# debug_backplane.net
KiCad netlist of a schematic drawn in EAGLE
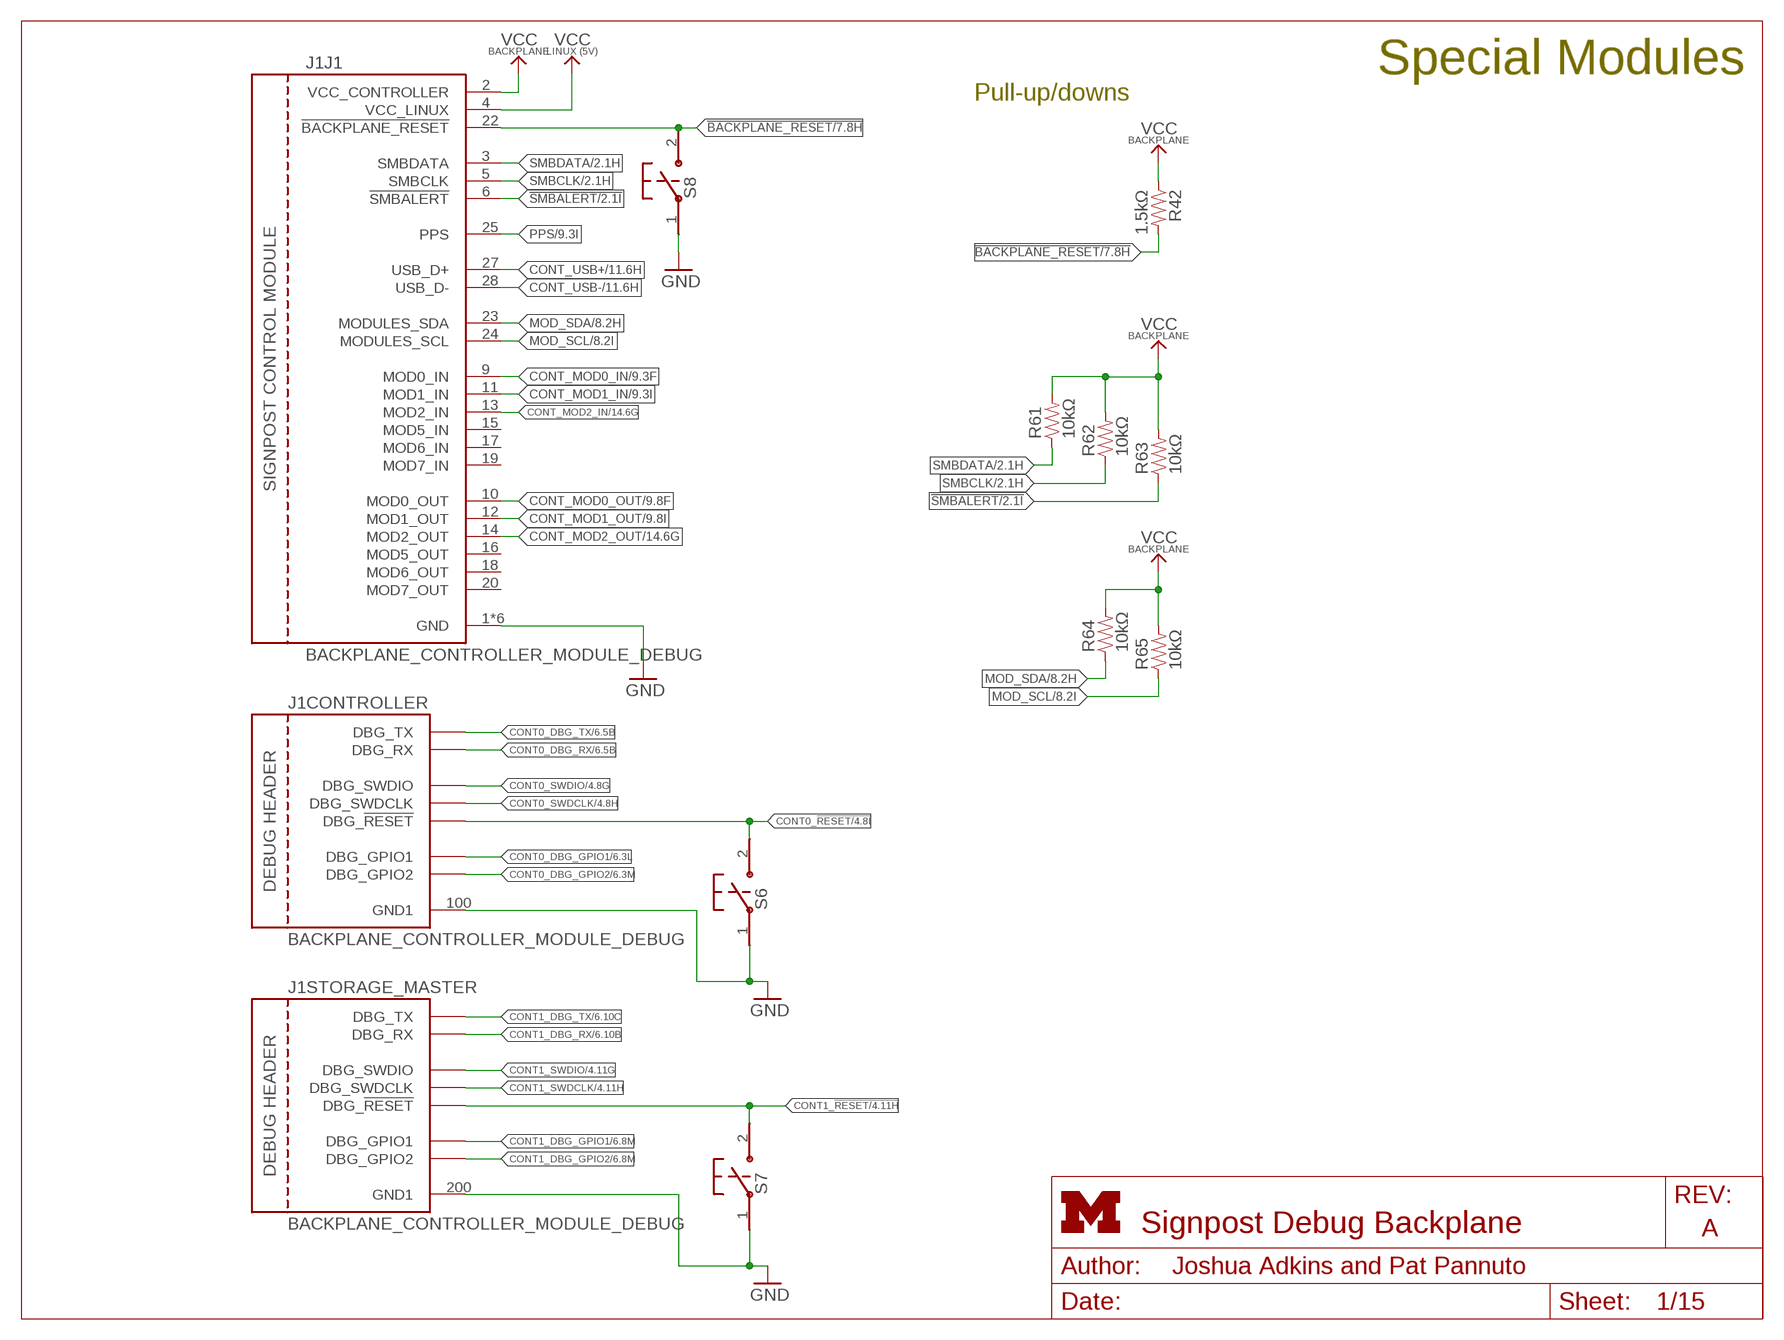
[diagram p0: schematic, sheet 1]
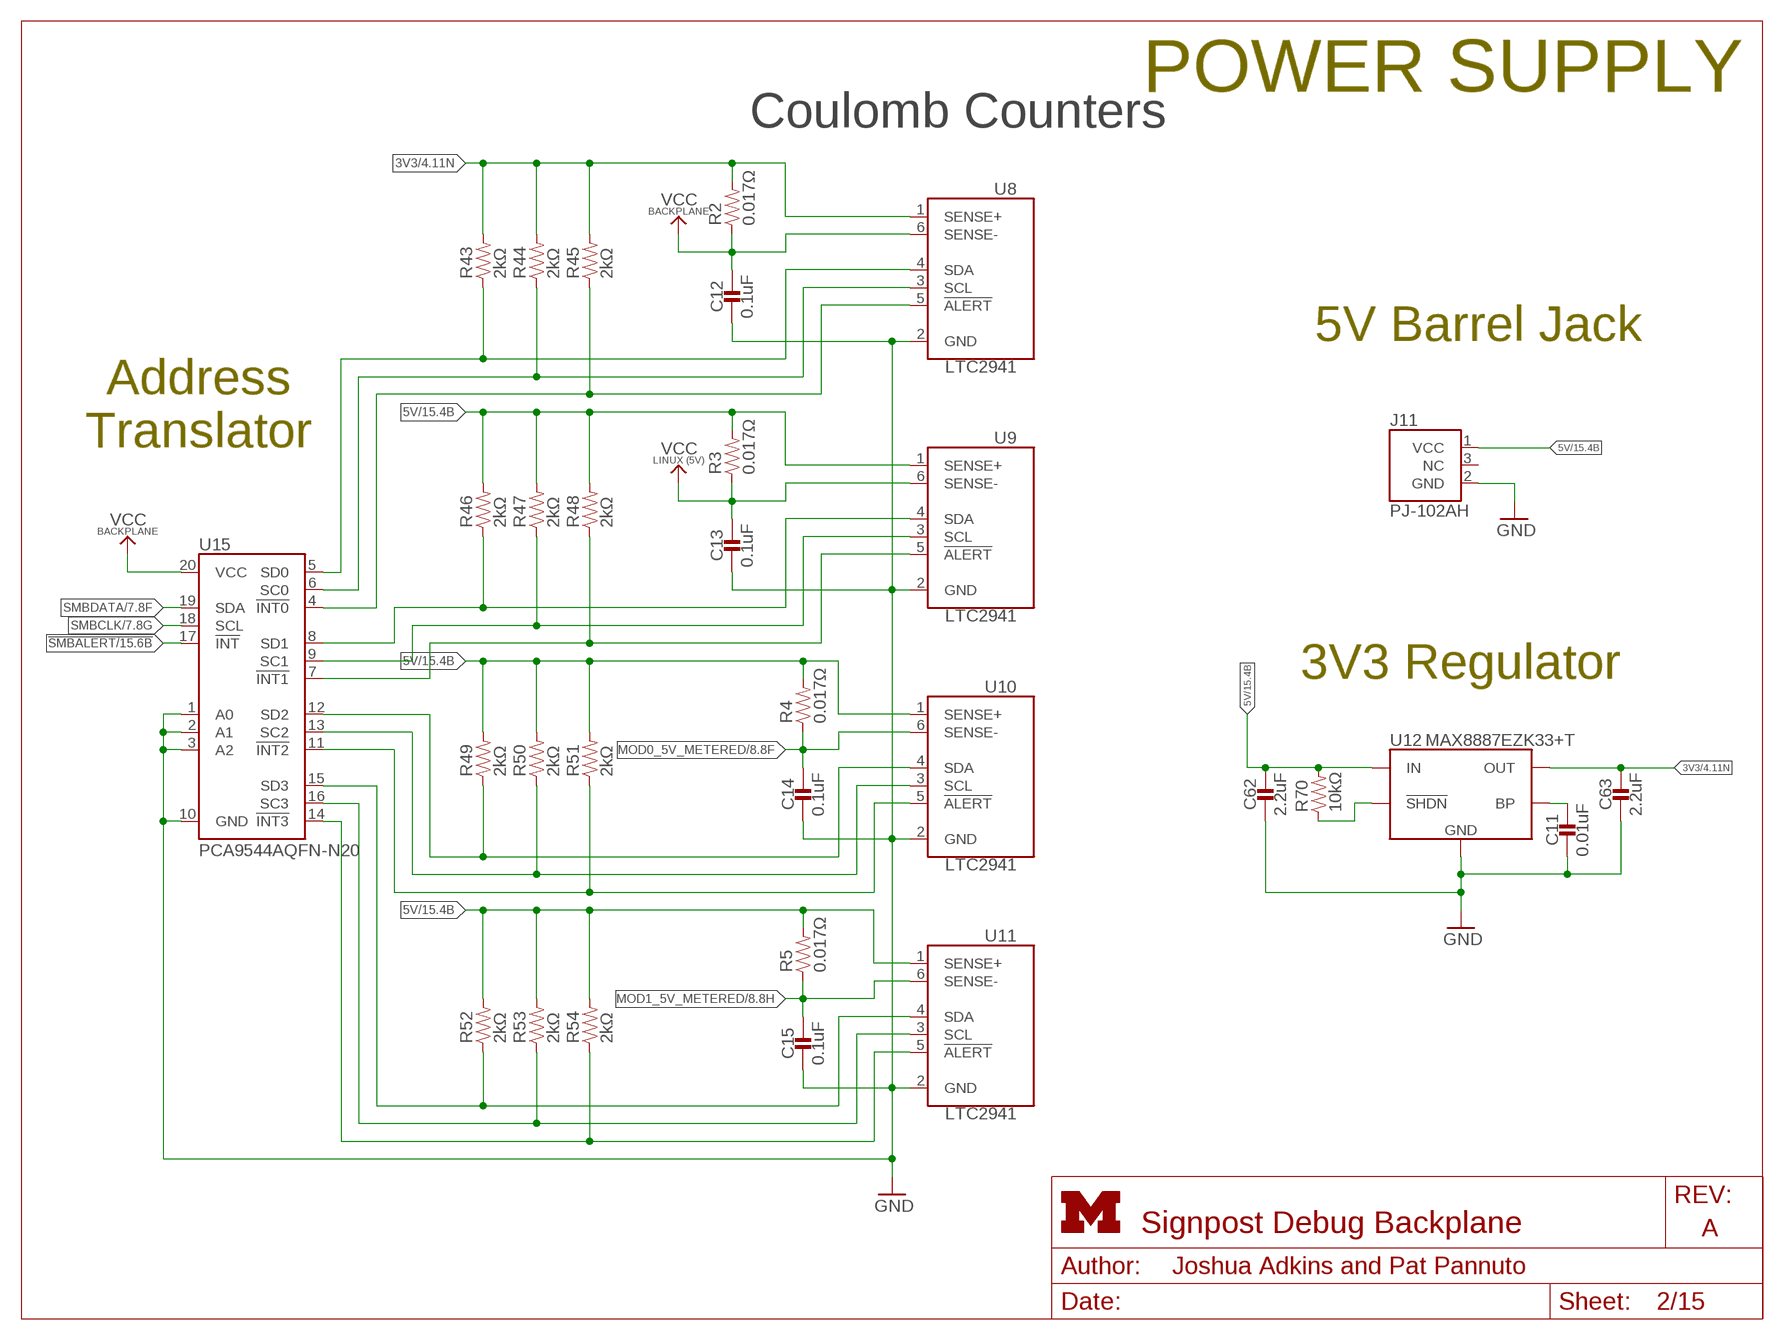
[diagram p1: schematic, sheet 2]
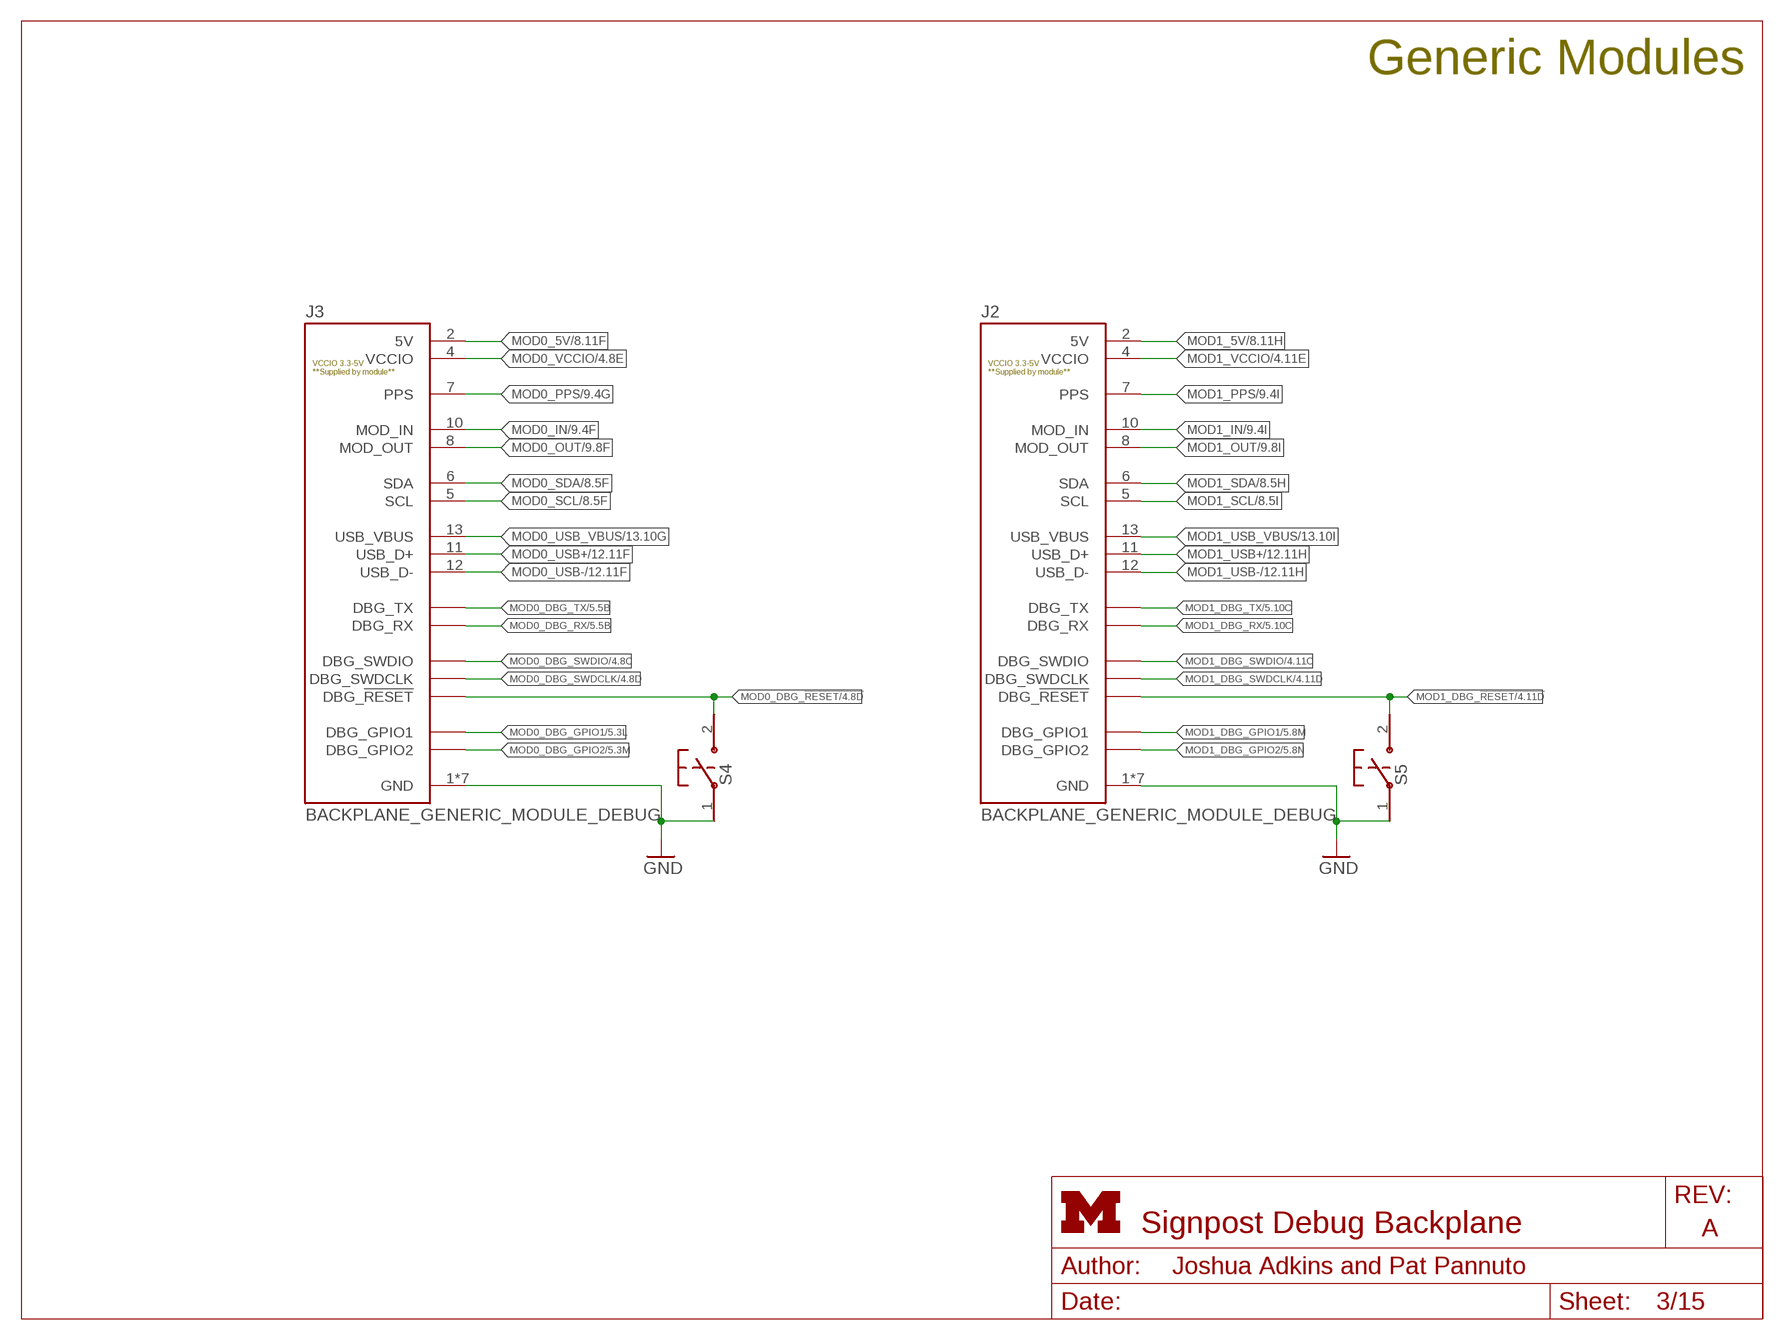
[diagram p2: schematic, sheet 3]
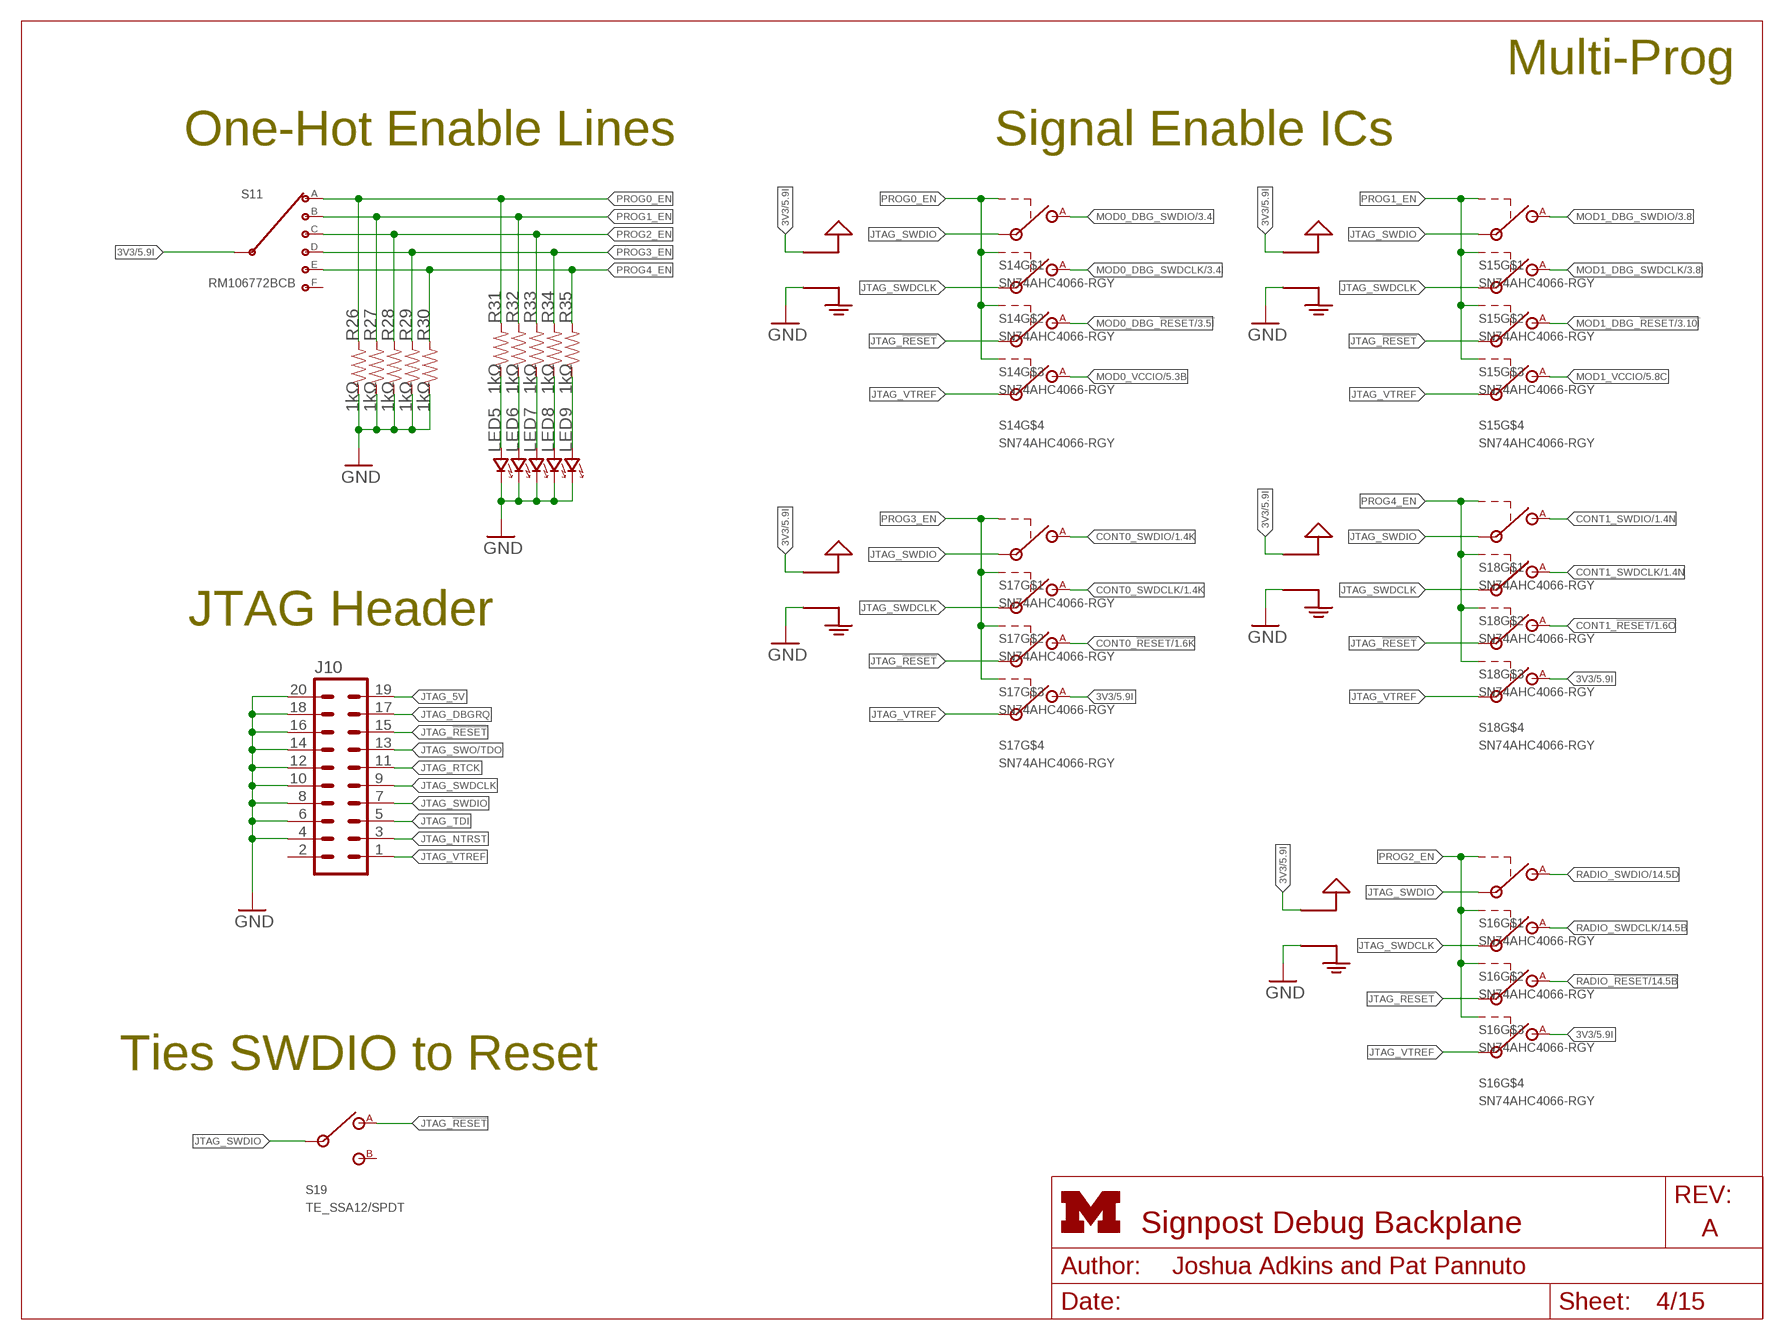
[diagram p3: schematic, sheet 4]
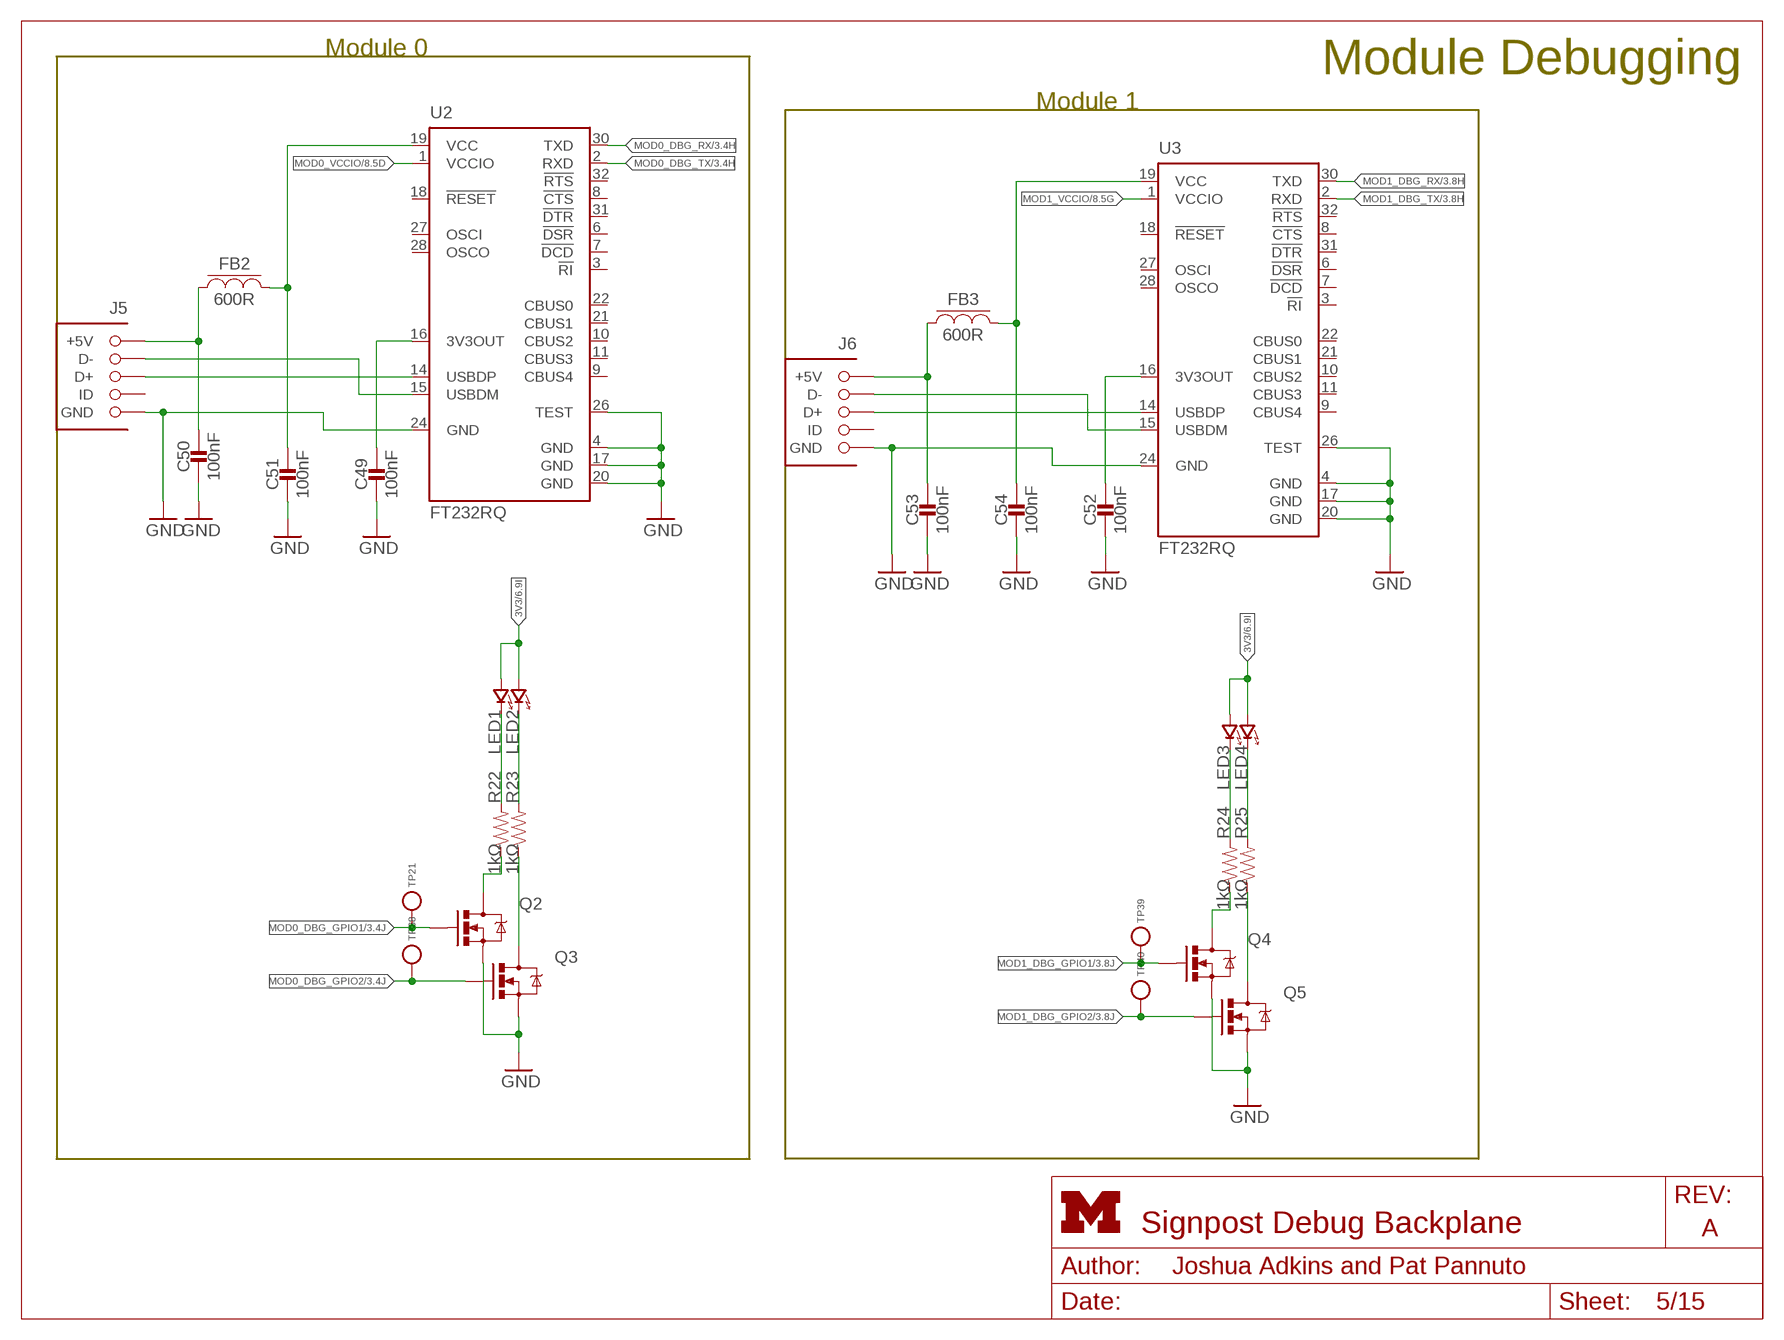
[diagram p4: schematic, sheet 5]
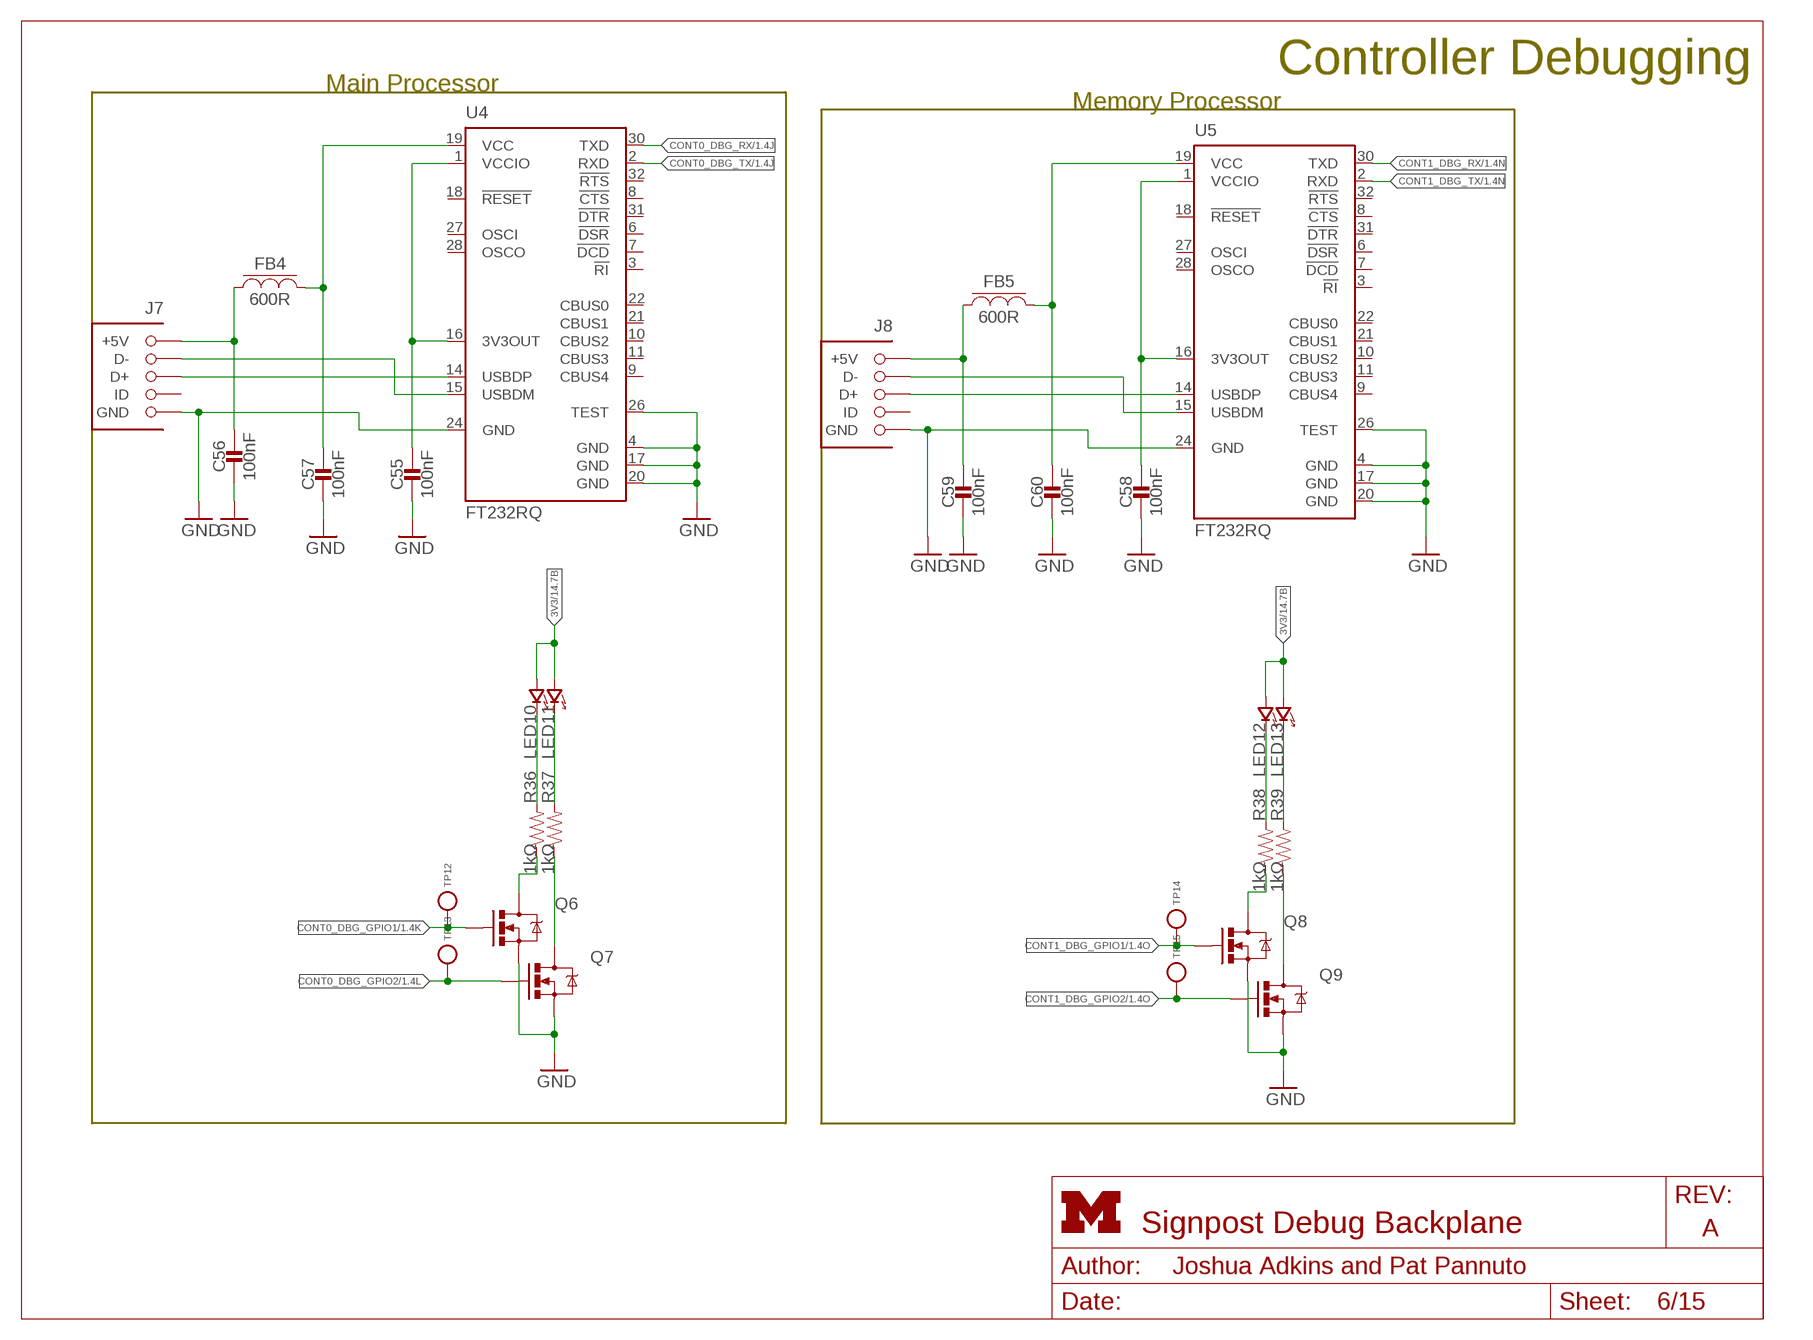
[diagram p5: schematic, sheet 6]
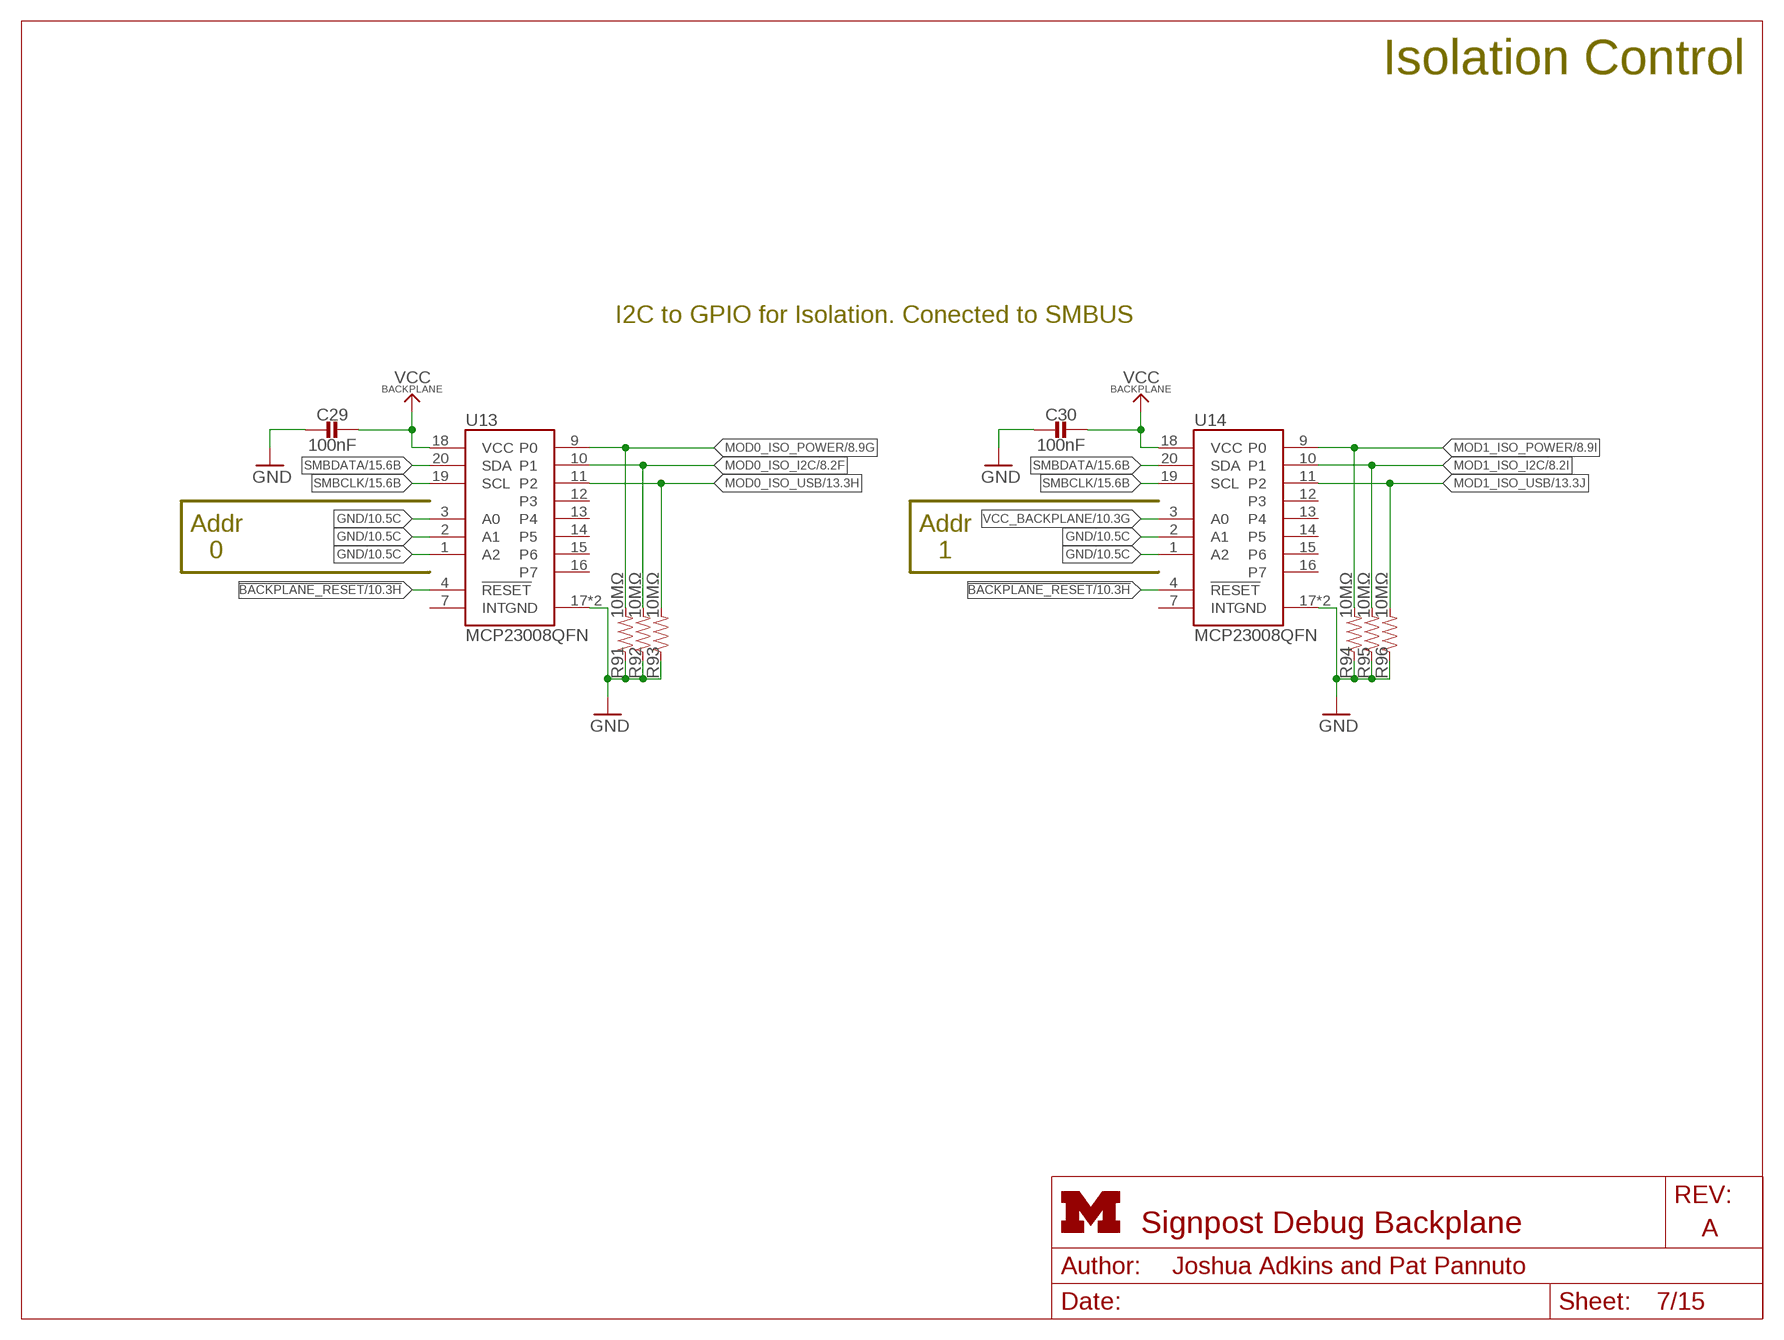
[diagram p6: schematic, sheet 7]
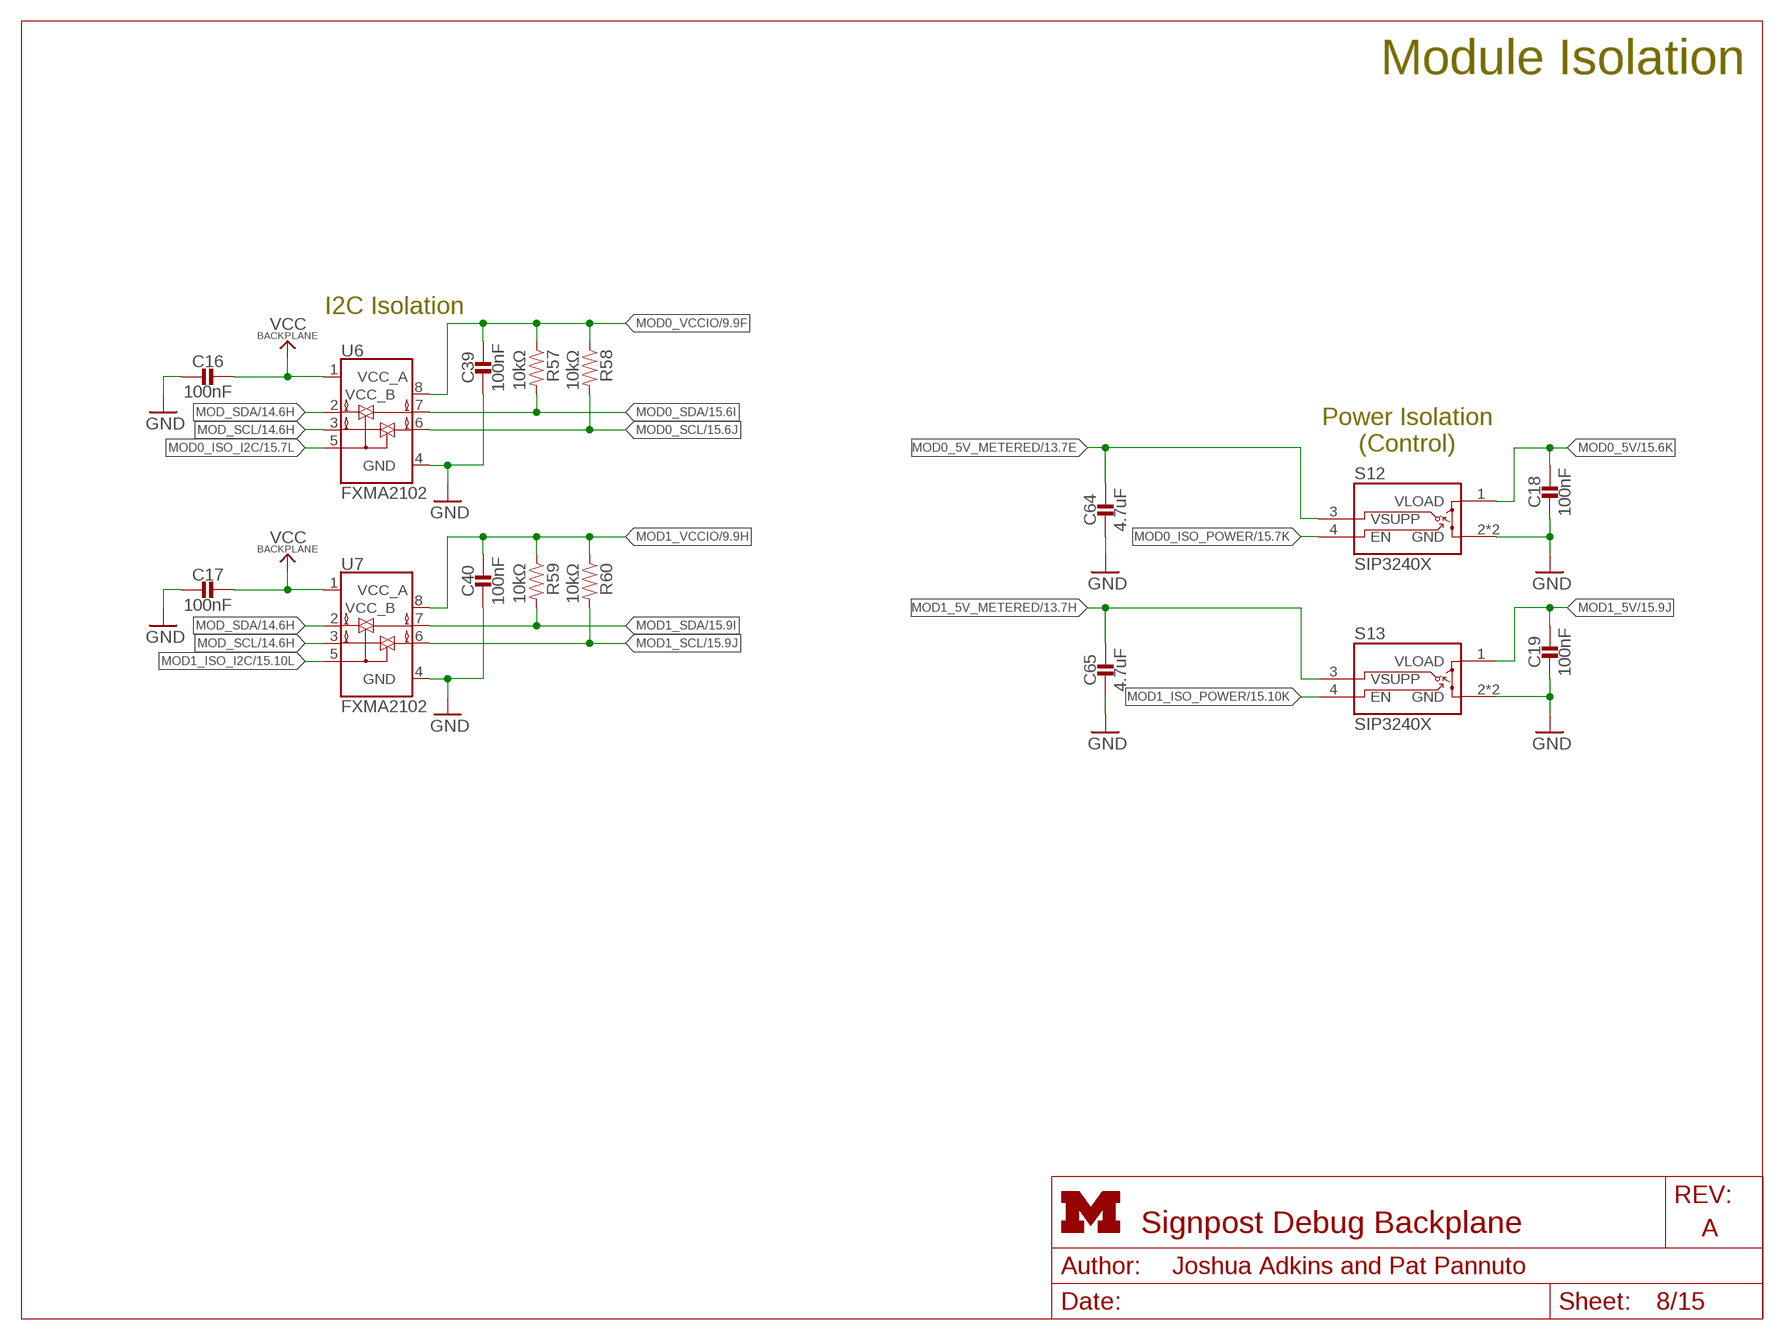
[diagram p7: schematic, sheet 8]
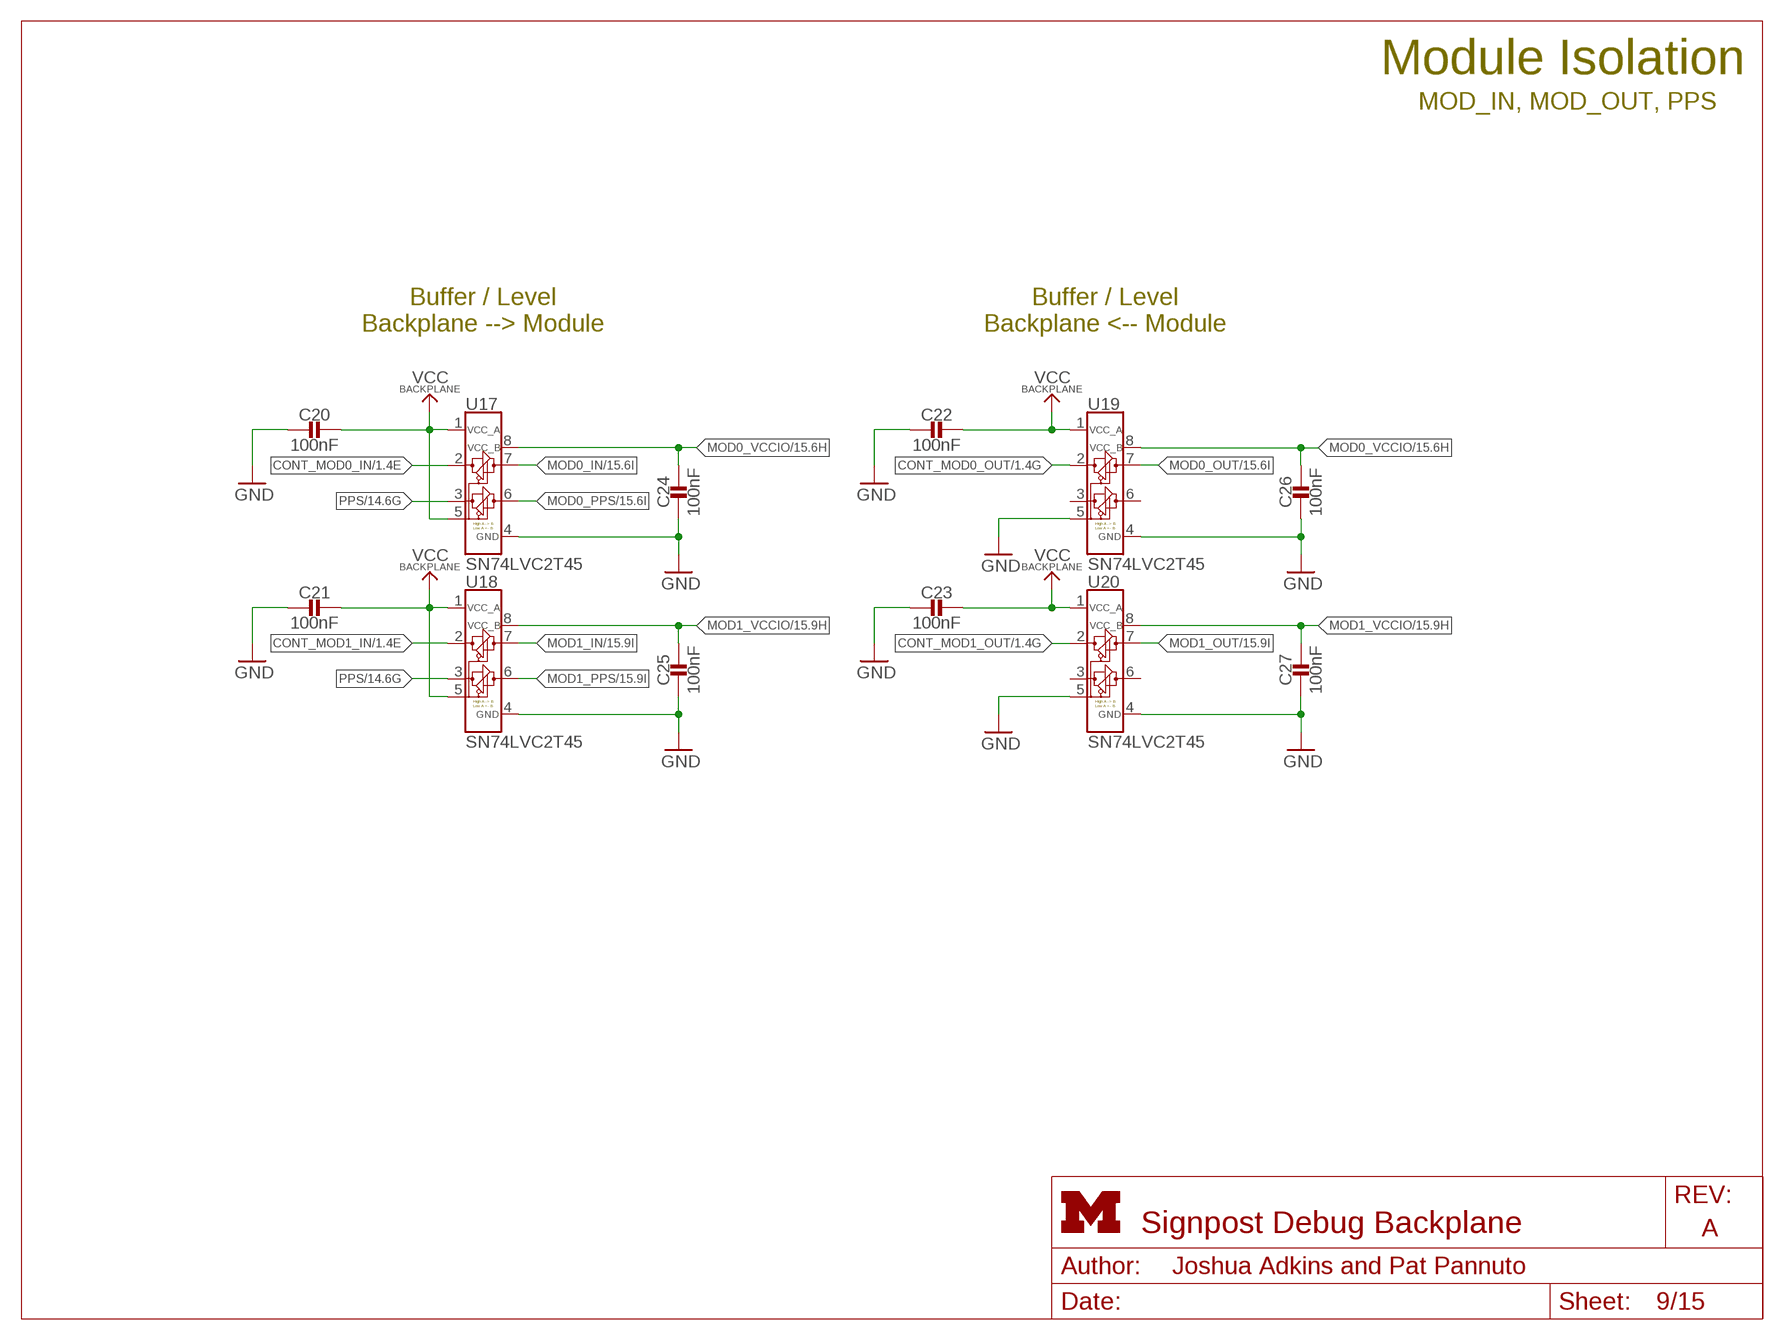
[diagram p8: schematic, sheet 9]
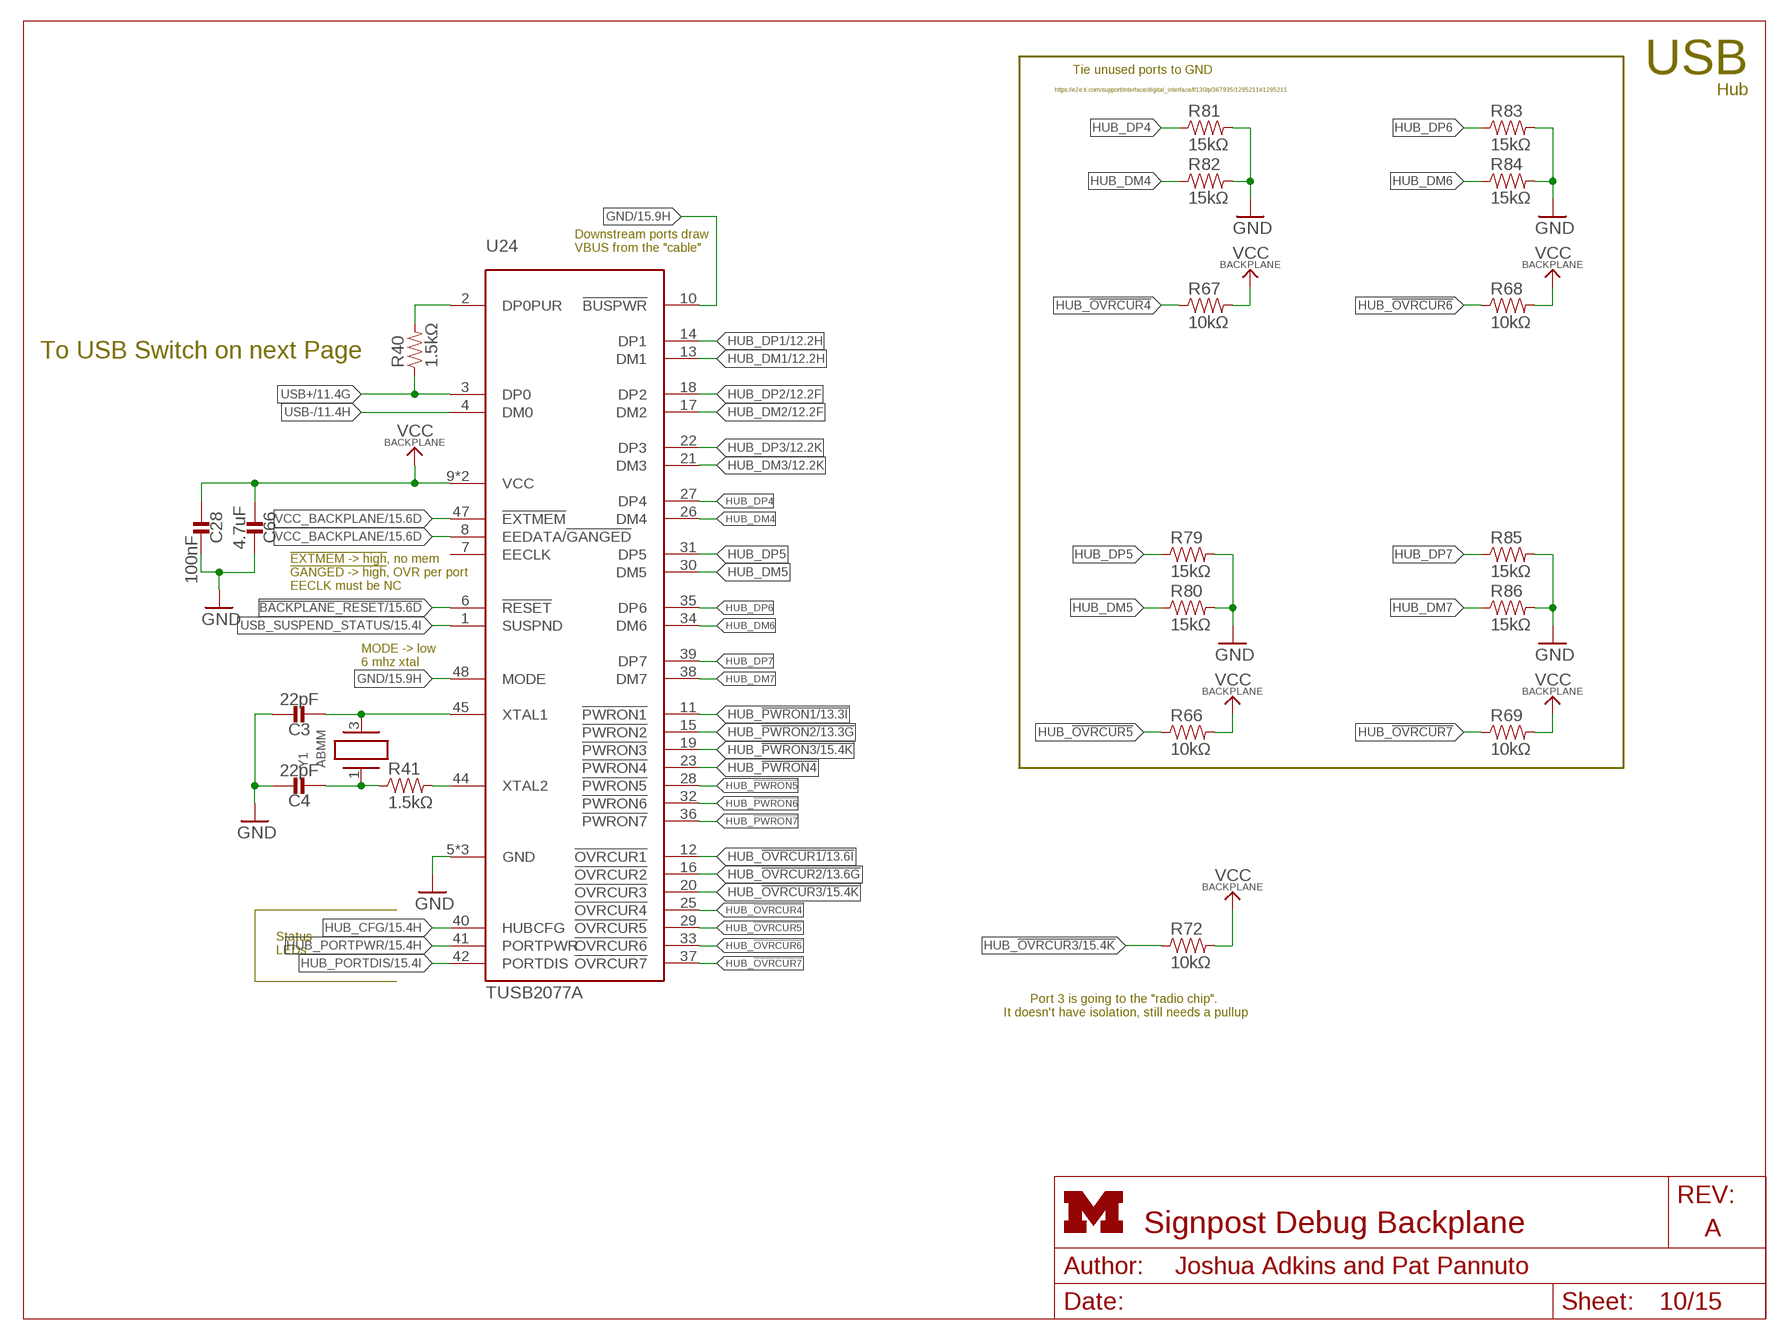
[diagram p9: schematic, sheet 10]
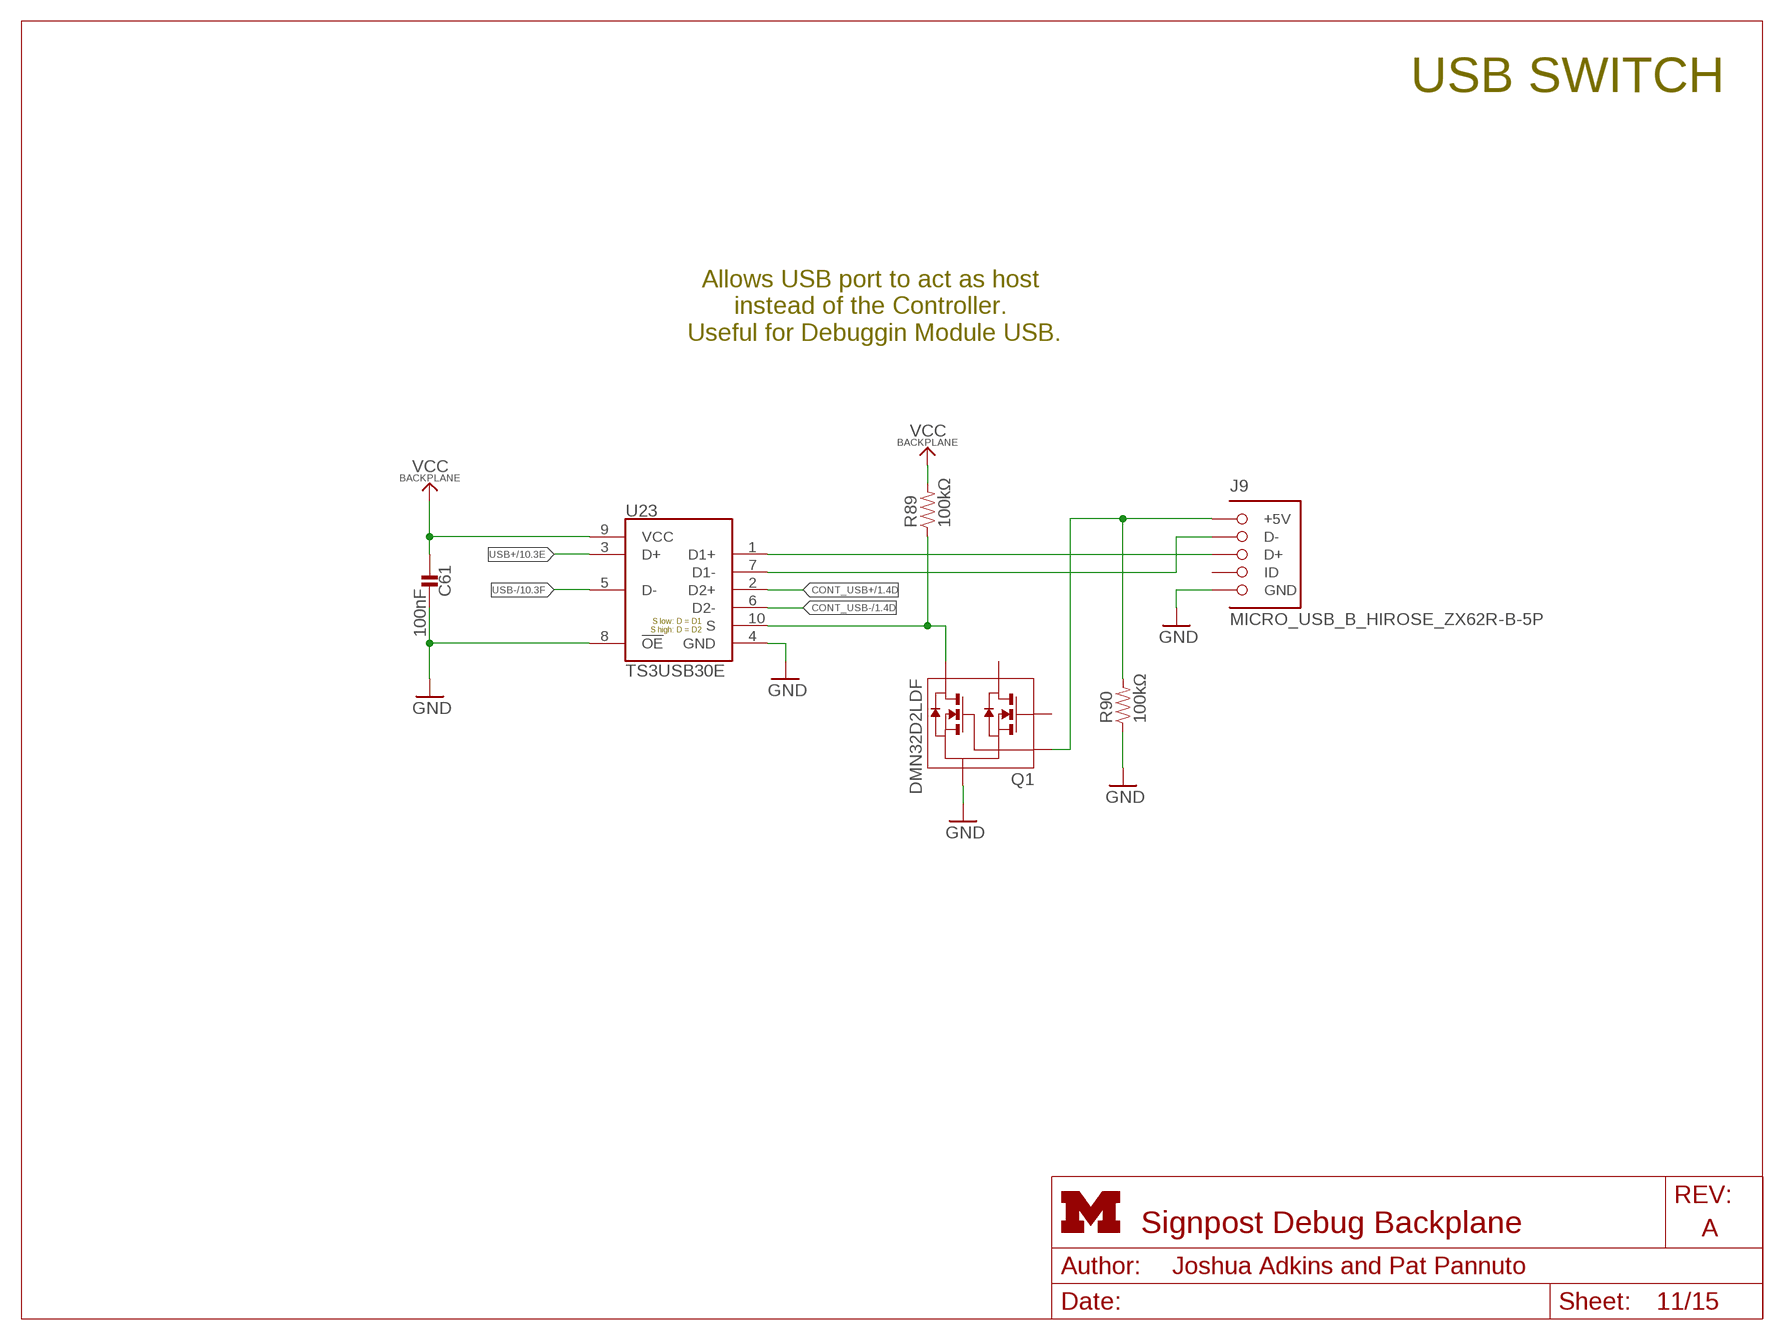
[diagram p10: schematic, sheet 11]
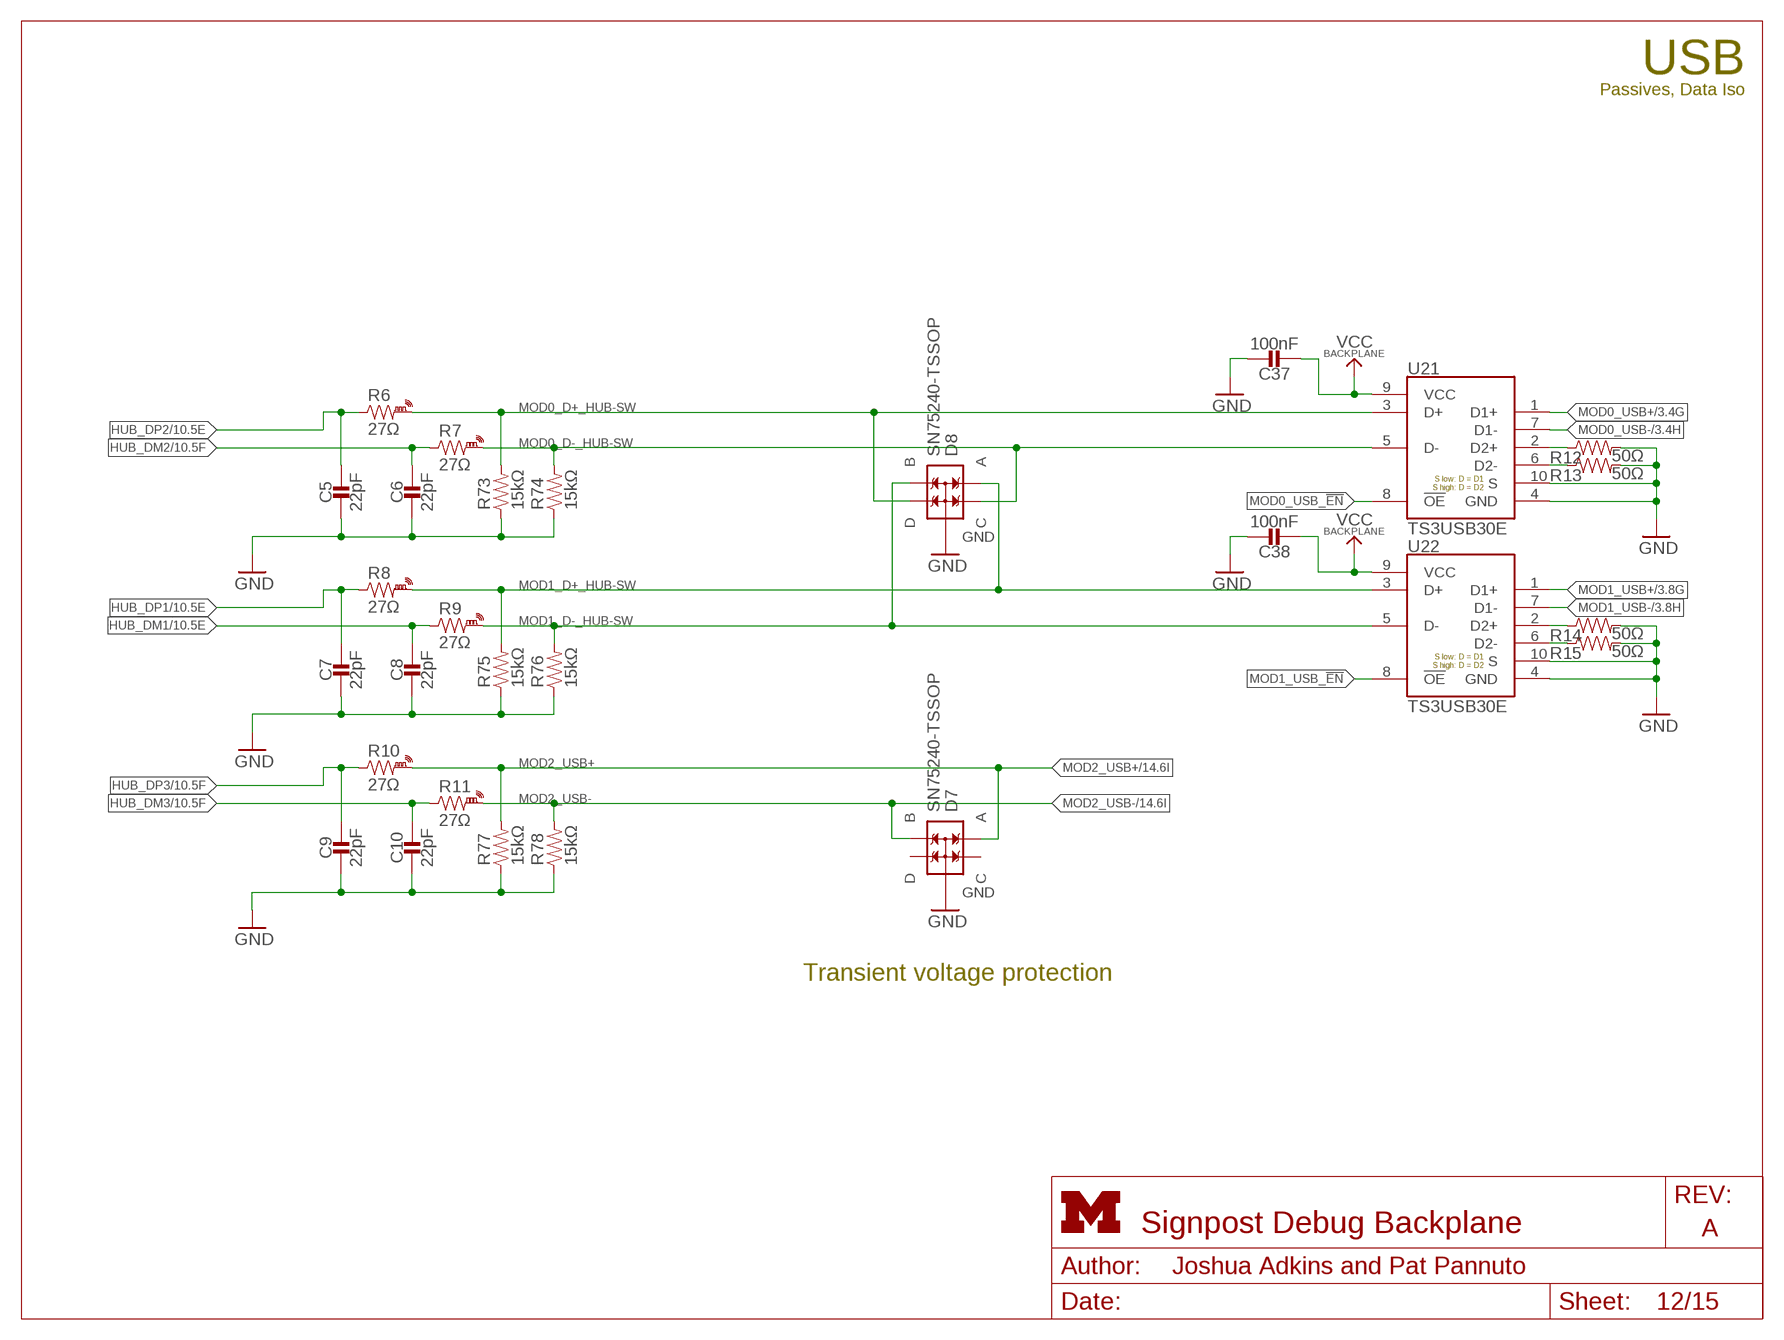
[diagram p11: schematic, sheet 12]
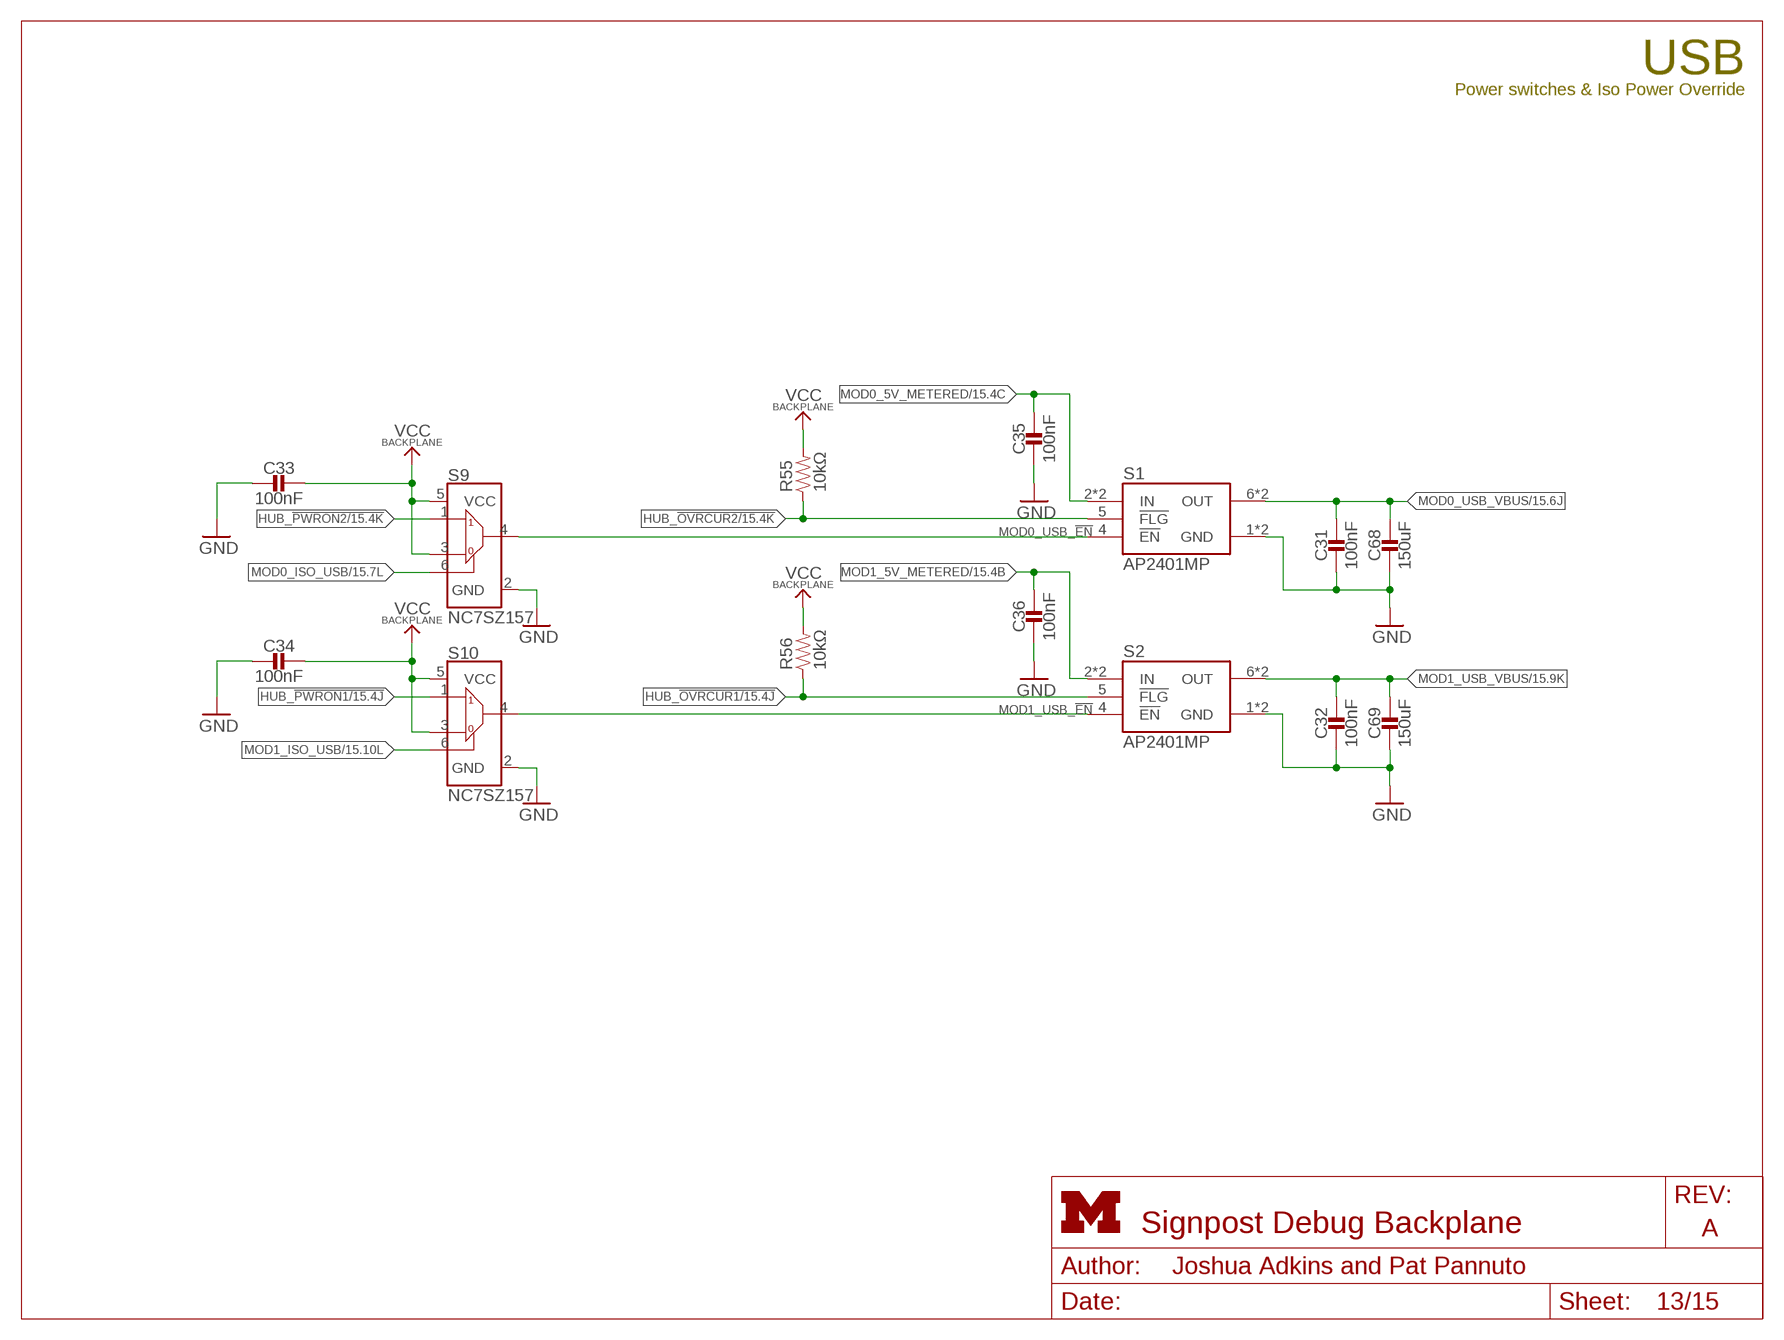
[diagram p12: schematic, sheet 13]
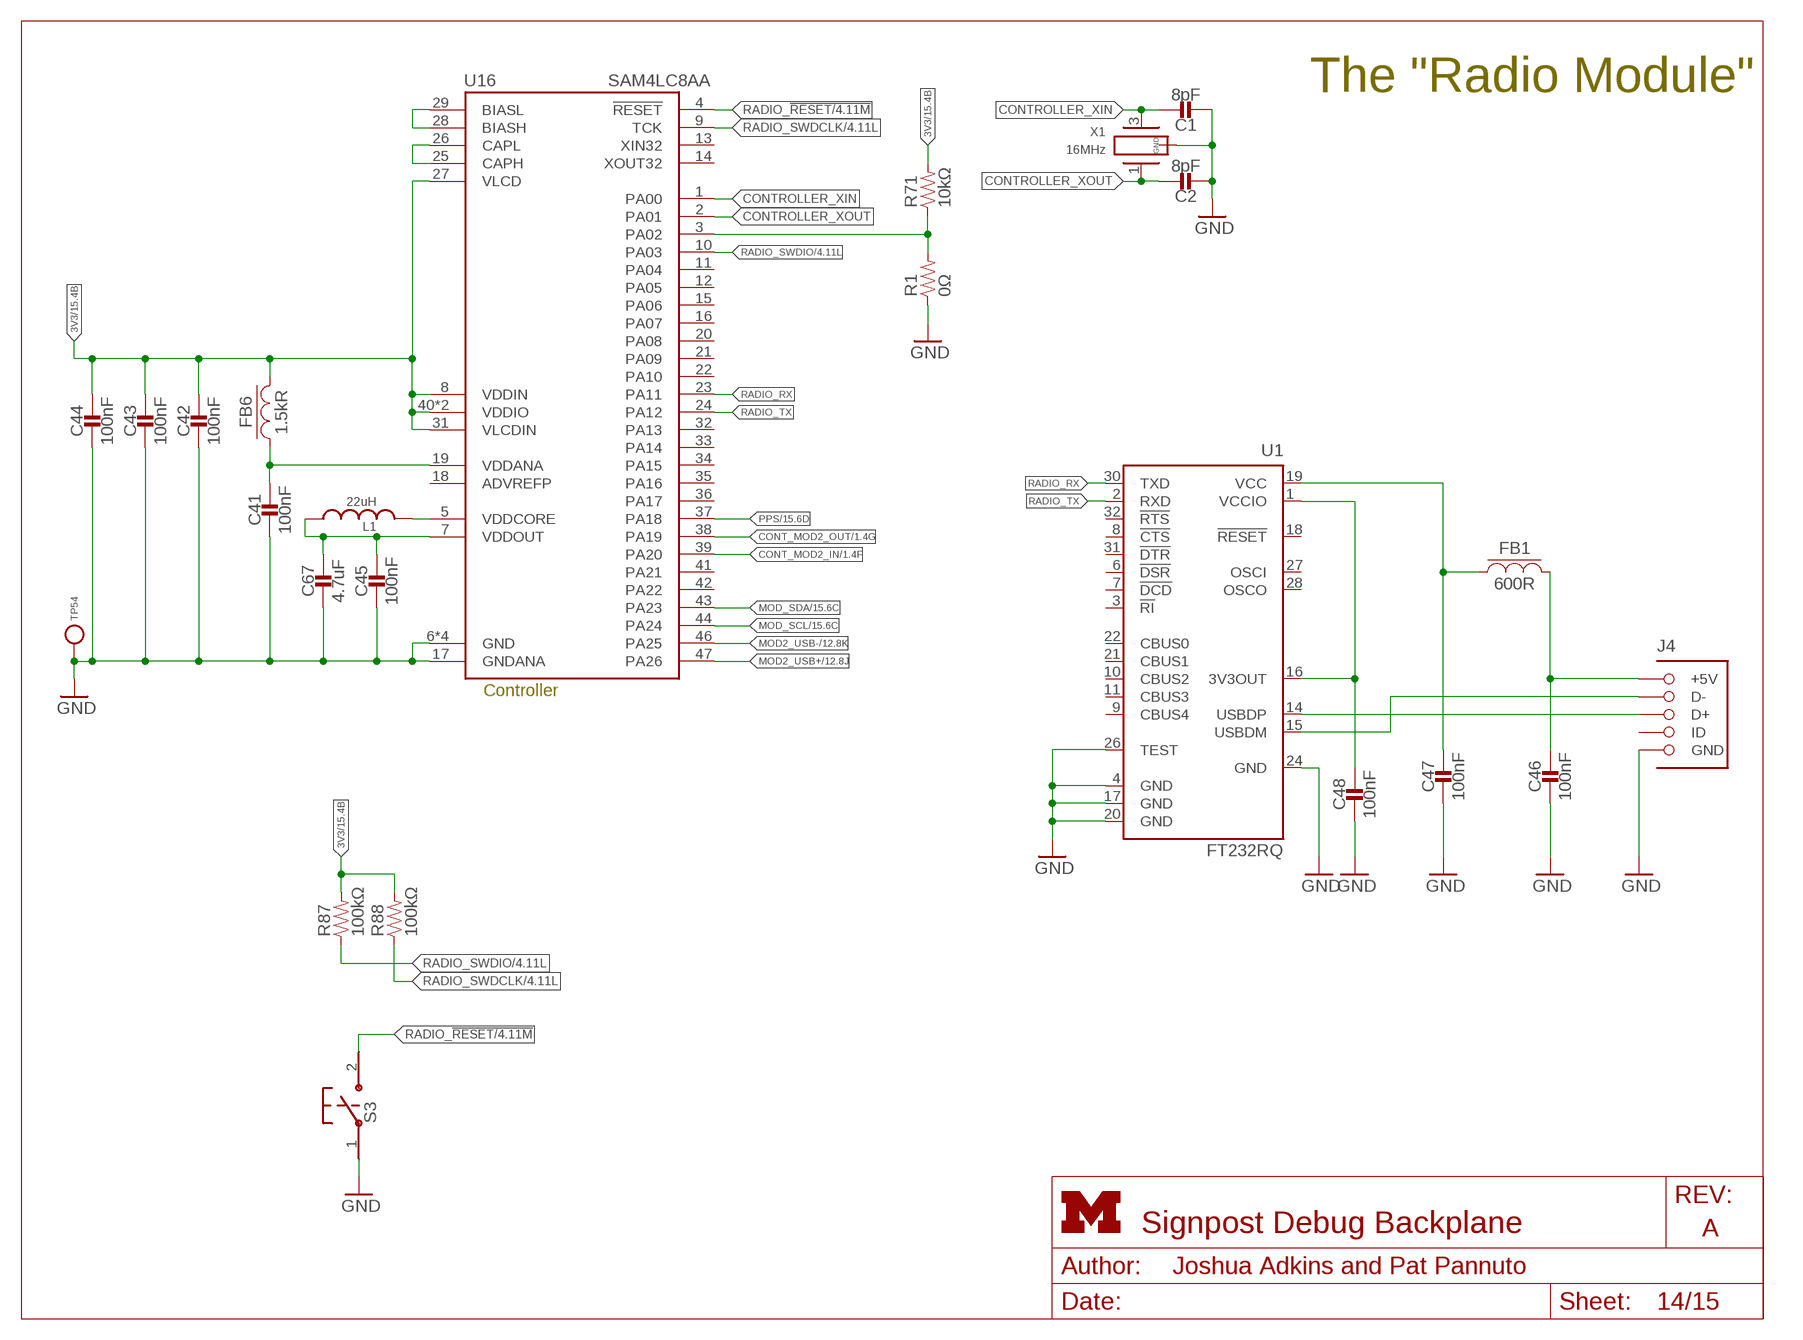
[diagram p13: schematic, sheet 14]
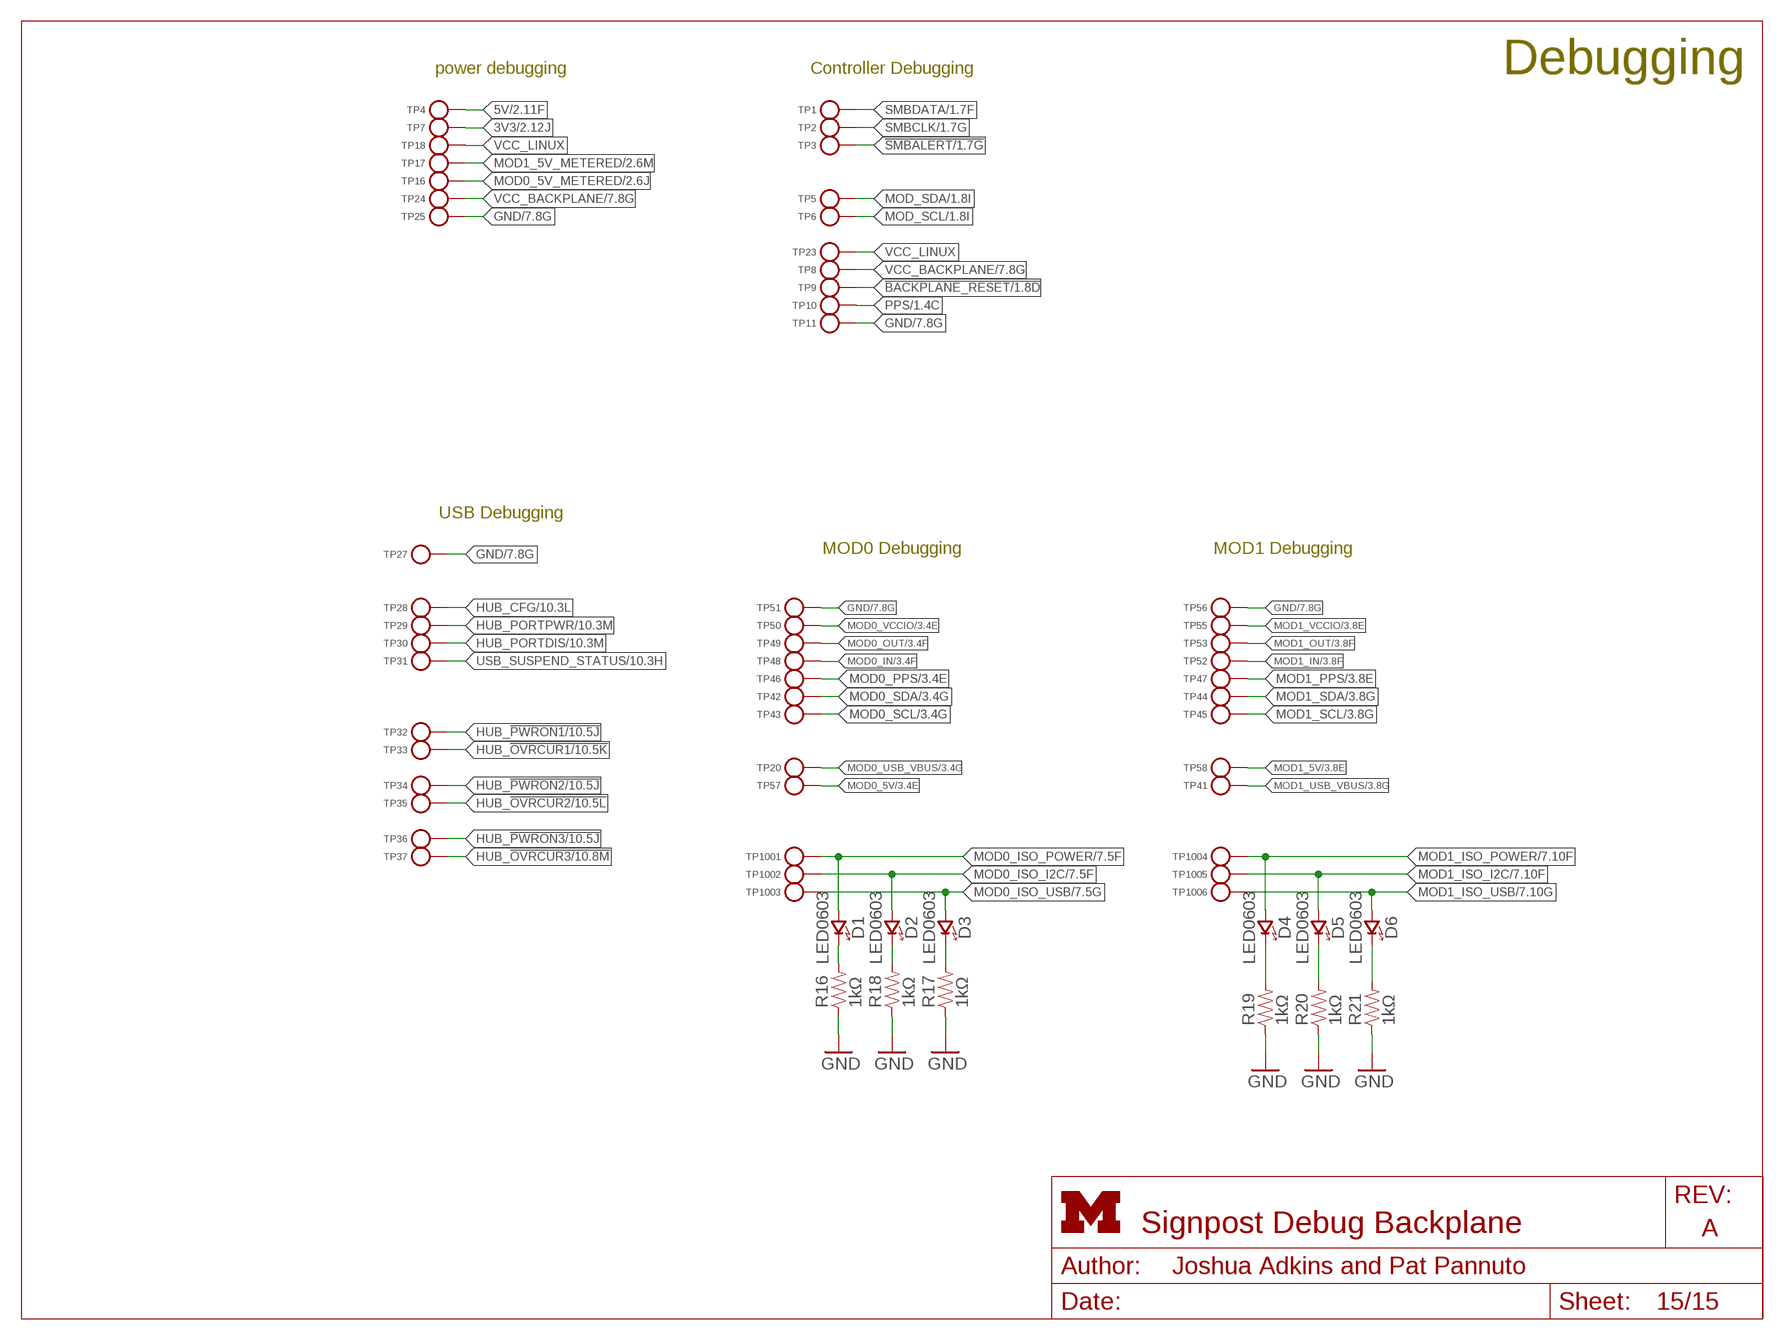
[diagram p14: schematic, sheet 15]

(export (version "E")
  (design (tool "Eeschema 10.0.6"))
  (components
    (comp (ref "C31")
      (value "100nF")
      (footprint "eagle-import:0603_CAP")
      (libsource (lib "eagle-import") (part "CAPACITOR0603_CAP"))
    )
    (comp (ref "C32")
      (value "100nF")
      (footprint "eagle-import:0603_CAP")
      (libsource (lib "eagle-import") (part "CAPACITOR0603_CAP"))
    )
    (comp (ref "C33")
      (value "100nF")
      (footprint "eagle-import:0603_CAP")
      (libsource (lib "eagle-import") (part "CAPACITOR0603_CAP"))
    )
    (comp (ref "C34")
      (value "100nF")
      (footprint "eagle-import:0603_CAP")
      (libsource (lib "eagle-import") (part "CAPACITOR0603_CAP"))
    )
    (comp (ref "C35")
      (value "100nF")
      (footprint "eagle-import:0603_CAP")
      (libsource (lib "eagle-import") (part "CAPACITOR0603_CAP"))
    )
    (comp (ref "C36")
      (value "100nF")
      (footprint "eagle-import:0603_CAP")
      (libsource (lib "eagle-import") (part "CAPACITOR0603_CAP"))
    )
    (comp (ref "C68")
      (value "150uF")
      (footprint "eagle-import:1210_CAP")
      (libsource (lib "eagle-import") (part "CAPACITOR1210_CAP"))
    )
    (comp (ref "C69")
      (value "150uF")
      (footprint "eagle-import:1210_CAP")
      (libsource (lib "eagle-import") (part "CAPACITOR1210_CAP"))
    )
    (comp (ref "R55")
      (value "10kΩ")
      (footprint "eagle-import:0603-RES")
      (libsource (lib "eagle-import") (part "RESISTOR0603_RES"))
    )
    (comp (ref "R56")
      (value "10kΩ")
      (footprint "eagle-import:0603-RES")
      (libsource (lib "eagle-import") (part "RESISTOR0603_RES"))
    )
    (comp (ref "S1")
      (value "AP2401MP")
      (footprint "eagle-import:MSOP-8EP")
      (libsource (lib "eagle-import") (part "AP2401MP"))
    )
    (comp (ref "S2")
      (value "AP2401MP")
      (footprint "eagle-import:MSOP-8EP")
      (libsource (lib "eagle-import") (part "AP2401MP"))
    )
    (comp (ref "S9")
      (value "NC7SZ157")
      (footprint "eagle-import:SC70-6")
      (libsource (lib "eagle-import") (part "NC7SZ157"))
    )
    (comp (ref "S10")
      (value "NC7SZ157")
      (footprint "eagle-import:SC70-6")
      (libsource (lib "eagle-import") (part "NC7SZ157"))
    )
    (comp (ref "C29")
      (value "100nF")
      (footprint "eagle-import:0603_CAP")
      (libsource (lib "eagle-import") (part "CAPACITOR0603_CAP"))
    )
    (comp (ref "C30")
      (value "100nF")
      (footprint "eagle-import:0603_CAP")
      (libsource (lib "eagle-import") (part "CAPACITOR0603_CAP"))
    )
    (comp (ref "R91")
      (value "10MΩ")
      (footprint "eagle-import:0603-RES")
      (libsource (lib "eagle-import") (part "RESISTOR0603_RES"))
    )
    (comp (ref "R92")
      (value "10MΩ")
      (footprint "eagle-import:0603-RES")
      (libsource (lib "eagle-import") (part "RESISTOR0603_RES"))
    )
    (comp (ref "R93")
      (value "10MΩ")
      (footprint "eagle-import:0603-RES")
      (libsource (lib "eagle-import") (part "RESISTOR0603_RES"))
    )
    (comp (ref "R94")
      (value "10MΩ")
      (footprint "eagle-import:0603-RES")
      (libsource (lib "eagle-import") (part "RESISTOR0603_RES"))
    )
    (comp (ref "R95")
      (value "10MΩ")
      (footprint "eagle-import:0603-RES")
      (libsource (lib "eagle-import") (part "RESISTOR0603_RES"))
    )
    (comp (ref "R96")
      (value "10MΩ")
      (footprint "eagle-import:0603-RES")
      (libsource (lib "eagle-import") (part "RESISTOR0603_RES"))
    )
    (comp (ref "U13")
      (value "MCP23008QFN")
      (footprint "eagle-import:QFN-20-4MM")
      (libsource (lib "eagle-import") (part "MCP23008QFN"))
    )
    (comp (ref "U14")
      (value "MCP23008QFN")
      (footprint "eagle-import:QFN-20-4MM")
      (libsource (lib "eagle-import") (part "MCP23008QFN"))
    )
    (comp (ref "C5")
      (value "22pF")
      (footprint "eagle-import:0402_CAP")
      (libsource (lib "eagle-import") (part "CAPACITOR0402_CAP"))
    )
    (comp (ref "C6")
      (value "22pF")
      (footprint "eagle-import:0402_CAP")
      (libsource (lib "eagle-import") (part "CAPACITOR0402_CAP"))
    )
    (comp (ref "C7")
      (value "22pF")
      (footprint "eagle-import:0402_CAP")
      (libsource (lib "eagle-import") (part "CAPACITOR0402_CAP"))
    )
    (comp (ref "C8")
      (value "22pF")
      (footprint "eagle-import:0402_CAP")
      (libsource (lib "eagle-import") (part "CAPACITOR0402_CAP"))
    )
    (comp (ref "C9")
      (value "22pF")
      (footprint "eagle-import:0402_CAP")
      (libsource (lib "eagle-import") (part "CAPACITOR0402_CAP"))
    )
    (comp (ref "C10")
      (value "22pF")
      (footprint "eagle-import:0402_CAP")
      (libsource (lib "eagle-import") (part "CAPACITOR0402_CAP"))
    )
    (comp (ref "C37")
      (value "100nF")
      (footprint "eagle-import:0603_CAP")
      (libsource (lib "eagle-import") (part "CAPACITOR0603_CAP"))
    )
    (comp (ref "C38")
      (value "100nF")
      (footprint "eagle-import:0603_CAP")
      (libsource (lib "eagle-import") (part "CAPACITOR0603_CAP"))
    )
    (comp (ref "D7")
      (value "SN75240-TSSOP")
      (footprint "eagle-import:TSSOP-8")
      (libsource (lib "eagle-import") (part "SN75240-TSSOP"))
    )
    (comp (ref "D8")
      (value "SN75240-TSSOP")
      (footprint "eagle-import:TSSOP-8")
      (libsource (lib "eagle-import") (part "SN75240-TSSOP"))
    )
    (comp (ref "R6")
      (value "27Ω")
      (footprint "eagle-import:0402_RES-HIGH_SPEED")
      (libsource (lib "eagle-import") (part "RESISTOR-HIGH_SPEED0402"))
    )
    (comp (ref "R7")
      (value "27Ω")
      (footprint "eagle-import:0402_RES-HIGH_SPEED")
      (libsource (lib "eagle-import") (part "RESISTOR-HIGH_SPEED0402"))
    )
    (comp (ref "R8")
      (value "27Ω")
      (footprint "eagle-import:0402_RES-HIGH_SPEED")
      (libsource (lib "eagle-import") (part "RESISTOR-HIGH_SPEED0402"))
    )
    (comp (ref "R9")
      (value "27Ω")
      (footprint "eagle-import:0402_RES-HIGH_SPEED")
      (libsource (lib "eagle-import") (part "RESISTOR-HIGH_SPEED0402"))
    )
    (comp (ref "R10")
      (value "27Ω")
      (footprint "eagle-import:0402_RES-HIGH_SPEED")
      (libsource (lib "eagle-import") (part "RESISTOR-HIGH_SPEED0402"))
    )
    (comp (ref "R11")
      (value "27Ω")
      (footprint "eagle-import:0402_RES-HIGH_SPEED")
      (libsource (lib "eagle-import") (part "RESISTOR-HIGH_SPEED0402"))
    )
    (comp (ref "R12")
      (value "50Ω")
      (footprint "eagle-import:0603-RES")
      (libsource (lib "eagle-import") (part "RESISTOR0603_RES"))
    )
    (comp (ref "R13")
      (value "50Ω")
      (footprint "eagle-import:0603-RES")
      (libsource (lib "eagle-import") (part "RESISTOR0603_RES"))
    )
    (comp (ref "R14")
      (value "50Ω")
      (footprint "eagle-import:0603-RES")
      (libsource (lib "eagle-import") (part "RESISTOR0603_RES"))
    )
    (comp (ref "R15")
      (value "50Ω")
      (footprint "eagle-import:0603-RES")
      (libsource (lib "eagle-import") (part "RESISTOR0603_RES"))
    )
    (comp (ref "R73")
      (value "15kΩ")
      (footprint "eagle-import:0603-RES")
      (libsource (lib "eagle-import") (part "RESISTOR0603_RES"))
    )
    (comp (ref "R74")
      (value "15kΩ")
      (footprint "eagle-import:0603-RES")
      (libsource (lib "eagle-import") (part "RESISTOR0603_RES"))
    )
    (comp (ref "R75")
      (value "15kΩ")
      (footprint "eagle-import:0603-RES")
      (libsource (lib "eagle-import") (part "RESISTOR0603_RES"))
    )
    (comp (ref "R76")
      (value "15kΩ")
      (footprint "eagle-import:0603-RES")
      (libsource (lib "eagle-import") (part "RESISTOR0603_RES"))
    )
    (comp (ref "R77")
      (value "15kΩ")
      (footprint "eagle-import:0603-RES")
      (libsource (lib "eagle-import") (part "RESISTOR0603_RES"))
    )
    (comp (ref "R78")
      (value "15kΩ")
      (footprint "eagle-import:0603-RES")
      (libsource (lib "eagle-import") (part "RESISTOR0603_RES"))
    )
    (comp (ref "U21")
      (value "TS3USB30E")
      (footprint "eagle-import:UQFN-10")
      (libsource (lib "eagle-import") (part "TS3USB30E"))
    )
    (comp (ref "U22")
      (value "TS3USB30E")
      (footprint "eagle-import:UQFN-10")
      (libsource (lib "eagle-import") (part "TS3USB30E"))
    )
    (comp (ref "J1")
      (value "BACKPLANE_CONTROLLER_MODULE_DEBUG")
      (footprint "eagle-import:BACKPLANE_MODULE_20PIN_10PIN_DEBUG")
      (libsource (lib "eagle-import") (part "BACKPLANE_CONTROLLER_MODULE_DEBUG"))
    )
    (comp (ref "R42")
      (value "1.5kΩ")
      (footprint "eagle-import:0603-RES")
      (libsource (lib "eagle-import") (part "RESISTOR0603_RES"))
    )
    (comp (ref "R61")
      (value "10kΩ")
      (footprint "eagle-import:0603-RES")
      (libsource (lib "eagle-import") (part "RESISTOR0603_RES"))
    )
    (comp (ref "R62")
      (value "10kΩ")
      (footprint "eagle-import:0603-RES")
      (libsource (lib "eagle-import") (part "RESISTOR0603_RES"))
    )
    (comp (ref "R63")
      (value "10kΩ")
      (footprint "eagle-import:0603-RES")
      (libsource (lib "eagle-import") (part "RESISTOR0603_RES"))
    )
    (comp (ref "R64")
      (value "10kΩ")
      (footprint "eagle-import:0603-RES")
      (libsource (lib "eagle-import") (part "RESISTOR0603_RES"))
    )
    (comp (ref "R65")
      (value "10kΩ")
      (footprint "eagle-import:0603-RES")
      (libsource (lib "eagle-import") (part "RESISTOR0603_RES"))
    )
    (comp (ref "S6")
      (value "B3U-1000P")
      (footprint "eagle-import:B3U-1000P")
      (libsource (lib "eagle-import") (part "B3U-1000P"))
    )
    (comp (ref "S7")
      (value "B3U-1000P")
      (footprint "eagle-import:B3U-1000P")
      (libsource (lib "eagle-import") (part "B3U-1000P"))
    )
    (comp (ref "S8")
      (value "B3U-1000P")
      (footprint "eagle-import:B3U-1000P")
      (libsource (lib "eagle-import") (part "B3U-1000P"))
    )
    (comp (ref "C49")
      (value "100nF")
      (footprint "eagle-import:0603_CAP")
      (libsource (lib "eagle-import") (part "CAPACITOR0603_CAP"))
    )
    (comp (ref "C50")
      (value "100nF")
      (footprint "eagle-import:0603_CAP")
      (libsource (lib "eagle-import") (part "CAPACITOR0603_CAP"))
    )
    (comp (ref "C51")
      (value "100nF")
      (footprint "eagle-import:0603_CAP")
      (libsource (lib "eagle-import") (part "CAPACITOR0603_CAP"))
    )
    (comp (ref "C52")
      (value "100nF")
      (footprint "eagle-import:0603_CAP")
      (libsource (lib "eagle-import") (part "CAPACITOR0603_CAP"))
    )
    (comp (ref "C53")
      (value "100nF")
      (footprint "eagle-import:0603_CAP")
      (libsource (lib "eagle-import") (part "CAPACITOR0603_CAP"))
    )
    (comp (ref "C54")
      (value "100nF")
      (footprint "eagle-import:0603_CAP")
      (libsource (lib "eagle-import") (part "CAPACITOR0603_CAP"))
    )
    (comp (ref "FB2")
      (value "600R")
      (footprint "eagle-import:0603_CAP")
      (libsource (lib "eagle-import") (part "FERRITE_BEAD0603"))
    )
    (comp (ref "FB3")
      (value "600R")
      (footprint "eagle-import:0603_CAP")
      (libsource (lib "eagle-import") (part "FERRITE_BEAD0603"))
    )
    (comp (ref "J5")
      (value "MICRO_USB_B_HIROSE_ZX62R-B-5P")
      (footprint "eagle-import:USB_MICRO_B-HIROSE-ZX62R-B-5P")
      (libsource (lib "eagle-import") (part "MICRO_USB_B_HIROSE_ZX62R-B-5P"))
    )
    (comp (ref "J6")
      (value "MICRO_USB_B_HIROSE_ZX62R-B-5P")
      (footprint "eagle-import:USB_MICRO_B-HIROSE-ZX62R-B-5P")
      (libsource (lib "eagle-import") (part "MICRO_USB_B_HIROSE_ZX62R-B-5P"))
    )
    (comp (ref "LED1")
      (value "LED0603")
      (footprint "eagle-import:LED-0603")
      (libsource (lib "eagle-import") (part "LED0603"))
    )
    (comp (ref "LED2")
      (value "LED0603")
      (footprint "eagle-import:LED-0603")
      (libsource (lib "eagle-import") (part "LED0603"))
    )
    (comp (ref "LED3")
      (value "LED0603")
      (footprint "eagle-import:LED-0603")
      (libsource (lib "eagle-import") (part "LED0603"))
    )
    (comp (ref "LED4")
      (value "LED0603")
      (footprint "eagle-import:LED-0603")
      (libsource (lib "eagle-import") (part "LED0603"))
    )
    (comp (ref "Q2")
      (value "MOSFET-NCHANNELSMD")
      (footprint "eagle-import:SOT23-3")
      (libsource (lib "eagle-import") (part "MOSFET-NCHANNELSMD"))
    )
    (comp (ref "Q3")
      (value "MOSFET-NCHANNELSMD")
      (footprint "eagle-import:SOT23-3")
      (libsource (lib "eagle-import") (part "MOSFET-NCHANNELSMD"))
    )
    (comp (ref "Q4")
      (value "MOSFET-NCHANNELSMD")
      (footprint "eagle-import:SOT23-3")
      (libsource (lib "eagle-import") (part "MOSFET-NCHANNELSMD"))
    )
    (comp (ref "Q5")
      (value "MOSFET-NCHANNELSMD")
      (footprint "eagle-import:SOT23-3")
      (libsource (lib "eagle-import") (part "MOSFET-NCHANNELSMD"))
    )
    (comp (ref "R22")
      (value "1kΩ")
      (footprint "eagle-import:0603-RES")
      (libsource (lib "eagle-import") (part "RESISTOR0603_RES"))
    )
    (comp (ref "R23")
      (value "1kΩ")
      (footprint "eagle-import:0603-RES")
      (libsource (lib "eagle-import") (part "RESISTOR0603_RES"))
    )
    (comp (ref "R24")
      (value "1kΩ")
      (footprint "eagle-import:0603-RES")
      (libsource (lib "eagle-import") (part "RESISTOR0603_RES"))
    )
    (comp (ref "R25")
      (value "1kΩ")
      (footprint "eagle-import:0603-RES")
      (libsource (lib "eagle-import") (part "RESISTOR0603_RES"))
    )
    (comp (ref "TP21")
      (value "TEST_POINT_0.040IN")
      (footprint "eagle-import:TESTPOINT_0.040IN")
      (libsource (lib "eagle-import") (part "TEST_POINT_0.040IN"))
    )
    (comp (ref "TP38")
      (value "TEST_POINT_0.040IN")
      (footprint "eagle-import:TESTPOINT_0.040IN")
      (libsource (lib "eagle-import") (part "TEST_POINT_0.040IN"))
    )
    (comp (ref "TP39")
      (value "TEST_POINT_0.040IN")
      (footprint "eagle-import:TESTPOINT_0.040IN")
      (libsource (lib "eagle-import") (part "TEST_POINT_0.040IN"))
    )
    (comp (ref "TP40")
      (value "TEST_POINT_0.040IN")
      (footprint "eagle-import:TESTPOINT_0.040IN")
      (libsource (lib "eagle-import") (part "TEST_POINT_0.040IN"))
    )
    (comp (ref "U2")
      (value "FT232RQ")
      (footprint "eagle-import:QFN32")
      (libsource (lib "eagle-import") (part "FT232RQ"))
    )
    (comp (ref "U3")
      (value "FT232RQ")
      (footprint "eagle-import:QFN32")
      (libsource (lib "eagle-import") (part "FT232RQ"))
    )
    (comp (ref "J10")
      (value "ML20")
      (footprint "eagle-import:ML20")
      (libsource (lib "eagle-import") (part "ML20"))
    )
    (comp (ref "LED5")
      (value "LED0603")
      (footprint "eagle-import:LED-0603")
      (libsource (lib "eagle-import") (part "LED0603"))
    )
    (comp (ref "LED6")
      (value "LED0603")
      (footprint "eagle-import:LED-0603")
      (libsource (lib "eagle-import") (part "LED0603"))
    )
    (comp (ref "LED7")
      (value "LED0603")
      (footprint "eagle-import:LED-0603")
      (libsource (lib "eagle-import") (part "LED0603"))
    )
    (comp (ref "LED8")
      (value "LED0603")
      (footprint "eagle-import:LED-0603")
      (libsource (lib "eagle-import") (part "LED0603"))
    )
    (comp (ref "LED9")
      (value "LED0603")
      (footprint "eagle-import:LED-0603")
      (libsource (lib "eagle-import") (part "LED0603"))
    )
    (comp (ref "R26")
      (value "1kΩ")
      (footprint "eagle-import:0603-RES")
      (libsource (lib "eagle-import") (part "RESISTOR0603_RES"))
    )
    (comp (ref "R27")
      (value "1kΩ")
      (footprint "eagle-import:0603-RES")
      (libsource (lib "eagle-import") (part "RESISTOR0603_RES"))
    )
    (comp (ref "R28")
      (value "1kΩ")
      (footprint "eagle-import:0603-RES")
      (libsource (lib "eagle-import") (part "RESISTOR0603_RES"))
    )
    (comp (ref "R29")
      (value "1kΩ")
      (footprint "eagle-import:0603-RES")
      (libsource (lib "eagle-import") (part "RESISTOR0603_RES"))
    )
    (comp (ref "R30")
      (value "1kΩ")
      (footprint "eagle-import:0603-RES")
      (libsource (lib "eagle-import") (part "RESISTOR0603_RES"))
    )
    (comp (ref "R31")
      (value "1kΩ")
      (footprint "eagle-import:0603-RES")
      (libsource (lib "eagle-import") (part "RESISTOR0603_RES"))
    )
    (comp (ref "R32")
      (value "1kΩ")
      (footprint "eagle-import:0603-RES")
      (libsource (lib "eagle-import") (part "RESISTOR0603_RES"))
    )
    (comp (ref "R33")
      (value "1kΩ")
      (footprint "eagle-import:0603-RES")
      (libsource (lib "eagle-import") (part "RESISTOR0603_RES"))
    )
    (comp (ref "R34")
      (value "1kΩ")
      (footprint "eagle-import:0603-RES")
      (libsource (lib "eagle-import") (part "RESISTOR0603_RES"))
    )
    (comp (ref "R35")
      (value "1kΩ")
      (footprint "eagle-import:0603-RES")
      (libsource (lib "eagle-import") (part "RESISTOR0603_RES"))
    )
    (comp (ref "S11")
      (value "RM106772BCB")
      (footprint "eagle-import:RM-SWITCH")
      (libsource (lib "eagle-import") (part "RM106772BCB"))
    )
    (comp (ref "S14")
      (value "SN74AHC4066-RGY")
      (footprint "eagle-import:S-PVQFN-N14-3.5MM")
      (libsource (lib "eagle-import") (part "SN74AHC4066-RGY"))
    )
    (comp (ref "S15")
      (value "SN74AHC4066-RGY")
      (footprint "eagle-import:S-PVQFN-N14-3.5MM")
      (libsource (lib "eagle-import") (part "SN74AHC4066-RGY"))
    )
    (comp (ref "S16")
      (value "SN74AHC4066-RGY")
      (footprint "eagle-import:S-PVQFN-N14-3.5MM")
      (libsource (lib "eagle-import") (part "SN74AHC4066-RGY"))
    )
    (comp (ref "S17")
      (value "SN74AHC4066-RGY")
      (footprint "eagle-import:S-PVQFN-N14-3.5MM")
      (libsource (lib "eagle-import") (part "SN74AHC4066-RGY"))
    )
    (comp (ref "S18")
      (value "SN74AHC4066-RGY")
      (footprint "eagle-import:S-PVQFN-N14-3.5MM")
      (libsource (lib "eagle-import") (part "SN74AHC4066-RGY"))
    )
    (comp (ref "S19")
      (value "TE_SSA12/SPDT")
      (footprint "eagle-import:TE_SSA12_SPDT")
      (libsource (lib "eagle-import") (part "TE_SSA12/SPDT"))
    )
    (comp (ref "C1")
      (value "8pF")
      (footprint "eagle-import:0603_CAP")
      (libsource (lib "eagle-import") (part "CAPACITOR0603_CAP"))
    )
    (comp (ref "C2")
      (value "8pF")
      (footprint "eagle-import:0603_CAP")
      (libsource (lib "eagle-import") (part "CAPACITOR0603_CAP"))
    )
    (comp (ref "C41")
      (value "100nF")
      (footprint "eagle-import:0603_CAP")
      (libsource (lib "eagle-import") (part "CAPACITOR0603_CAP"))
    )
    (comp (ref "C42")
      (value "100nF")
      (footprint "eagle-import:0603_CAP")
      (libsource (lib "eagle-import") (part "CAPACITOR0603_CAP"))
    )
    (comp (ref "C43")
      (value "100nF")
      (footprint "eagle-import:0603_CAP")
      (libsource (lib "eagle-import") (part "CAPACITOR0603_CAP"))
    )
    (comp (ref "C44")
      (value "100nF")
      (footprint "eagle-import:0603_CAP")
      (libsource (lib "eagle-import") (part "CAPACITOR0603_CAP"))
    )
    (comp (ref "C45")
      (value "100nF")
      (footprint "eagle-import:0402_CAP")
      (libsource (lib "eagle-import") (part "CAPACITOR0402_CAP"))
    )
    (comp (ref "C46")
      (value "100nF")
      (footprint "eagle-import:0603_CAP")
      (libsource (lib "eagle-import") (part "CAPACITOR0603_CAP"))
    )
    (comp (ref "C47")
      (value "100nF")
      (footprint "eagle-import:0603_CAP")
      (libsource (lib "eagle-import") (part "CAPACITOR0603_CAP"))
    )
    (comp (ref "C48")
      (value "100nF")
      (footprint "eagle-import:0603_CAP")
      (libsource (lib "eagle-import") (part "CAPACITOR0603_CAP"))
    )
    (comp (ref "C67")
      (value "4.7uF")
      (footprint "eagle-import:0402_CAP")
      (libsource (lib "eagle-import") (part "CAPACITOR0402_CAP"))
    )
    (comp (ref "FB1")
      (value "600R")
      (footprint "eagle-import:0603_CAP")
      (libsource (lib "eagle-import") (part "FERRITE_BEAD0603"))
    )
    (comp (ref "FB6")
      (value "1.5kR")
      (footprint "eagle-import:0603_CAP")
      (libsource (lib "eagle-import") (part "FERRITE_BEAD0603"))
    )
    (comp (ref "J4")
      (value "MICRO_USB_B_HIROSE_ZX62R-B-5P")
      (footprint "eagle-import:USB_MICRO_B-HIROSE-ZX62R-B-5P")
      (libsource (lib "eagle-import") (part "MICRO_USB_B_HIROSE_ZX62R-B-5P"))
    )
    (comp (ref "L1")
      (value "22uH")
      (footprint "eagle-import:1212")
      (libsource (lib "eagle-import") (part "LHQ3NP"))
    )
    (comp (ref "R1")
      (value "0Ω")
      (footprint "eagle-import:0603-RES")
      (libsource (lib "eagle-import") (part "RESISTOR0603_RES"))
    )
    (comp (ref "R71")
      (value "10kΩ")
      (footprint "eagle-import:0603-RES")
      (libsource (lib "eagle-import") (part "RESISTOR0603_RES"))
    )
    (comp (ref "R87")
      (value "100kΩ")
      (footprint "eagle-import:0603-RES")
      (libsource (lib "eagle-import") (part "RESISTOR0603_RES"))
    )
    (comp (ref "R88")
      (value "100kΩ")
      (footprint "eagle-import:0603-RES")
      (libsource (lib "eagle-import") (part "RESISTOR0603_RES"))
    )
    (comp (ref "S3")
      (value "B3U-1000P")
      (footprint "eagle-import:B3U-1000P")
      (libsource (lib "eagle-import") (part "B3U-1000P"))
    )
    (comp (ref "TP54")
      (value "TEST_POINT_0.040IN")
      (footprint "eagle-import:TESTPOINT_0.040IN")
      (libsource (lib "eagle-import") (part "TEST_POINT_0.040IN"))
    )
    (comp (ref "U1")
      (value "FT232RQ")
      (footprint "eagle-import:QFN32")
      (libsource (lib "eagle-import") (part "FT232RQ"))
    )
    (comp (ref "U16")
      (value "SAM4LC8AA")
      (footprint "eagle-import:QFN-48-7MM")
      (libsource (lib "eagle-import") (part "SAM4LC8AA"))
    )
    (comp (ref "X1")
      (value "16MHz")
      (footprint "eagle-import:FHXXX")
      (libsource (lib "eagle-import") (part "FH1600015"))
    )
    (comp (ref "C3")
      (value "22pF")
      (footprint "eagle-import:0603_CAP")
      (libsource (lib "eagle-import") (part "CAPACITOR0603_CAP"))
    )
    (comp (ref "C4")
      (value "22pF")
      (footprint "eagle-import:0603_CAP")
      (libsource (lib "eagle-import") (part "CAPACITOR0603_CAP"))
    )
    (comp (ref "C28")
      (value "100nF")
      (footprint "eagle-import:0603_CAP")
      (libsource (lib "eagle-import") (part "CAPACITOR0603_CAP"))
    )
    (comp (ref "C66")
      (value "4.7uF")
      (footprint "eagle-import:0603_CAP")
      (libsource (lib "eagle-import") (part "CAPACITOR0603_CAP"))
    )
    (comp (ref "R40")
      (value "1.5kΩ")
      (footprint "eagle-import:0603-RES")
      (libsource (lib "eagle-import") (part "RESISTOR0603_RES"))
    )
    (comp (ref "R41")
      (value "1.5kΩ")
      (footprint "eagle-import:0603-RES")
      (libsource (lib "eagle-import") (part "RESISTOR0603_RES"))
    )
    (comp (ref "R66")
      (value "10kΩ")
      (footprint "eagle-import:0603-RES")
      (libsource (lib "eagle-import") (part "RESISTOR0603_RES"))
    )
    (comp (ref "R67")
      (value "10kΩ")
      (footprint "eagle-import:0603-RES")
      (libsource (lib "eagle-import") (part "RESISTOR0603_RES"))
    )
    (comp (ref "R68")
      (value "10kΩ")
      (footprint "eagle-import:0603-RES")
      (libsource (lib "eagle-import") (part "RESISTOR0603_RES"))
    )
    (comp (ref "R69")
      (value "10kΩ")
      (footprint "eagle-import:0603-RES")
      (libsource (lib "eagle-import") (part "RESISTOR0603_RES"))
    )
    (comp (ref "R72")
      (value "10kΩ")
      (footprint "eagle-import:0603-RES")
      (libsource (lib "eagle-import") (part "RESISTOR0603_RES"))
    )
    (comp (ref "R79")
      (value "15kΩ")
      (footprint "eagle-import:0603-RES")
      (libsource (lib "eagle-import") (part "RESISTOR0603_RES"))
    )
    (comp (ref "R80")
      (value "15kΩ")
      (footprint "eagle-import:0603-RES")
      (libsource (lib "eagle-import") (part "RESISTOR0603_RES"))
    )
    (comp (ref "R81")
      (value "15kΩ")
      (footprint "eagle-import:0603-RES")
      (libsource (lib "eagle-import") (part "RESISTOR0603_RES"))
    )
    (comp (ref "R82")
      (value "15kΩ")
      (footprint "eagle-import:0603-RES")
      (libsource (lib "eagle-import") (part "RESISTOR0603_RES"))
    )
    (comp (ref "R83")
      (value "15kΩ")
      (footprint "eagle-import:0603-RES")
      (libsource (lib "eagle-import") (part "RESISTOR0603_RES"))
    )
    (comp (ref "R84")
      (value "15kΩ")
      (footprint "eagle-import:0603-RES")
      (libsource (lib "eagle-import") (part "RESISTOR0603_RES"))
    )
    (comp (ref "R85")
      (value "15kΩ")
      (footprint "eagle-import:0603-RES")
      (libsource (lib "eagle-import") (part "RESISTOR0603_RES"))
    )
    (comp (ref "R86")
      (value "15kΩ")
      (footprint "eagle-import:0603-RES")
      (libsource (lib "eagle-import") (part "RESISTOR0603_RES"))
    )
    (comp (ref "U24")
      (value "TUSB2077A")
      (footprint "eagle-import:LQFP-48")
      (libsource (lib "eagle-import") (part "TUSB2077A"))
    )
    (comp (ref "Y1")
      (value "ABMM")
      (footprint "eagle-import:ABMM")
      (libsource (lib "eagle-import") (part "ABMM"))
    )
    (comp (ref "C20")
      (value "100nF")
      (footprint "eagle-import:0603_CAP")
      (libsource (lib "eagle-import") (part "CAPACITOR0603_CAP"))
    )
    (comp (ref "C21")
      (value "100nF")
      (footprint "eagle-import:0603_CAP")
      (libsource (lib "eagle-import") (part "CAPACITOR0603_CAP"))
    )
    (comp (ref "C22")
      (value "100nF")
      (footprint "eagle-import:0603_CAP")
      (libsource (lib "eagle-import") (part "CAPACITOR0603_CAP"))
    )
    (comp (ref "C23")
      (value "100nF")
      (footprint "eagle-import:0603_CAP")
      (libsource (lib "eagle-import") (part "CAPACITOR0603_CAP"))
    )
    (comp (ref "C24")
      (value "100nF")
      (footprint "eagle-import:0603_CAP")
      (libsource (lib "eagle-import") (part "CAPACITOR0603_CAP"))
    )
    (comp (ref "C25")
      (value "100nF")
      (footprint "eagle-import:0603_CAP")
      (libsource (lib "eagle-import") (part "CAPACITOR0603_CAP"))
    )
    (comp (ref "C26")
      (value "100nF")
      (footprint "eagle-import:0603_CAP")
      (libsource (lib "eagle-import") (part "CAPACITOR0603_CAP"))
    )
    (comp (ref "C27")
      (value "100nF")
      (footprint "eagle-import:0603_CAP")
      (libsource (lib "eagle-import") (part "CAPACITOR0603_CAP"))
    )
    (comp (ref "U17")
      (value "SN74LVC2T45")
      (footprint "eagle-import:VFSOP-8")
      (libsource (lib "eagle-import") (part "SN74LVC2T45"))
    )
    (comp (ref "U18")
      (value "SN74LVC2T45")
      (footprint "eagle-import:VFSOP-8")
      (libsource (lib "eagle-import") (part "SN74LVC2T45"))
    )
    (comp (ref "U19")
      (value "SN74LVC2T45")
      (footprint "eagle-import:VFSOP-8")
      (libsource (lib "eagle-import") (part "SN74LVC2T45"))
    )
    (comp (ref "U20")
      (value "SN74LVC2T45")
      (footprint "eagle-import:VFSOP-8")
      (libsource (lib "eagle-import") (part "SN74LVC2T45"))
    )
    (comp (ref "C16")
      (value "100nF")
      (footprint "eagle-import:0603_CAP")
      (libsource (lib "eagle-import") (part "CAPACITOR0603_CAP"))
    )
    (comp (ref "C17")
      (value "100nF")
      (footprint "eagle-import:0603_CAP")
      (libsource (lib "eagle-import") (part "CAPACITOR0603_CAP"))
    )
    (comp (ref "C18")
      (value "100nF")
      (footprint "eagle-import:0603_CAP")
      (libsource (lib "eagle-import") (part "CAPACITOR0603_CAP"))
    )
    (comp (ref "C19")
      (value "100nF")
      (footprint "eagle-import:0603_CAP")
      (libsource (lib "eagle-import") (part "CAPACITOR0603_CAP"))
    )
    (comp (ref "C39")
      (value "100nF")
      (footprint "eagle-import:0603_CAP")
      (libsource (lib "eagle-import") (part "CAPACITOR0603_CAP"))
    )
    (comp (ref "C40")
      (value "100nF")
      (footprint "eagle-import:0603_CAP")
      (libsource (lib "eagle-import") (part "CAPACITOR0603_CAP"))
    )
    (comp (ref "C64")
      (value "4.7uF")
      (footprint "eagle-import:0603_CAP")
      (libsource (lib "eagle-import") (part "CAPACITOR0603_CAP"))
    )
    (comp (ref "C65")
      (value "4.7uF")
      (footprint "eagle-import:0603_CAP")
      (libsource (lib "eagle-import") (part "CAPACITOR0603_CAP"))
    )
    (comp (ref "R57")
      (value "10kΩ")
      (footprint "eagle-import:0603-RES")
      (libsource (lib "eagle-import") (part "RESISTOR0603_RES"))
    )
    (comp (ref "R58")
      (value "10kΩ")
      (footprint "eagle-import:0603-RES")
      (libsource (lib "eagle-import") (part "RESISTOR0603_RES"))
    )
    (comp (ref "R59")
      (value "10kΩ")
      (footprint "eagle-import:0603-RES")
      (libsource (lib "eagle-import") (part "RESISTOR0603_RES"))
    )
    (comp (ref "R60")
      (value "10kΩ")
      (footprint "eagle-import:0603-RES")
      (libsource (lib "eagle-import") (part "RESISTOR0603_RES"))
    )
    (comp (ref "S12")
      (value "SIP3240X")
      (footprint "eagle-import:TDFN4")
      (libsource (lib "eagle-import") (part "SIP3240X"))
    )
    (comp (ref "S13")
      (value "SIP3240X")
      (footprint "eagle-import:TDFN4")
      (libsource (lib "eagle-import") (part "SIP3240X"))
    )
    (comp (ref "U6")
      (value "FXMA2102")
      (footprint "eagle-import:UMLP-8")
      (libsource (lib "eagle-import") (part "FXMA2102"))
    )
    (comp (ref "U7")
      (value "FXMA2102")
      (footprint "eagle-import:UMLP-8")
      (libsource (lib "eagle-import") (part "FXMA2102"))
    )
    (comp (ref "J2")
      (value "BACKPLANE_GENERIC_MODULE_DEBUG")
      (footprint "eagle-import:BACKPLANE_MODULE_14PIN_8PIN")
      (libsource (lib "eagle-import") (part "BACKPLANE_GENERIC_MODULE_DEBUG"))
    )
    (comp (ref "J3")
      (value "BACKPLANE_GENERIC_MODULE_DEBUG")
      (footprint "eagle-import:BACKPLANE_MODULE_14PIN_8PIN")
      (libsource (lib "eagle-import") (part "BACKPLANE_GENERIC_MODULE_DEBUG"))
    )
    (comp (ref "S4")
      (value "B3U-1000P")
      (footprint "eagle-import:B3U-1000P")
      (libsource (lib "eagle-import") (part "B3U-1000P"))
    )
    (comp (ref "S5")
      (value "B3U-1000P")
      (footprint "eagle-import:B3U-1000P")
      (libsource (lib "eagle-import") (part "B3U-1000P"))
    )
    (comp (ref "C55")
      (value "100nF")
      (footprint "eagle-import:0603_CAP")
      (libsource (lib "eagle-import") (part "CAPACITOR0603_CAP"))
    )
    (comp (ref "C56")
      (value "100nF")
      (footprint "eagle-import:0603_CAP")
      (libsource (lib "eagle-import") (part "CAPACITOR0603_CAP"))
    )
    (comp (ref "C57")
      (value "100nF")
      (footprint "eagle-import:0603_CAP")
      (libsource (lib "eagle-import") (part "CAPACITOR0603_CAP"))
    )
    (comp (ref "C58")
      (value "100nF")
      (footprint "eagle-import:0603_CAP")
      (libsource (lib "eagle-import") (part "CAPACITOR0603_CAP"))
    )
    (comp (ref "C59")
      (value "100nF")
      (footprint "eagle-import:0603_CAP")
      (libsource (lib "eagle-import") (part "CAPACITOR0603_CAP"))
    )
    (comp (ref "C60")
      (value "100nF")
      (footprint "eagle-import:0603_CAP")
      (libsource (lib "eagle-import") (part "CAPACITOR0603_CAP"))
    )
    (comp (ref "FB4")
      (value "600R")
      (footprint "eagle-import:0603_CAP")
      (libsource (lib "eagle-import") (part "FERRITE_BEAD0603"))
    )
    (comp (ref "FB5")
      (value "600R")
      (footprint "eagle-import:0603_CAP")
      (libsource (lib "eagle-import") (part "FERRITE_BEAD0603"))
    )
    (comp (ref "J7")
      (value "MICRO_USB_B_HIROSE_ZX62R-B-5P")
      (footprint "eagle-import:USB_MICRO_B-HIROSE-ZX62R-B-5P")
      (libsource (lib "eagle-import") (part "MICRO_USB_B_HIROSE_ZX62R-B-5P"))
    )
    (comp (ref "J8")
      (value "MICRO_USB_B_HIROSE_ZX62R-B-5P")
      (footprint "eagle-import:USB_MICRO_B-HIROSE-ZX62R-B-5P")
      (libsource (lib "eagle-import") (part "MICRO_USB_B_HIROSE_ZX62R-B-5P"))
    )
    (comp (ref "LED10")
      (value "LED0603")
      (footprint "eagle-import:LED-0603")
      (libsource (lib "eagle-import") (part "LED0603"))
    )
    (comp (ref "LED11")
      (value "LED0603")
      (footprint "eagle-import:LED-0603")
      (libsource (lib "eagle-import") (part "LED0603"))
    )
    (comp (ref "LED12")
      (value "LED0603")
      (footprint "eagle-import:LED-0603")
      (libsource (lib "eagle-import") (part "LED0603"))
    )
    (comp (ref "LED13")
      (value "LED0603")
      (footprint "eagle-import:LED-0603")
      (libsource (lib "eagle-import") (part "LED0603"))
    )
    (comp (ref "Q6")
      (value "MOSFET-NCHANNELSMD")
      (footprint "eagle-import:SOT23-3")
      (libsource (lib "eagle-import") (part "MOSFET-NCHANNELSMD"))
    )
    (comp (ref "Q7")
      (value "MOSFET-NCHANNELSMD")
      (footprint "eagle-import:SOT23-3")
      (libsource (lib "eagle-import") (part "MOSFET-NCHANNELSMD"))
    )
    (comp (ref "Q8")
      (value "MOSFET-NCHANNELSMD")
      (footprint "eagle-import:SOT23-3")
      (libsource (lib "eagle-import") (part "MOSFET-NCHANNELSMD"))
    )
    (comp (ref "Q9")
      (value "MOSFET-NCHANNELSMD")
      (footprint "eagle-import:SOT23-3")
      (libsource (lib "eagle-import") (part "MOSFET-NCHANNELSMD"))
    )
    (comp (ref "R36")
      (value "1kΩ")
      (footprint "eagle-import:0603-RES")
      (libsource (lib "eagle-import") (part "RESISTOR0603_RES"))
    )
    (comp (ref "R37")
      (value "1kΩ")
      (footprint "eagle-import:0603-RES")
      (libsource (lib "eagle-import") (part "RESISTOR0603_RES"))
    )
    (comp (ref "R38")
      (value "1kΩ")
      (footprint "eagle-import:0603-RES")
      (libsource (lib "eagle-import") (part "RESISTOR0603_RES"))
    )
    (comp (ref "R39")
      (value "1kΩ")
      (footprint "eagle-import:0603-RES")
      (libsource (lib "eagle-import") (part "RESISTOR0603_RES"))
    )
    (comp (ref "TP12")
      (value "TEST_POINT_0.040IN")
      (footprint "eagle-import:TESTPOINT_0.040IN")
      (libsource (lib "eagle-import") (part "TEST_POINT_0.040IN"))
    )
    (comp (ref "TP13")
      (value "TEST_POINT_0.040IN")
      (footprint "eagle-import:TESTPOINT_0.040IN")
      (libsource (lib "eagle-import") (part "TEST_POINT_0.040IN"))
    )
    (comp (ref "TP14")
      (value "TEST_POINT_0.040IN")
      (footprint "eagle-import:TESTPOINT_0.040IN")
      (libsource (lib "eagle-import") (part "TEST_POINT_0.040IN"))
    )
    (comp (ref "TP15")
      (value "TEST_POINT_0.040IN")
      (footprint "eagle-import:TESTPOINT_0.040IN")
      (libsource (lib "eagle-import") (part "TEST_POINT_0.040IN"))
    )
    (comp (ref "U4")
      (value "FT232RQ")
      (footprint "eagle-import:QFN32")
      (libsource (lib "eagle-import") (part "FT232RQ"))
    )
    (comp (ref "U5")
      (value "FT232RQ")
      (footprint "eagle-import:QFN32")
      (libsource (lib "eagle-import") (part "FT232RQ"))
    )
    (comp (ref "C61")
      (value "100nF")
      (footprint "eagle-import:0603_CAP")
      (libsource (lib "eagle-import") (part "CAPACITOR0603_CAP"))
    )
    (comp (ref "J9")
      (value "MICRO_USB_B_HIROSE_ZX62R-B-5P")
      (footprint "eagle-import:USB_MICRO_B-HIROSE-ZX62R-B-5P")
      (libsource (lib "eagle-import") (part "MICRO_USB_B_HIROSE_ZX62R-B-5P"))
    )
    (comp (ref "Q1")
      (value "DMN32D2LDF")
      (footprint "eagle-import:SOT353")
      (libsource (lib "eagle-import") (part "DMN32D2LDF"))
    )
    (comp (ref "R89")
      (value "100kΩ")
      (footprint "eagle-import:0603-RES")
      (libsource (lib "eagle-import") (part "RESISTOR0603_RES"))
    )
    (comp (ref "R90")
      (value "100kΩ")
      (footprint "eagle-import:0603-RES")
      (libsource (lib "eagle-import") (part "RESISTOR0603_RES"))
    )
    (comp (ref "U23")
      (value "TS3USB30E")
      (footprint "eagle-import:UQFN-10")
      (libsource (lib "eagle-import") (part "TS3USB30E"))
    )
    (comp (ref "D1")
      (value "LED0603")
      (footprint "eagle-import:LED-0603")
      (libsource (lib "eagle-import") (part "LED0603"))
    )
    (comp (ref "D2")
      (value "LED0603")
      (footprint "eagle-import:LED-0603")
      (libsource (lib "eagle-import") (part "LED0603"))
    )
    (comp (ref "D3")
      (value "LED0603")
      (footprint "eagle-import:LED-0603")
      (libsource (lib "eagle-import") (part "LED0603"))
    )
    (comp (ref "D4")
      (value "LED0603")
      (footprint "eagle-import:LED-0603")
      (libsource (lib "eagle-import") (part "LED0603"))
    )
    (comp (ref "D5")
      (value "LED0603")
      (footprint "eagle-import:LED-0603")
      (libsource (lib "eagle-import") (part "LED0603"))
    )
    (comp (ref "D6")
      (value "LED0603")
      (footprint "eagle-import:LED-0603")
      (libsource (lib "eagle-import") (part "LED0603"))
    )
    (comp (ref "R16")
      (value "1kΩ")
      (footprint "eagle-import:0603-RES")
      (libsource (lib "eagle-import") (part "RESISTOR0603_RES"))
    )
    (comp (ref "R17")
      (value "1kΩ")
      (footprint "eagle-import:0603-RES")
      (libsource (lib "eagle-import") (part "RESISTOR0603_RES"))
    )
    (comp (ref "R18")
      (value "1kΩ")
      (footprint "eagle-import:0603-RES")
      (libsource (lib "eagle-import") (part "RESISTOR0603_RES"))
    )
    (comp (ref "R19")
      (value "1kΩ")
      (footprint "eagle-import:0603-RES")
      (libsource (lib "eagle-import") (part "RESISTOR0603_RES"))
    )
    (comp (ref "R20")
      (value "1kΩ")
      (footprint "eagle-import:0603-RES")
      (libsource (lib "eagle-import") (part "RESISTOR0603_RES"))
    )
    (comp (ref "R21")
      (value "1kΩ")
      (footprint "eagle-import:0603-RES")
      (libsource (lib "eagle-import") (part "RESISTOR0603_RES"))
    )
    (comp (ref "TP1")
      (value "TEST_POINT_0.040IN")
      (footprint "eagle-import:TESTPOINT_0.040IN")
      (libsource (lib "eagle-import") (part "TEST_POINT_0.040IN"))
    )
    (comp (ref "TP2")
      (value "TEST_POINT_0.040IN")
      (footprint "eagle-import:TESTPOINT_0.040IN")
      (libsource (lib "eagle-import") (part "TEST_POINT_0.040IN"))
    )
    (comp (ref "TP3")
      (value "TEST_POINT_0.040IN")
      (footprint "eagle-import:TESTPOINT_0.040IN")
      (libsource (lib "eagle-import") (part "TEST_POINT_0.040IN"))
    )
    (comp (ref "TP4")
      (value "TEST_POINT_0.040IN")
      (footprint "eagle-import:TESTPOINT_0.040IN")
      (libsource (lib "eagle-import") (part "TEST_POINT_0.040IN"))
    )
    (comp (ref "TP5")
      (value "TEST_POINT_0.040IN")
      (footprint "eagle-import:TESTPOINT_0.040IN")
      (libsource (lib "eagle-import") (part "TEST_POINT_0.040IN"))
    )
    (comp (ref "TP6")
      (value "TEST_POINT_0.040IN")
      (footprint "eagle-import:TESTPOINT_0.040IN")
      (libsource (lib "eagle-import") (part "TEST_POINT_0.040IN"))
    )
    (comp (ref "TP7")
      (value "TEST_POINT_0.040IN")
      (footprint "eagle-import:TESTPOINT_0.040IN")
      (libsource (lib "eagle-import") (part "TEST_POINT_0.040IN"))
    )
    (comp (ref "TP8")
      (value "TEST_POINT_0.040IN")
      (footprint "eagle-import:TESTPOINT_0.040IN")
      (libsource (lib "eagle-import") (part "TEST_POINT_0.040IN"))
    )
    (comp (ref "TP9")
      (value "TEST_POINT_0.040IN")
      (footprint "eagle-import:TESTPOINT_0.040IN")
      (libsource (lib "eagle-import") (part "TEST_POINT_0.040IN"))
    )
    (comp (ref "TP10")
      (value "TEST_POINT_0.040IN")
      (footprint "eagle-import:TESTPOINT_0.040IN")
      (libsource (lib "eagle-import") (part "TEST_POINT_0.040IN"))
    )
    (comp (ref "TP11")
      (value "TEST_POINT_0.040IN")
      (footprint "eagle-import:TESTPOINT_0.040IN")
      (libsource (lib "eagle-import") (part "TEST_POINT_0.040IN"))
    )
    (comp (ref "TP16")
      (value "TEST_POINT_0.040IN")
      (footprint "eagle-import:TESTPOINT_0.040IN")
      (libsource (lib "eagle-import") (part "TEST_POINT_0.040IN"))
    )
    (comp (ref "TP17")
      (value "TEST_POINT_0.040IN")
      (footprint "eagle-import:TESTPOINT_0.040IN")
      (libsource (lib "eagle-import") (part "TEST_POINT_0.040IN"))
    )
    (comp (ref "TP18")
      (value "TEST_POINT_0.040IN")
      (footprint "eagle-import:TESTPOINT_0.040IN")
      (libsource (lib "eagle-import") (part "TEST_POINT_0.040IN"))
    )
    (comp (ref "TP20")
      (value "TEST_POINT_0.040IN")
      (footprint "eagle-import:TESTPOINT_0.040IN")
      (libsource (lib "eagle-import") (part "TEST_POINT_0.040IN"))
    )
    (comp (ref "TP23")
      (value "TEST_POINT_0.040IN")
      (footprint "eagle-import:TESTPOINT_0.040IN")
      (libsource (lib "eagle-import") (part "TEST_POINT_0.040IN"))
    )
    (comp (ref "TP24")
      (value "TEST_POINT_0.040IN")
      (footprint "eagle-import:TESTPOINT_0.040IN")
      (libsource (lib "eagle-import") (part "TEST_POINT_0.040IN"))
    )
    (comp (ref "TP25")
      (value "TEST_POINT_0.040IN")
      (footprint "eagle-import:TESTPOINT_0.040IN")
      (libsource (lib "eagle-import") (part "TEST_POINT_0.040IN"))
    )
    (comp (ref "TP27")
      (value "TEST_POINT_0.040IN")
      (footprint "eagle-import:TESTPOINT_0.040IN")
      (libsource (lib "eagle-import") (part "TEST_POINT_0.040IN"))
    )
    (comp (ref "TP28")
      (value "TEST_POINT_0.040IN")
      (footprint "eagle-import:TESTPOINT_0.040IN")
      (libsource (lib "eagle-import") (part "TEST_POINT_0.040IN"))
    )
    (comp (ref "TP29")
      (value "TEST_POINT_0.040IN")
      (footprint "eagle-import:TESTPOINT_0.040IN")
      (libsource (lib "eagle-import") (part "TEST_POINT_0.040IN"))
    )
    (comp (ref "TP30")
      (value "TEST_POINT_0.040IN")
      (footprint "eagle-import:TESTPOINT_0.040IN")
      (libsource (lib "eagle-import") (part "TEST_POINT_0.040IN"))
    )
    (comp (ref "TP31")
      (value "TEST_POINT_0.040IN")
      (footprint "eagle-import:TESTPOINT_0.040IN")
      (libsource (lib "eagle-import") (part "TEST_POINT_0.040IN"))
    )
    (comp (ref "TP32")
      (value "TEST_POINT_0.040IN")
      (footprint "eagle-import:TESTPOINT_0.040IN")
      (libsource (lib "eagle-import") (part "TEST_POINT_0.040IN"))
    )
    (comp (ref "TP33")
      (value "TEST_POINT_0.040IN")
      (footprint "eagle-import:TESTPOINT_0.040IN")
      (libsource (lib "eagle-import") (part "TEST_POINT_0.040IN"))
    )
    (comp (ref "TP34")
      (value "TEST_POINT_0.040IN")
      (footprint "eagle-import:TESTPOINT_0.040IN")
      (libsource (lib "eagle-import") (part "TEST_POINT_0.040IN"))
    )
    (comp (ref "TP35")
      (value "TEST_POINT_0.040IN")
      (footprint "eagle-import:TESTPOINT_0.040IN")
      (libsource (lib "eagle-import") (part "TEST_POINT_0.040IN"))
    )
    (comp (ref "TP36")
      (value "TEST_POINT_0.040IN")
      (footprint "eagle-import:TESTPOINT_0.040IN")
      (libsource (lib "eagle-import") (part "TEST_POINT_0.040IN"))
    )
    (comp (ref "TP37")
      (value "TEST_POINT_0.040IN")
      (footprint "eagle-import:TESTPOINT_0.040IN")
      (libsource (lib "eagle-import") (part "TEST_POINT_0.040IN"))
    )
    (comp (ref "TP41")
      (value "TEST_POINT_0.040IN")
      (footprint "eagle-import:TESTPOINT_0.040IN")
      (libsource (lib "eagle-import") (part "TEST_POINT_0.040IN"))
    )
    (comp (ref "TP42")
      (value "TEST_POINT_0.040IN")
      (footprint "eagle-import:TESTPOINT_0.040IN")
      (libsource (lib "eagle-import") (part "TEST_POINT_0.040IN"))
    )
    (comp (ref "TP43")
      (value "TEST_POINT_0.040IN")
      (footprint "eagle-import:TESTPOINT_0.040IN")
      (libsource (lib "eagle-import") (part "TEST_POINT_0.040IN"))
    )
    (comp (ref "TP44")
      (value "TEST_POINT_0.040IN")
      (footprint "eagle-import:TESTPOINT_0.040IN")
      (libsource (lib "eagle-import") (part "TEST_POINT_0.040IN"))
    )
    (comp (ref "TP45")
      (value "TEST_POINT_0.040IN")
      (footprint "eagle-import:TESTPOINT_0.040IN")
      (libsource (lib "eagle-import") (part "TEST_POINT_0.040IN"))
    )
    (comp (ref "TP46")
      (value "TEST_POINT_0.040IN")
      (footprint "eagle-import:TESTPOINT_0.040IN")
      (libsource (lib "eagle-import") (part "TEST_POINT_0.040IN"))
    )
    (comp (ref "TP47")
      (value "TEST_POINT_0.040IN")
      (footprint "eagle-import:TESTPOINT_0.040IN")
      (libsource (lib "eagle-import") (part "TEST_POINT_0.040IN"))
    )
    (comp (ref "TP48")
      (value "TEST_POINT_0.040IN")
      (footprint "eagle-import:TESTPOINT_0.040IN")
      (libsource (lib "eagle-import") (part "TEST_POINT_0.040IN"))
    )
    (comp (ref "TP49")
      (value "TEST_POINT_0.040IN")
      (footprint "eagle-import:TESTPOINT_0.040IN")
      (libsource (lib "eagle-import") (part "TEST_POINT_0.040IN"))
    )
    (comp (ref "TP50")
      (value "TEST_POINT_0.040IN")
      (footprint "eagle-import:TESTPOINT_0.040IN")
      (libsource (lib "eagle-import") (part "TEST_POINT_0.040IN"))
    )
    (comp (ref "TP51")
      (value "TEST_POINT_0.040IN")
      (footprint "eagle-import:TESTPOINT_0.040IN")
      (libsource (lib "eagle-import") (part "TEST_POINT_0.040IN"))
    )
    (comp (ref "TP52")
      (value "TEST_POINT_0.040IN")
      (footprint "eagle-import:TESTPOINT_0.040IN")
      (libsource (lib "eagle-import") (part "TEST_POINT_0.040IN"))
    )
    (comp (ref "TP53")
      (value "TEST_POINT_0.040IN")
      (footprint "eagle-import:TESTPOINT_0.040IN")
      (libsource (lib "eagle-import") (part "TEST_POINT_0.040IN"))
    )
    (comp (ref "TP55")
      (value "TEST_POINT_0.040IN")
      (footprint "eagle-import:TESTPOINT_0.040IN")
      (libsource (lib "eagle-import") (part "TEST_POINT_0.040IN"))
    )
    (comp (ref "TP56")
      (value "TEST_POINT_0.040IN")
      (footprint "eagle-import:TESTPOINT_0.040IN")
      (libsource (lib "eagle-import") (part "TEST_POINT_0.040IN"))
    )
    (comp (ref "TP57")
      (value "TEST_POINT_0.040IN")
      (footprint "eagle-import:TESTPOINT_0.040IN")
      (libsource (lib "eagle-import") (part "TEST_POINT_0.040IN"))
    )
    (comp (ref "TP58")
      (value "TEST_POINT_0.040IN")
      (footprint "eagle-import:TESTPOINT_0.040IN")
      (libsource (lib "eagle-import") (part "TEST_POINT_0.040IN"))
    )
    (comp (ref "TP1001")
      (value "TEST_POINT_0.040IN")
      (footprint "eagle-import:TESTPOINT_0.040IN")
      (libsource (lib "eagle-import") (part "TEST_POINT_0.040IN"))
    )
    (comp (ref "TP1002")
      (value "TEST_POINT_0.040IN")
      (footprint "eagle-import:TESTPOINT_0.040IN")
      (libsource (lib "eagle-import") (part "TEST_POINT_0.040IN"))
    )
    (comp (ref "TP1003")
      (value "TEST_POINT_0.040IN")
      (footprint "eagle-import:TESTPOINT_0.040IN")
      (libsource (lib "eagle-import") (part "TEST_POINT_0.040IN"))
    )
    (comp (ref "TP1004")
      (value "TEST_POINT_0.040IN")
      (footprint "eagle-import:TESTPOINT_0.040IN")
      (libsource (lib "eagle-import") (part "TEST_POINT_0.040IN"))
    )
    (comp (ref "TP1005")
      (value "TEST_POINT_0.040IN")
      (footprint "eagle-import:TESTPOINT_0.040IN")
      (libsource (lib "eagle-import") (part "TEST_POINT_0.040IN"))
    )
    (comp (ref "TP1006")
      (value "TEST_POINT_0.040IN")
      (footprint "eagle-import:TESTPOINT_0.040IN")
      (libsource (lib "eagle-import") (part "TEST_POINT_0.040IN"))
    )
    (comp (ref "C11")
      (value "0.01uF")
      (footprint "eagle-import:0402_CAP")
      (libsource (lib "eagle-import") (part "CAPACITOR0402_CAP"))
    )
    (comp (ref "C12")
      (value "0.1uF")
      (footprint "eagle-import:0402_CAP")
      (libsource (lib "eagle-import") (part "CAPACITOR0402_CAP"))
    )
    (comp (ref "C13")
      (value "0.1uF")
      (footprint "eagle-import:0402_CAP")
      (libsource (lib "eagle-import") (part "CAPACITOR0402_CAP"))
    )
    (comp (ref "C14")
      (value "0.1uF")
      (footprint "eagle-import:0402_CAP")
      (libsource (lib "eagle-import") (part "CAPACITOR0402_CAP"))
    )
    (comp (ref "C15")
      (value "0.1uF")
      (footprint "eagle-import:0402_CAP")
      (libsource (lib "eagle-import") (part "CAPACITOR0402_CAP"))
    )
    (comp (ref "C62")
      (value "2.2uF")
      (footprint "eagle-import:0603_CAP")
      (libsource (lib "eagle-import") (part "CAPACITOR0603_CAP"))
    )
    (comp (ref "C63")
      (value "2.2uF")
      (footprint "eagle-import:0603_CAP")
      (libsource (lib "eagle-import") (part "CAPACITOR0603_CAP"))
    )
    (comp (ref "J11")
      (value "PJ-102AH")
      (footprint "eagle-import:PJ-102AH")
      (libsource (lib "eagle-import") (part "PJ-102AH"))
    )
    (comp (ref "R2")
      (value "0.017Ω")
      (footprint "eagle-import:0805_RES")
      (libsource (lib "eagle-import") (part "RESISTOR0805_RES"))
    )
    (comp (ref "R3")
      (value "0.017Ω")
      (footprint "eagle-import:0805_RES")
      (libsource (lib "eagle-import") (part "RESISTOR0805_RES"))
    )
    (comp (ref "R4")
      (value "0.017Ω")
      (footprint "eagle-import:0805_RES")
      (libsource (lib "eagle-import") (part "RESISTOR0805_RES"))
    )
    (comp (ref "R5")
      (value "0.017Ω")
      (footprint "eagle-import:0805_RES")
      (libsource (lib "eagle-import") (part "RESISTOR0805_RES"))
    )
    (comp (ref "R43")
      (value "2kΩ")
      (footprint "eagle-import:0402_RES")
      (libsource (lib "eagle-import") (part "RESISTOR0402_RES"))
    )
    (comp (ref "R44")
      (value "2kΩ")
      (footprint "eagle-import:0402_RES")
      (libsource (lib "eagle-import") (part "RESISTOR0402_RES"))
    )
    (comp (ref "R45")
      (value "2kΩ")
      (footprint "eagle-import:0402_RES")
      (libsource (lib "eagle-import") (part "RESISTOR0402_RES"))
    )
    (comp (ref "R46")
      (value "2kΩ")
      (footprint "eagle-import:0402_RES")
      (libsource (lib "eagle-import") (part "RESISTOR0402_RES"))
    )
    (comp (ref "R47")
      (value "2kΩ")
      (footprint "eagle-import:0402_RES")
      (libsource (lib "eagle-import") (part "RESISTOR0402_RES"))
    )
    (comp (ref "R48")
      (value "2kΩ")
      (footprint "eagle-import:0402_RES")
      (libsource (lib "eagle-import") (part "RESISTOR0402_RES"))
    )
    (comp (ref "R49")
      (value "2kΩ")
      (footprint "eagle-import:0402_RES")
      (libsource (lib "eagle-import") (part "RESISTOR0402_RES"))
    )
    (comp (ref "R50")
      (value "2kΩ")
      (footprint "eagle-import:0402_RES")
      (libsource (lib "eagle-import") (part "RESISTOR0402_RES"))
    )
    (comp (ref "R51")
      (value "2kΩ")
      (footprint "eagle-import:0402_RES")
      (libsource (lib "eagle-import") (part "RESISTOR0402_RES"))
    )
    (comp (ref "R52")
      (value "2kΩ")
      (footprint "eagle-import:0402_RES")
      (libsource (lib "eagle-import") (part "RESISTOR0402_RES"))
    )
    (comp (ref "R53")
      (value "2kΩ")
      (footprint "eagle-import:0402_RES")
      (libsource (lib "eagle-import") (part "RESISTOR0402_RES"))
    )
    (comp (ref "R54")
      (value "2kΩ")
      (footprint "eagle-import:0402_RES")
      (libsource (lib "eagle-import") (part "RESISTOR0402_RES"))
    )
    (comp (ref "R70")
      (value "10kΩ")
      (footprint "eagle-import:0603-RES")
      (libsource (lib "eagle-import") (part "RESISTOR0603_RES"))
    )
    (comp (ref "U8")
      (value "LTC2941")
      (footprint "eagle-import:DFN-6-2MMX3MM")
      (libsource (lib "eagle-import") (part "LTC2941"))
    )
    (comp (ref "U9")
      (value "LTC2941")
      (footprint "eagle-import:DFN-6-2MMX3MM")
      (libsource (lib "eagle-import") (part "LTC2941"))
    )
    (comp (ref "U10")
      (value "LTC2941")
      (footprint "eagle-import:DFN-6-2MMX3MM")
      (libsource (lib "eagle-import") (part "LTC2941"))
    )
    (comp (ref "U11")
      (value "LTC2941")
      (footprint "eagle-import:DFN-6-2MMX3MM")
      (libsource (lib "eagle-import") (part "LTC2941"))
    )
    (comp (ref "U12")
      (value "MAX8887EZK33+T")
      (footprint "eagle-import:SOT-23-5")
      (libsource (lib "eagle-import") (part "MAX8887EZK33+T"))
    )
    (comp (ref "U15")
      (value "PCA9544AQFN-N20")
      (footprint "eagle-import:QFN-N20")
      (libsource (lib "eagle-import") (part "PCA9544AQFN-N20"))
    )
  )
  (nets
    (net (code "1") (name "3V3") (class "Default")
      (node (ref "C42") (pin "1") (pinfunction "1_1") (pintype "bidirectional"))
      (node (ref "C43") (pin "1") (pinfunction "1_1") (pintype "bidirectional"))
      (node (ref "C44") (pin "1") (pinfunction "1_1") (pintype "bidirectional"))
      (node (ref "C63") (pin "1") (pinfunction "1_1") (pintype "bidirectional"))
      (node (ref "FB6") (pin "2") (pinfunction "P$2_2") (pintype "bidirectional"))
      (node (ref "LED1") (pin "A") (pinfunction "ANODE_A") (pintype "bidirectional"))
      (node (ref "LED10") (pin "A") (pinfunction "ANODE_A") (pintype "bidirectional"))
      (node (ref "LED11") (pin "A") (pinfunction "ANODE_A") (pintype "bidirectional"))
      (node (ref "LED12") (pin "A") (pinfunction "ANODE_A") (pintype "bidirectional"))
      (node (ref "LED13") (pin "A") (pinfunction "ANODE_A") (pintype "bidirectional"))
      (node (ref "LED2") (pin "A") (pinfunction "ANODE_A") (pintype "bidirectional"))
      (node (ref "LED3") (pin "A") (pinfunction "ANODE_A") (pintype "bidirectional"))
      (node (ref "LED4") (pin "A") (pinfunction "ANODE_A") (pintype "bidirectional"))
      (node (ref "R2") (pin "2") (pinfunction "2_2") (pintype "passive"))
      (node (ref "R43") (pin "2") (pinfunction "2_2") (pintype "passive"))
      (node (ref "R44") (pin "2") (pinfunction "2_2") (pintype "passive"))
      (node (ref "R45") (pin "2") (pinfunction "2_2") (pintype "passive"))
      (node (ref "R71") (pin "2") (pinfunction "2_2") (pintype "passive"))
      (node (ref "R87") (pin "2") (pinfunction "2_2") (pintype "passive"))
      (node (ref "R88") (pin "2") (pinfunction "2_2") (pintype "passive"))
      (node (ref "S11") (pin "C") (pinfunction "INPUT_C") (pintype "bidirectional"))
      (node (ref "S14") (pin "14") (pinfunction "VCC_14") (pintype "bidirectional"))
      (node (ref "S15") (pin "14") (pinfunction "VCC_14") (pintype "bidirectional"))
      (node (ref "S16") (pin "10") (pinfunction "A_10") (pintype "bidirectional"))
      (node (ref "S16") (pin "14") (pinfunction "VCC_14") (pintype "bidirectional"))
      (node (ref "S17") (pin "10") (pinfunction "A_10") (pintype "bidirectional"))
      (node (ref "S17") (pin "14") (pinfunction "VCC_14") (pintype "bidirectional"))
      (node (ref "S18") (pin "10") (pinfunction "A_10") (pintype "bidirectional"))
      (node (ref "S18") (pin "14") (pinfunction "VCC_14") (pintype "bidirectional"))
      (node (ref "TP7") (pin "TESTPOINT") (pinfunction "TESTPOINT_TESTPOINT") (pintype "bidirectional"))
      (node (ref "U12") (pin "5") (pinfunction "OUT_5") (pintype "bidirectional"))
      (node (ref "U16") (pin "27") (pinfunction "VLCD_27") (pintype "bidirectional"))
      (node (ref "U16") (pin "31") (pinfunction "VLCDIN_31") (pintype "power_in"))
      (node (ref "U16") (pin "40") (pinfunction "VDDIO_40") (pintype "power_in"))
      (node (ref "U16") (pin "45") (pinfunction "VDDIO_45") (pintype "power_in"))
      (node (ref "U16") (pin "8") (pinfunction "VDDIN_8") (pintype "power_in"))
      (node (ref "U8") (pin "1") (pinfunction "SENSE+_1") (pintype "open_collector"))
    )
    (net (code "2") (name "5V") (class "Default")
      (node (ref "C62") (pin "1") (pinfunction "1_1") (pintype "bidirectional"))
      (node (ref "J11") (pin "1") (pinfunction "VCC_1") (pintype "bidirectional"))
      (node (ref "R3") (pin "2") (pinfunction "2_2") (pintype "passive"))
      (node (ref "R4") (pin "2") (pinfunction "2_2") (pintype "passive"))
      (node (ref "R46") (pin "2") (pinfunction "2_2") (pintype "passive"))
      (node (ref "R47") (pin "2") (pinfunction "2_2") (pintype "passive"))
      (node (ref "R48") (pin "2") (pinfunction "2_2") (pintype "passive"))
      (node (ref "R49") (pin "2") (pinfunction "2_2") (pintype "passive"))
      (node (ref "R5") (pin "2") (pinfunction "2_2") (pintype "passive"))
      (node (ref "R50") (pin "2") (pinfunction "2_2") (pintype "passive"))
      (node (ref "R51") (pin "2") (pinfunction "2_2") (pintype "passive"))
      (node (ref "R52") (pin "2") (pinfunction "2_2") (pintype "passive"))
      (node (ref "R53") (pin "2") (pinfunction "2_2") (pintype "passive"))
      (node (ref "R54") (pin "2") (pinfunction "2_2") (pintype "passive"))
      (node (ref "R70") (pin "2") (pinfunction "2_2") (pintype "passive"))
      (node (ref "TP4") (pin "TESTPOINT") (pinfunction "TESTPOINT_TESTPOINT") (pintype "bidirectional"))
      (node (ref "U10") (pin "1") (pinfunction "SENSE+_1") (pintype "open_collector"))
      (node (ref "U11") (pin "1") (pinfunction "SENSE+_1") (pintype "open_collector"))
      (node (ref "U12") (pin "1") (pinfunction "IN_1") (pintype "bidirectional"))
      (node (ref "U9") (pin "1") (pinfunction "SENSE+_1") (pintype "open_collector"))
    )
    (net (code "3") (name "CONT0_DBG_GPIO1") (class "Default")
      (node (ref "J1") (pin "101") (pinfunction "DBG_GPIO1_101") (pintype "bidirectional"))
      (node (ref "Q6") (pin "1") (pinfunction "G_1") (pintype "passive"))
      (node (ref "TP12") (pin "TESTPOINT") (pinfunction "TESTPOINT_TESTPOINT") (pintype "bidirectional"))
    )
    (net (code "4") (name "CONT0_DBG_GPIO2") (class "Default")
      (node (ref "J1") (pin "104") (pinfunction "DBG_GPIO2_104") (pintype "bidirectional"))
      (node (ref "Q7") (pin "1") (pinfunction "G_1") (pintype "passive"))
      (node (ref "TP13") (pin "TESTPOINT") (pinfunction "TESTPOINT_TESTPOINT") (pintype "bidirectional"))
    )
    (net (code "5") (name "CONT0_DBG_RX") (class "Default")
      (node (ref "J1") (pin "103") (pinfunction "DBG_RX_103") (pintype "bidirectional"))
      (node (ref "U4") (pin "30") (pinfunction "TXD_30") (pintype "output"))
    )
    (net (code "6") (name "CONT0_DBG_TX") (class "Default")
      (node (ref "J1") (pin "102") (pinfunction "DBG_TX_102") (pintype "bidirectional"))
      (node (ref "U4") (pin "2") (pinfunction "RXD_2") (pintype "input"))
    )
    (net (code "7") (name "CONT0_SWDCLK") (class "Default")
      (node (ref "J1") (pin "106") (pinfunction "DBG_SWDCLK_106") (pintype "bidirectional"))
      (node (ref "S17") (pin "3") (pinfunction "A_3") (pintype "bidirectional"))
    )
    (net (code "8") (name "CONT0_SWDIO") (class "Default")
      (node (ref "J1") (pin "107") (pinfunction "DBG_SWDIO_107") (pintype "bidirectional"))
      (node (ref "S17") (pin "2") (pinfunction "A_2") (pintype "bidirectional"))
    )
    (net (code "9") (name "CONT0_~{RESET}") (class "Default")
      (node (ref "J1") (pin "105") (pinfunction "DBG_~{RESET}_105") (pintype "bidirectional"))
      (node (ref "S17") (pin "9") (pinfunction "A_9") (pintype "bidirectional"))
      (node (ref "S6") (pin "2") (pinfunction "P$2_2") (pintype "passive"))
    )
    (net (code "10") (name "CONT1_DBG_GPIO1") (class "Default")
      (node (ref "J1") (pin "201") (pinfunction "DBG_GPIO1_201") (pintype "bidirectional"))
      (node (ref "Q8") (pin "1") (pinfunction "G_1") (pintype "passive"))
      (node (ref "TP14") (pin "TESTPOINT") (pinfunction "TESTPOINT_TESTPOINT") (pintype "bidirectional"))
    )
    (net (code "11") (name "CONT1_DBG_GPIO2") (class "Default")
      (node (ref "J1") (pin "204") (pinfunction "DBG_GPIO2_204") (pintype "bidirectional"))
      (node (ref "Q9") (pin "1") (pinfunction "G_1") (pintype "passive"))
      (node (ref "TP15") (pin "TESTPOINT") (pinfunction "TESTPOINT_TESTPOINT") (pintype "bidirectional"))
    )
    (net (code "12") (name "CONT1_DBG_RX") (class "Default")
      (node (ref "J1") (pin "203") (pinfunction "DBG_RX_203") (pintype "bidirectional"))
      (node (ref "U5") (pin "30") (pinfunction "TXD_30") (pintype "output"))
    )
    (net (code "13") (name "CONT1_DBG_TX") (class "Default")
      (node (ref "J1") (pin "202") (pinfunction "DBG_TX_202") (pintype "bidirectional"))
      (node (ref "U5") (pin "2") (pinfunction "RXD_2") (pintype "input"))
    )
    (net (code "14") (name "CONT1_SWDCLK") (class "Default")
      (node (ref "J1") (pin "206") (pinfunction "DBG_SWDCLK_206") (pintype "bidirectional"))
      (node (ref "S18") (pin "3") (pinfunction "A_3") (pintype "bidirectional"))
    )
    (net (code "15") (name "CONT1_SWDIO") (class "Default")
      (node (ref "J1") (pin "207") (pinfunction "DBG_SWDIO_207") (pintype "bidirectional"))
      (node (ref "S18") (pin "2") (pinfunction "A_2") (pintype "bidirectional"))
    )
    (net (code "16") (name "CONT1_~{RESET}") (class "Default")
      (node (ref "J1") (pin "205") (pinfunction "DBG_~{RESET}_205") (pintype "bidirectional"))
      (node (ref "S18") (pin "9") (pinfunction "A_9") (pintype "bidirectional"))
      (node (ref "S7") (pin "2") (pinfunction "P$2_2") (pintype "passive"))
    )
    (net (code "17") (name "CONTROLLER_XIN") (class "Default")
      (node (ref "C1") (pin "1") (pinfunction "1_1") (pintype "bidirectional"))
      (node (ref "U16") (pin "1") (pinfunction "PA00_1") (pintype "bidirectional"))
      (node (ref "X1") (pin "3") (pinfunction "2_3") (pintype "bidirectional"))
    )
    (net (code "18") (name "CONTROLLER_XOUT") (class "Default")
      (node (ref "C2") (pin "1") (pinfunction "1_1") (pintype "bidirectional"))
      (node (ref "U16") (pin "2") (pinfunction "PA01_2") (pintype "bidirectional"))
      (node (ref "X1") (pin "1") (pinfunction "1_1") (pintype "bidirectional"))
    )
    (net (code "19") (name "CONT_MOD0_IN") (class "Default")
      (node (ref "J1") (pin "9") (pinfunction "MOD0_IN_9") (pintype "bidirectional"))
      (node (ref "U17") (pin "2") (pinfunction "A1_2") (pintype "bidirectional"))
    )
    (net (code "20") (name "CONT_MOD0_OUT") (class "Default")
      (node (ref "J1") (pin "10") (pinfunction "MOD0_OUT_10") (pintype "bidirectional"))
      (node (ref "U19") (pin "2") (pinfunction "A1_2") (pintype "bidirectional"))
    )
    (net (code "21") (name "CONT_MOD1_IN") (class "Default")
      (node (ref "J1") (pin "11") (pinfunction "MOD1_IN_11") (pintype "bidirectional"))
      (node (ref "U18") (pin "2") (pinfunction "A1_2") (pintype "bidirectional"))
    )
    (net (code "22") (name "CONT_MOD1_OUT") (class "Default")
      (node (ref "J1") (pin "12") (pinfunction "MOD1_OUT_12") (pintype "bidirectional"))
      (node (ref "U20") (pin "2") (pinfunction "A1_2") (pintype "bidirectional"))
    )
    (net (code "23") (name "CONT_MOD2_IN") (class "Default")
      (node (ref "J1") (pin "13") (pinfunction "MOD2_IN_13") (pintype "bidirectional"))
      (node (ref "U16") (pin "39") (pinfunction "PA20_39") (pintype "bidirectional"))
    )
    (net (code "24") (name "CONT_MOD2_OUT") (class "Default")
      (node (ref "J1") (pin "14") (pinfunction "MOD2_OUT_14") (pintype "bidirectional"))
      (node (ref "U16") (pin "38") (pinfunction "PA19_38") (pintype "bidirectional"))
    )
    (net (code "25") (name "CONT_USB+") (class "Default")
      (node (ref "J1") (pin "27") (pinfunction "USB_D+_27") (pintype "bidirectional"))
      (node (ref "U23") (pin "2") (pinfunction "D2+_2") (pintype "bidirectional"))
    )
    (net (code "26") (name "CONT_USB-") (class "Default")
      (node (ref "J1") (pin "28") (pinfunction "USB_D-_28") (pintype "bidirectional"))
      (node (ref "U23") (pin "6") (pinfunction "D2-_6") (pintype "bidirectional"))
    )
    (net (code "27") (name "GND") (class "Default")
      (node (ref "C1") (pin "2") (pinfunction "2_2") (pintype "bidirectional"))
      (node (ref "C10") (pin "2") (pinfunction "2_2") (pintype "bidirectional"))
      (node (ref "C11") (pin "2") (pinfunction "2_2") (pintype "bidirectional"))
      (node (ref "C12") (pin "2") (pinfunction "2_2") (pintype "bidirectional"))
      (node (ref "C13") (pin "2") (pinfunction "2_2") (pintype "bidirectional"))
      (node (ref "C14") (pin "2") (pinfunction "2_2") (pintype "bidirectional"))
      (node (ref "C15") (pin "2") (pinfunction "2_2") (pintype "bidirectional"))
      (node (ref "C16") (pin "2") (pinfunction "2_2") (pintype "bidirectional"))
      (node (ref "C17") (pin "2") (pinfunction "2_2") (pintype "bidirectional"))
      (node (ref "C18") (pin "2") (pinfunction "2_2") (pintype "bidirectional"))
      (node (ref "C19") (pin "2") (pinfunction "2_2") (pintype "bidirectional"))
      (node (ref "C2") (pin "2") (pinfunction "2_2") (pintype "bidirectional"))
      (node (ref "C20") (pin "2") (pinfunction "2_2") (pintype "bidirectional"))
      (node (ref "C21") (pin "2") (pinfunction "2_2") (pintype "bidirectional"))
      (node (ref "C22") (pin "2") (pinfunction "2_2") (pintype "bidirectional"))
      (node (ref "C23") (pin "2") (pinfunction "2_2") (pintype "bidirectional"))
      (node (ref "C24") (pin "2") (pinfunction "2_2") (pintype "bidirectional"))
      (node (ref "C25") (pin "2") (pinfunction "2_2") (pintype "bidirectional"))
      (node (ref "C26") (pin "2") (pinfunction "2_2") (pintype "bidirectional"))
      (node (ref "C27") (pin "2") (pinfunction "2_2") (pintype "bidirectional"))
      (node (ref "C28") (pin "1") (pinfunction "1_1") (pintype "bidirectional"))
      (node (ref "C29") (pin "2") (pinfunction "2_2") (pintype "bidirectional"))
      (node (ref "C3") (pin "1") (pinfunction "1_1") (pintype "bidirectional"))
      (node (ref "C30") (pin "2") (pinfunction "2_2") (pintype "bidirectional"))
      (node (ref "C31") (pin "2") (pinfunction "2_2") (pintype "bidirectional"))
      (node (ref "C32") (pin "2") (pinfunction "2_2") (pintype "bidirectional"))
      (node (ref "C33") (pin "2") (pinfunction "2_2") (pintype "bidirectional"))
      (node (ref "C34") (pin "2") (pinfunction "2_2") (pintype "bidirectional"))
      (node (ref "C35") (pin "2") (pinfunction "2_2") (pintype "bidirectional"))
      (node (ref "C36") (pin "2") (pinfunction "2_2") (pintype "bidirectional"))
      (node (ref "C37") (pin "1") (pinfunction "1_1") (pintype "bidirectional"))
      (node (ref "C38") (pin "1") (pinfunction "1_1") (pintype "bidirectional"))
      (node (ref "C39") (pin "2") (pinfunction "2_2") (pintype "bidirectional"))
      (node (ref "C4") (pin "1") (pinfunction "1_1") (pintype "bidirectional"))
      (node (ref "C40") (pin "2") (pinfunction "2_2") (pintype "bidirectional"))
      (node (ref "C41") (pin "2") (pinfunction "2_2") (pintype "bidirectional"))
      (node (ref "C42") (pin "2") (pinfunction "2_2") (pintype "bidirectional"))
      (node (ref "C43") (pin "2") (pinfunction "2_2") (pintype "bidirectional"))
      (node (ref "C44") (pin "2") (pinfunction "2_2") (pintype "bidirectional"))
      (node (ref "C45") (pin "2") (pinfunction "2_2") (pintype "bidirectional"))
      (node (ref "C46") (pin "2") (pinfunction "2_2") (pintype "bidirectional"))
      (node (ref "C47") (pin "2") (pinfunction "2_2") (pintype "bidirectional"))
      (node (ref "C48") (pin "2") (pinfunction "2_2") (pintype "bidirectional"))
      (node (ref "C49") (pin "2") (pinfunction "2_2") (pintype "bidirectional"))
      (node (ref "C5") (pin "2") (pinfunction "2_2") (pintype "bidirectional"))
      (node (ref "C50") (pin "2") (pinfunction "2_2") (pintype "bidirectional"))
      (node (ref "C51") (pin "2") (pinfunction "2_2") (pintype "bidirectional"))
      (node (ref "C52") (pin "2") (pinfunction "2_2") (pintype "bidirectional"))
      (node (ref "C53") (pin "2") (pinfunction "2_2") (pintype "bidirectional"))
      (node (ref "C54") (pin "2") (pinfunction "2_2") (pintype "bidirectional"))
      (node (ref "C55") (pin "2") (pinfunction "2_2") (pintype "bidirectional"))
      (node (ref "C56") (pin "2") (pinfunction "2_2") (pintype "bidirectional"))
      (node (ref "C57") (pin "2") (pinfunction "2_2") (pintype "bidirectional"))
      (node (ref "C58") (pin "2") (pinfunction "2_2") (pintype "bidirectional"))
      (node (ref "C59") (pin "2") (pinfunction "2_2") (pintype "bidirectional"))
      (node (ref "C6") (pin "2") (pinfunction "2_2") (pintype "bidirectional"))
      (node (ref "C60") (pin "2") (pinfunction "2_2") (pintype "bidirectional"))
      (node (ref "C61") (pin "1") (pinfunction "1_1") (pintype "bidirectional"))
      (node (ref "C62") (pin "2") (pinfunction "2_2") (pintype "bidirectional"))
      (node (ref "C63") (pin "2") (pinfunction "2_2") (pintype "bidirectional"))
      (node (ref "C64") (pin "2") (pinfunction "2_2") (pintype "bidirectional"))
      (node (ref "C65") (pin "2") (pinfunction "2_2") (pintype "bidirectional"))
      (node (ref "C66") (pin "1") (pinfunction "1_1") (pintype "bidirectional"))
      (node (ref "C67") (pin "2") (pinfunction "2_2") (pintype "bidirectional"))
      (node (ref "C68") (pin "2") (pinfunction "2_2") (pintype "bidirectional"))
      (node (ref "C69") (pin "2") (pinfunction "2_2") (pintype "bidirectional"))
      (node (ref "C7") (pin "2") (pinfunction "2_2") (pintype "bidirectional"))
      (node (ref "C8") (pin "2") (pinfunction "2_2") (pintype "bidirectional"))
      (node (ref "C9") (pin "2") (pinfunction "2_2") (pintype "bidirectional"))
      (node (ref "D7") (pin "1") (pinfunction "GND_1") (pintype "bidirectional"))
      (node (ref "D7") (pin "3") (pinfunction "GND_3") (pintype "bidirectional"))
      (node (ref "D7") (pin "5") (pinfunction "GND_5") (pintype "bidirectional"))
      (node (ref "D7") (pin "7") (pinfunction "GND_7") (pintype "bidirectional"))
      (node (ref "D8") (pin "1") (pinfunction "GND_1") (pintype "bidirectional"))
      (node (ref "D8") (pin "3") (pinfunction "GND_3") (pintype "bidirectional"))
      (node (ref "D8") (pin "5") (pinfunction "GND_5") (pintype "bidirectional"))
      (node (ref "D8") (pin "7") (pinfunction "GND_7") (pintype "bidirectional"))
      (node (ref "J1") (pin "1") (pinfunction "GND_1") (pintype "bidirectional"))
      (node (ref "J1") (pin "100") (pinfunction "GND1_100") (pintype "bidirectional"))
      (node (ref "J1") (pin "200") (pinfunction "GND1_200") (pintype "bidirectional"))
      (node (ref "J1") (pin "21") (pinfunction "GND_21") (pintype "bidirectional"))
      (node (ref "J1") (pin "MNT1") (pinfunction "GND_MNT1") (pintype "bidirectional"))
      (node (ref "J1") (pin "MNT2") (pinfunction "GND_MNT2") (pintype "bidirectional"))
      (node (ref "J1") (pin "MNT3") (pinfunction "GND_MNT3") (pintype "bidirectional"))
      (node (ref "J1") (pin "MNT4") (pinfunction "GND_MNT4") (pintype "bidirectional"))
      (node (ref "J10") (pin "10") (pinfunction "10_10") (pintype "passive"))
      (node (ref "J10") (pin "12") (pinfunction "12_12") (pintype "passive"))
      (node (ref "J10") (pin "14") (pinfunction "14_14") (pintype "passive"))
      (node (ref "J10") (pin "16") (pinfunction "16_16") (pintype "passive"))
      (node (ref "J10") (pin "18") (pinfunction "18_18") (pintype "passive"))
      (node (ref "J10") (pin "20") (pinfunction "20_20") (pintype "passive"))
      (node (ref "J10") (pin "4") (pinfunction "4_4") (pintype "passive"))
      (node (ref "J10") (pin "6") (pinfunction "6_6") (pintype "passive"))
      (node (ref "J10") (pin "8") (pinfunction "8_8") (pintype "passive"))
      (node (ref "J11") (pin "2") (pinfunction "GND_2") (pintype "bidirectional"))
      (node (ref "J2") (pin "1") (pinfunction "GND_1") (pintype "bidirectional"))
      (node (ref "J2") (pin "14") (pinfunction "GND_14") (pintype "bidirectional"))
      (node (ref "J2") (pin "15") (pinfunction "GND_15") (pintype "bidirectional"))
      (node (ref "J2") (pin "MNT1") (pinfunction "GND_MNT1") (pintype "bidirectional"))
      (node (ref "J2") (pin "MNT2") (pinfunction "GND_MNT2") (pintype "bidirectional"))
      (node (ref "J2") (pin "MNT3") (pinfunction "GND_MNT3") (pintype "bidirectional"))
      (node (ref "J2") (pin "MNT4") (pinfunction "GND_MNT4") (pintype "bidirectional"))
      (node (ref "J3") (pin "1") (pinfunction "GND_1") (pintype "bidirectional"))
      (node (ref "J3") (pin "14") (pinfunction "GND_14") (pintype "bidirectional"))
      (node (ref "J3") (pin "15") (pinfunction "GND_15") (pintype "bidirectional"))
      (node (ref "J3") (pin "MNT1") (pinfunction "GND_MNT1") (pintype "bidirectional"))
      (node (ref "J3") (pin "MNT2") (pinfunction "GND_MNT2") (pintype "bidirectional"))
      (node (ref "J3") (pin "MNT3") (pinfunction "GND_MNT3") (pintype "bidirectional"))
      (node (ref "J3") (pin "MNT4") (pinfunction "GND_MNT4") (pintype "bidirectional"))
      (node (ref "J4") (pin "5") (pinfunction "GND_5") (pintype "bidirectional"))
      (node (ref "J5") (pin "5") (pinfunction "GND_5") (pintype "bidirectional"))
      (node (ref "J6") (pin "5") (pinfunction "GND_5") (pintype "bidirectional"))
      (node (ref "J7") (pin "5") (pinfunction "GND_5") (pintype "bidirectional"))
      (node (ref "J8") (pin "5") (pinfunction "GND_5") (pintype "bidirectional"))
      (node (ref "J9") (pin "5") (pinfunction "GND_5") (pintype "bidirectional"))
      (node (ref "LED5") (pin "C") (pinfunction "CATHODE_C") (pintype "bidirectional"))
      (node (ref "LED6") (pin "C") (pinfunction "CATHODE_C") (pintype "bidirectional"))
      (node (ref "LED7") (pin "C") (pinfunction "CATHODE_C") (pintype "bidirectional"))
      (node (ref "LED8") (pin "C") (pinfunction "CATHODE_C") (pintype "bidirectional"))
      (node (ref "LED9") (pin "C") (pinfunction "CATHODE_C") (pintype "bidirectional"))
      (node (ref "Q1") (pin "S") (pinfunction "S_S") (pintype "bidirectional"))
      (node (ref "Q2") (pin "2") (pinfunction "S_2") (pintype "passive"))
      (node (ref "Q3") (pin "2") (pinfunction "S_2") (pintype "passive"))
      (node (ref "Q4") (pin "2") (pinfunction "S_2") (pintype "passive"))
      (node (ref "Q5") (pin "2") (pinfunction "S_2") (pintype "passive"))
      (node (ref "Q6") (pin "2") (pinfunction "S_2") (pintype "passive"))
      (node (ref "Q7") (pin "2") (pinfunction "S_2") (pintype "passive"))
      (node (ref "Q8") (pin "2") (pinfunction "S_2") (pintype "passive"))
      (node (ref "Q9") (pin "2") (pinfunction "S_2") (pintype "passive"))
      (node (ref "R1") (pin "1") (pinfunction "1_1") (pintype "passive"))
      (node (ref "R12") (pin "2") (pinfunction "2_2") (pintype "passive"))
      (node (ref "R13") (pin "2") (pinfunction "2_2") (pintype "passive"))
      (node (ref "R14") (pin "2") (pinfunction "2_2") (pintype "passive"))
      (node (ref "R15") (pin "2") (pinfunction "2_2") (pintype "passive"))
      (node (ref "R16") (pin "1") (pinfunction "1_1") (pintype "passive"))
      (node (ref "R17") (pin "1") (pinfunction "1_1") (pintype "passive"))
      (node (ref "R18") (pin "1") (pinfunction "1_1") (pintype "passive"))
      (node (ref "R19") (pin "1") (pinfunction "1_1") (pintype "passive"))
      (node (ref "R20") (pin "1") (pinfunction "1_1") (pintype "passive"))
      (node (ref "R21") (pin "1") (pinfunction "1_1") (pintype "passive"))
      (node (ref "R26") (pin "1") (pinfunction "1_1") (pintype "passive"))
      (node (ref "R27") (pin "1") (pinfunction "1_1") (pintype "passive"))
      (node (ref "R28") (pin "1") (pinfunction "1_1") (pintype "passive"))
      (node (ref "R29") (pin "1") (pinfunction "1_1") (pintype "passive"))
      (node (ref "R30") (pin "1") (pinfunction "1_1") (pintype "passive"))
      (node (ref "R73") (pin "1") (pinfunction "1_1") (pintype "passive"))
      (node (ref "R74") (pin "1") (pinfunction "1_1") (pintype "passive"))
      (node (ref "R75") (pin "1") (pinfunction "1_1") (pintype "passive"))
      (node (ref "R76") (pin "1") (pinfunction "1_1") (pintype "passive"))
      (node (ref "R77") (pin "1") (pinfunction "1_1") (pintype "passive"))
      (node (ref "R78") (pin "1") (pinfunction "1_1") (pintype "passive"))
      (node (ref "R79") (pin "2") (pinfunction "2_2") (pintype "passive"))
      (node (ref "R80") (pin "2") (pinfunction "2_2") (pintype "passive"))
      (node (ref "R81") (pin "2") (pinfunction "2_2") (pintype "passive"))
      (node (ref "R82") (pin "2") (pinfunction "2_2") (pintype "passive"))
      (node (ref "R83") (pin "2") (pinfunction "2_2") (pintype "passive"))
      (node (ref "R84") (pin "2") (pinfunction "2_2") (pintype "passive"))
      (node (ref "R85") (pin "2") (pinfunction "2_2") (pintype "passive"))
      (node (ref "R86") (pin "2") (pinfunction "2_2") (pintype "passive"))
      (node (ref "R90") (pin "1") (pinfunction "1_1") (pintype "passive"))
      (node (ref "R91") (pin "1") (pinfunction "1_1") (pintype "passive"))
      (node (ref "R92") (pin "1") (pinfunction "1_1") (pintype "passive"))
      (node (ref "R93") (pin "1") (pinfunction "1_1") (pintype "passive"))
      (node (ref "R94") (pin "1") (pinfunction "1_1") (pintype "passive"))
      (node (ref "R95") (pin "1") (pinfunction "1_1") (pintype "passive"))
      (node (ref "R96") (pin "1") (pinfunction "1_1") (pintype "passive"))
      (node (ref "S1") (pin "1") (pinfunction "GND_1") (pintype "bidirectional"))
      (node (ref "S1") (pin "PAD") (pinfunction "GND_PAD") (pintype "bidirectional"))
      (node (ref "S10") (pin "2") (pinfunction "GND_2") (pintype "bidirectional"))
      (node (ref "S12") (pin "2") (pinfunction "GND_2") (pintype "bidirectional"))
      (node (ref "S12") (pin "PAD") (pinfunction "GND_PAD") (pintype "bidirectional"))
      (node (ref "S13") (pin "2") (pinfunction "GND_2") (pintype "bidirectional"))
      (node (ref "S13") (pin "PAD") (pinfunction "GND_PAD") (pintype "bidirectional"))
      (node (ref "S14") (pin "7") (pinfunction "GND_7") (pintype "bidirectional"))
      (node (ref "S15") (pin "7") (pinfunction "GND_7") (pintype "bidirectional"))
      (node (ref "S16") (pin "7") (pinfunction "GND_7") (pintype "bidirectional"))
      (node (ref "S17") (pin "7") (pinfunction "GND_7") (pintype "bidirectional"))
      (node (ref "S18") (pin "7") (pinfunction "GND_7") (pintype "bidirectional"))
      (node (ref "S2") (pin "1") (pinfunction "GND_1") (pintype "bidirectional"))
      (node (ref "S2") (pin "PAD") (pinfunction "GND_PAD") (pintype "bidirectional"))
      (node (ref "S3") (pin "1") (pinfunction "P$1_1") (pintype "passive"))
      (node (ref "S4") (pin "1") (pinfunction "P$1_1") (pintype "passive"))
      (node (ref "S5") (pin "1") (pinfunction "P$1_1") (pintype "passive"))
      (node (ref "S6") (pin "1") (pinfunction "P$1_1") (pintype "passive"))
      (node (ref "S7") (pin "1") (pinfunction "P$1_1") (pintype "passive"))
      (node (ref "S8") (pin "1") (pinfunction "P$1_1") (pintype "passive"))
      (node (ref "S9") (pin "2") (pinfunction "GND_2") (pintype "bidirectional"))
      (node (ref "TP11") (pin "TESTPOINT") (pinfunction "TESTPOINT_TESTPOINT") (pintype "bidirectional"))
      (node (ref "TP25") (pin "TESTPOINT") (pinfunction "TESTPOINT_TESTPOINT") (pintype "bidirectional"))
      (node (ref "TP27") (pin "TESTPOINT") (pinfunction "TESTPOINT_TESTPOINT") (pintype "bidirectional"))
      (node (ref "TP51") (pin "TESTPOINT") (pinfunction "TESTPOINT_TESTPOINT") (pintype "bidirectional"))
      (node (ref "TP54") (pin "TESTPOINT") (pinfunction "TESTPOINT_TESTPOINT") (pintype "bidirectional"))
      (node (ref "TP56") (pin "TESTPOINT") (pinfunction "TESTPOINT_TESTPOINT") (pintype "bidirectional"))
      (node (ref "U1") (pin "17") (pinfunction "GND_17") (pintype "power_in"))
      (node (ref "U1") (pin "20") (pinfunction "GND_20") (pintype "power_in"))
      (node (ref "U1") (pin "24") (pinfunction "GND_24") (pintype "power_in"))
      (node (ref "U1") (pin "26") (pinfunction "TEST_26") (pintype "input"))
      (node (ref "U1") (pin "4") (pinfunction "GND_4") (pintype "power_in"))
      (node (ref "U10") (pin "2") (pinfunction "GND_2") (pintype "open_collector"))
      (node (ref "U11") (pin "2") (pinfunction "GND_2") (pintype "open_collector"))
      (node (ref "U12") (pin "2") (pinfunction "GND_2") (pintype "bidirectional"))
      (node (ref "U13") (pin "1") (pinfunction "A2_1") (pintype "bidirectional"))
      (node (ref "U13") (pin "17") (pinfunction "GND_17") (pintype "bidirectional"))
      (node (ref "U13") (pin "2") (pinfunction "A1_2") (pintype "bidirectional"))
      (node (ref "U13") (pin "3") (pinfunction "A0_3") (pintype "bidirectional"))
      (node (ref "U13") (pin "GND") (pinfunction "GND_GND") (pintype "bidirectional"))
      (node (ref "U14") (pin "1") (pinfunction "A2_1") (pintype "bidirectional"))
      (node (ref "U14") (pin "17") (pinfunction "GND_17") (pintype "bidirectional"))
      (node (ref "U14") (pin "2") (pinfunction "A1_2") (pintype "bidirectional"))
      (node (ref "U14") (pin "GND") (pinfunction "GND_GND") (pintype "bidirectional"))
      (node (ref "U15") (pin "1") (pinfunction "A0_1") (pintype "bidirectional"))
      (node (ref "U15") (pin "10") (pinfunction "GND_10") (pintype "bidirectional"))
      (node (ref "U15") (pin "2") (pinfunction "A1_2") (pintype "bidirectional"))
      (node (ref "U15") (pin "3") (pinfunction "A2_3") (pintype "bidirectional"))
      (node (ref "U16") (pin "17") (pinfunction "GNDANA_17") (pintype "power_in"))
      (node (ref "U16") (pin "30") (pinfunction "GND_30") (pintype "power_in"))
      (node (ref "U16") (pin "48") (pinfunction "GND_48") (pintype "power_in"))
      (node (ref "U16") (pin "6") (pinfunction "GND_6") (pintype "power_in"))
      (node (ref "U16") (pin "THERMAL") (pinfunction "GND_THERMAL") (pintype "power_in"))
      (node (ref "U17") (pin "4") (pinfunction "GND_4") (pintype "bidirectional"))
      (node (ref "U18") (pin "4") (pinfunction "GND_4") (pintype "bidirectional"))
      (node (ref "U19") (pin "4") (pinfunction "GND_4") (pintype "bidirectional"))
      (node (ref "U19") (pin "5") (pinfunction "DIR_5") (pintype "bidirectional"))
      (node (ref "U2") (pin "17") (pinfunction "GND_17") (pintype "power_in"))
      (node (ref "U2") (pin "20") (pinfunction "GND_20") (pintype "power_in"))
      (node (ref "U2") (pin "24") (pinfunction "GND_24") (pintype "power_in"))
      (node (ref "U2") (pin "26") (pinfunction "TEST_26") (pintype "input"))
      (node (ref "U2") (pin "4") (pinfunction "GND_4") (pintype "power_in"))
      (node (ref "U20") (pin "4") (pinfunction "GND_4") (pintype "bidirectional"))
      (node (ref "U20") (pin "5") (pinfunction "DIR_5") (pintype "bidirectional"))
      (node (ref "U21") (pin "10") (pinfunction "S_10") (pintype "bidirectional"))
      (node (ref "U21") (pin "4") (pinfunction "GND_4") (pintype "bidirectional"))
      (node (ref "U22") (pin "10") (pinfunction "S_10") (pintype "bidirectional"))
      (node (ref "U22") (pin "4") (pinfunction "GND_4") (pintype "bidirectional"))
      (node (ref "U23") (pin "4") (pinfunction "GND_4") (pintype "bidirectional"))
      (node (ref "U23") (pin "8") (pinfunction "~{OE}_8") (pintype "bidirectional"))
      (node (ref "U24") (pin "10") (pinfunction "~{BUSPWR}_10") (pintype "bidirectional"))
      (node (ref "U24") (pin "24") (pinfunction "GND_24") (pintype "bidirectional"))
      (node (ref "U24") (pin "43") (pinfunction "GND_43") (pintype "bidirectional"))
      (node (ref "U24") (pin "48") (pinfunction "MODE_48") (pintype "bidirectional"))
      (node (ref "U24") (pin "5") (pinfunction "GND_5") (pintype "bidirectional"))
      (node (ref "U3") (pin "17") (pinfunction "GND_17") (pintype "power_in"))
      (node (ref "U3") (pin "20") (pinfunction "GND_20") (pintype "power_in"))
      (node (ref "U3") (pin "24") (pinfunction "GND_24") (pintype "power_in"))
      (node (ref "U3") (pin "26") (pinfunction "TEST_26") (pintype "input"))
      (node (ref "U3") (pin "4") (pinfunction "GND_4") (pintype "power_in"))
      (node (ref "U4") (pin "17") (pinfunction "GND_17") (pintype "power_in"))
      (node (ref "U4") (pin "20") (pinfunction "GND_20") (pintype "power_in"))
      (node (ref "U4") (pin "24") (pinfunction "GND_24") (pintype "power_in"))
      (node (ref "U4") (pin "26") (pinfunction "TEST_26") (pintype "input"))
      (node (ref "U4") (pin "4") (pinfunction "GND_4") (pintype "power_in"))
      (node (ref "U5") (pin "17") (pinfunction "GND_17") (pintype "power_in"))
      (node (ref "U5") (pin "20") (pinfunction "GND_20") (pintype "power_in"))
      (node (ref "U5") (pin "24") (pinfunction "GND_24") (pintype "power_in"))
      (node (ref "U5") (pin "26") (pinfunction "TEST_26") (pintype "input"))
      (node (ref "U5") (pin "4") (pinfunction "GND_4") (pintype "power_in"))
      (node (ref "U6") (pin "4") (pinfunction "GND_4") (pintype "bidirectional"))
      (node (ref "U7") (pin "4") (pinfunction "GND_4") (pintype "bidirectional"))
      (node (ref "U8") (pin "2") (pinfunction "GND_2") (pintype "open_collector"))
      (node (ref "U9") (pin "2") (pinfunction "GND_2") (pintype "open_collector"))
      (node (ref "X1") (pin "2") (pinfunction "GND_2") (pintype "bidirectional"))
      (node (ref "X1") (pin "4") (pinfunction "GND_4") (pintype "bidirectional"))
    )
    (net (code "28") (name "HUB_CFG") (class "Default")
      (node (ref "TP28") (pin "TESTPOINT") (pinfunction "TESTPOINT_TESTPOINT") (pintype "bidirectional"))
      (node (ref "U24") (pin "40") (pinfunction "HUBCFG_40") (pintype "bidirectional"))
    )
    (net (code "29") (name "HUB_DM1") (class "Default")
      (node (ref "C8") (pin "1") (pinfunction "1_1") (pintype "bidirectional"))
      (node (ref "R9") (pin "2") (pinfunction "P$2_2") (pintype "passive"))
      (node (ref "U24") (pin "13") (pinfunction "DM1_13") (pintype "bidirectional"))
    )
    (net (code "30") (name "HUB_DM2") (class "Default")
      (node (ref "C6") (pin "1") (pinfunction "1_1") (pintype "bidirectional"))
      (node (ref "R7") (pin "2") (pinfunction "P$2_2") (pintype "passive"))
      (node (ref "U24") (pin "17") (pinfunction "DM2_17") (pintype "bidirectional"))
    )
    (net (code "31") (name "HUB_DM3") (class "Default")
      (node (ref "C10") (pin "1") (pinfunction "1_1") (pintype "bidirectional"))
      (node (ref "R11") (pin "2") (pinfunction "P$2_2") (pintype "passive"))
      (node (ref "U24") (pin "21") (pinfunction "DM3_21") (pintype "bidirectional"))
    )
    (net (code "32") (name "HUB_DM4") (class "Default")
      (node (ref "R82") (pin "1") (pinfunction "1_1") (pintype "passive"))
      (node (ref "U24") (pin "26") (pinfunction "DM4_26") (pintype "bidirectional"))
    )
    (net (code "33") (name "HUB_DM5") (class "Default")
      (node (ref "R80") (pin "1") (pinfunction "1_1") (pintype "passive"))
      (node (ref "U24") (pin "30") (pinfunction "DM5_30") (pintype "bidirectional"))
    )
    (net (code "34") (name "HUB_DM6") (class "Default")
      (node (ref "R84") (pin "1") (pinfunction "1_1") (pintype "passive"))
      (node (ref "U24") (pin "34") (pinfunction "DM6_34") (pintype "bidirectional"))
    )
    (net (code "35") (name "HUB_DM7") (class "Default")
      (node (ref "R86") (pin "1") (pinfunction "1_1") (pintype "passive"))
      (node (ref "U24") (pin "38") (pinfunction "DM7_38") (pintype "bidirectional"))
    )
    (net (code "36") (name "HUB_DP1") (class "Default")
      (node (ref "C7") (pin "1") (pinfunction "1_1") (pintype "bidirectional"))
      (node (ref "R8") (pin "2") (pinfunction "P$2_2") (pintype "passive"))
      (node (ref "U24") (pin "14") (pinfunction "DP1_14") (pintype "bidirectional"))
    )
    (net (code "37") (name "HUB_DP2") (class "Default")
      (node (ref "C5") (pin "1") (pinfunction "1_1") (pintype "bidirectional"))
      (node (ref "R6") (pin "2") (pinfunction "P$2_2") (pintype "passive"))
      (node (ref "U24") (pin "18") (pinfunction "DP2_18") (pintype "bidirectional"))
    )
    (net (code "38") (name "HUB_DP3") (class "Default")
      (node (ref "C9") (pin "1") (pinfunction "1_1") (pintype "bidirectional"))
      (node (ref "R10") (pin "2") (pinfunction "P$2_2") (pintype "passive"))
      (node (ref "U24") (pin "22") (pinfunction "DP3_22") (pintype "bidirectional"))
    )
    (net (code "39") (name "HUB_DP4") (class "Default")
      (node (ref "R81") (pin "1") (pinfunction "1_1") (pintype "passive"))
      (node (ref "U24") (pin "27") (pinfunction "DP4_27") (pintype "bidirectional"))
    )
    (net (code "40") (name "HUB_DP5") (class "Default")
      (node (ref "R79") (pin "1") (pinfunction "1_1") (pintype "passive"))
      (node (ref "U24") (pin "31") (pinfunction "DP5_31") (pintype "bidirectional"))
    )
    (net (code "41") (name "HUB_DP6") (class "Default")
      (node (ref "R83") (pin "1") (pinfunction "1_1") (pintype "passive"))
      (node (ref "U24") (pin "35") (pinfunction "DP6_35") (pintype "bidirectional"))
    )
    (net (code "42") (name "HUB_DP7") (class "Default")
      (node (ref "R85") (pin "1") (pinfunction "1_1") (pintype "passive"))
      (node (ref "U24") (pin "39") (pinfunction "DP7_39") (pintype "bidirectional"))
    )
    (net (code "43") (name "HUB_PORTDIS") (class "Default")
      (node (ref "TP30") (pin "TESTPOINT") (pinfunction "TESTPOINT_TESTPOINT") (pintype "bidirectional"))
      (node (ref "U24") (pin "42") (pinfunction "PORTDIS_42") (pintype "bidirectional"))
    )
    (net (code "44") (name "HUB_PORTPWR") (class "Default")
      (node (ref "TP29") (pin "TESTPOINT") (pinfunction "TESTPOINT_TESTPOINT") (pintype "bidirectional"))
      (node (ref "U24") (pin "41") (pinfunction "PORTPWR_41") (pintype "bidirectional"))
    )
    (net (code "45") (name "HUB_~{OVRCUR1}") (class "Default")
      (node (ref "R56") (pin "1") (pinfunction "1_1") (pintype "passive"))
      (node (ref "S2") (pin "5") (pinfunction "~{FLG}_5") (pintype "bidirectional"))
      (node (ref "TP33") (pin "TESTPOINT") (pinfunction "TESTPOINT_TESTPOINT") (pintype "bidirectional"))
      (node (ref "U24") (pin "12") (pinfunction "~{OVRCUR1}_12") (pintype "bidirectional"))
    )
    (net (code "46") (name "HUB_~{OVRCUR2}") (class "Default")
      (node (ref "R55") (pin "1") (pinfunction "1_1") (pintype "passive"))
      (node (ref "S1") (pin "5") (pinfunction "~{FLG}_5") (pintype "bidirectional"))
      (node (ref "TP35") (pin "TESTPOINT") (pinfunction "TESTPOINT_TESTPOINT") (pintype "bidirectional"))
      (node (ref "U24") (pin "16") (pinfunction "~{OVRCUR2}_16") (pintype "bidirectional"))
    )
    (net (code "47") (name "HUB_~{OVRCUR3}") (class "Default")
      (node (ref "R72") (pin "1") (pinfunction "1_1") (pintype "passive"))
      (node (ref "TP37") (pin "TESTPOINT") (pinfunction "TESTPOINT_TESTPOINT") (pintype "bidirectional"))
      (node (ref "U24") (pin "20") (pinfunction "~{OVRCUR3}_20") (pintype "bidirectional"))
    )
    (net (code "48") (name "HUB_~{OVRCUR4}") (class "Default")
      (node (ref "R67") (pin "1") (pinfunction "1_1") (pintype "passive"))
      (node (ref "U24") (pin "25") (pinfunction "~{OVRCUR4}_25") (pintype "bidirectional"))
    )
    (net (code "49") (name "HUB_~{OVRCUR5}") (class "Default")
      (node (ref "R66") (pin "1") (pinfunction "1_1") (pintype "passive"))
      (node (ref "U24") (pin "29") (pinfunction "~{OVRCUR5}_29") (pintype "bidirectional"))
    )
    (net (code "50") (name "HUB_~{OVRCUR6}") (class "Default")
      (node (ref "R68") (pin "1") (pinfunction "1_1") (pintype "passive"))
      (node (ref "U24") (pin "33") (pinfunction "~{OVRCUR6}_33") (pintype "bidirectional"))
    )
    (net (code "51") (name "HUB_~{OVRCUR7}") (class "Default")
      (node (ref "R69") (pin "1") (pinfunction "1_1") (pintype "passive"))
      (node (ref "U24") (pin "37") (pinfunction "~{OVRCUR7}_37") (pintype "bidirectional"))
    )
    (net (code "52") (name "HUB_~{PWRON1}") (class "Default")
      (node (ref "S10") (pin "1") (pinfunction "I1_1") (pintype "bidirectional"))
      (node (ref "TP32") (pin "TESTPOINT") (pinfunction "TESTPOINT_TESTPOINT") (pintype "bidirectional"))
      (node (ref "U24") (pin "11") (pinfunction "~{PWRON1}_11") (pintype "bidirectional"))
    )
    (net (code "53") (name "HUB_~{PWRON2}") (class "Default")
      (node (ref "S9") (pin "1") (pinfunction "I1_1") (pintype "bidirectional"))
      (node (ref "TP34") (pin "TESTPOINT") (pinfunction "TESTPOINT_TESTPOINT") (pintype "bidirectional"))
      (node (ref "U24") (pin "15") (pinfunction "~{PWRON2}_15") (pintype "bidirectional"))
    )
    (net (code "54") (name "HUB_~{PWRON3}") (class "Default")
      (node (ref "TP36") (pin "TESTPOINT") (pinfunction "TESTPOINT_TESTPOINT") (pintype "bidirectional"))
      (node (ref "U24") (pin "19") (pinfunction "~{PWRON3}_19") (pintype "bidirectional"))
    )
    (net (code "55") (name "HUB_~{PWRON4}") (class "Default")
      (node (ref "U24") (pin "23") (pinfunction "~{PWRON4}_23") (pintype "bidirectional"))
    )
    (net (code "56") (name "HUB_~{PWRON5}") (class "Default")
      (node (ref "U24") (pin "28") (pinfunction "~{PWRON5}_28") (pintype "bidirectional"))
    )
    (net (code "57") (name "HUB_~{PWRON6}") (class "Default")
      (node (ref "U24") (pin "32") (pinfunction "~{PWRON6}_32") (pintype "bidirectional"))
    )
    (net (code "58") (name "HUB_~{PWRON7}") (class "Default")
      (node (ref "U24") (pin "36") (pinfunction "~{PWRON7}_36") (pintype "bidirectional"))
    )
    (net (code "59") (name "JTAG_5V") (class "Default")
      (node (ref "J10") (pin "19") (pinfunction "19_19") (pintype "passive"))
    )
    (net (code "60") (name "JTAG_DBGRQ") (class "Default")
      (node (ref "J10") (pin "17") (pinfunction "17_17") (pintype "passive"))
    )
    (net (code "61") (name "JTAG_NTRST") (class "Default")
      (node (ref "J10") (pin "3") (pinfunction "3_3") (pintype "passive"))
    )
    (net (code "62") (name "JTAG_RTCK") (class "Default")
      (node (ref "J10") (pin "11") (pinfunction "11_11") (pintype "passive"))
    )
    (net (code "63") (name "JTAG_SWDCLK") (class "Default")
      (node (ref "J10") (pin "9") (pinfunction "9_9") (pintype "passive"))
      (node (ref "S14") (pin "4") (pinfunction "IN_4") (pintype "bidirectional"))
      (node (ref "S15") (pin "4") (pinfunction "IN_4") (pintype "bidirectional"))
      (node (ref "S16") (pin "4") (pinfunction "IN_4") (pintype "bidirectional"))
      (node (ref "S17") (pin "4") (pinfunction "IN_4") (pintype "bidirectional"))
      (node (ref "S18") (pin "4") (pinfunction "IN_4") (pintype "bidirectional"))
    )
    (net (code "64") (name "JTAG_SWDIO") (class "Default")
      (node (ref "J10") (pin "7") (pinfunction "7_7") (pintype "passive"))
      (node (ref "S14") (pin "1") (pinfunction "IN_1") (pintype "bidirectional"))
      (node (ref "S15") (pin "1") (pinfunction "IN_1") (pintype "bidirectional"))
      (node (ref "S16") (pin "1") (pinfunction "IN_1") (pintype "bidirectional"))
      (node (ref "S17") (pin "1") (pinfunction "IN_1") (pintype "bidirectional"))
      (node (ref "S18") (pin "1") (pinfunction "IN_1") (pintype "bidirectional"))
      (node (ref "S19") (pin "IN") (pinfunction "IN_IN") (pintype "bidirectional"))
    )
    (net (code "65") (name "JTAG_SWO{slash}TDO") (class "Default")
      (node (ref "J10") (pin "13") (pinfunction "13_13") (pintype "passive"))
    )
    (net (code "66") (name "JTAG_TDI") (class "Default")
      (node (ref "J10") (pin "5") (pinfunction "5_5") (pintype "passive"))
    )
    (net (code "67") (name "JTAG_VTREF") (class "Default")
      (node (ref "J10") (pin "1") (pinfunction "1_1") (pintype "passive"))
      (node (ref "S14") (pin "11") (pinfunction "IN_11") (pintype "bidirectional"))
      (node (ref "S15") (pin "11") (pinfunction "IN_11") (pintype "bidirectional"))
      (node (ref "S16") (pin "11") (pinfunction "IN_11") (pintype "bidirectional"))
      (node (ref "S17") (pin "11") (pinfunction "IN_11") (pintype "bidirectional"))
      (node (ref "S18") (pin "11") (pinfunction "IN_11") (pintype "bidirectional"))
    )
    (net (code "68") (name "JTAG_~{RESET}") (class "Default")
      (node (ref "J10") (pin "15") (pinfunction "15_15") (pintype "passive"))
      (node (ref "S14") (pin "8") (pinfunction "IN_8") (pintype "bidirectional"))
      (node (ref "S15") (pin "8") (pinfunction "IN_8") (pintype "bidirectional"))
      (node (ref "S16") (pin "8") (pinfunction "IN_8") (pintype "bidirectional"))
      (node (ref "S17") (pin "8") (pinfunction "IN_8") (pintype "bidirectional"))
      (node (ref "S18") (pin "8") (pinfunction "IN_8") (pintype "bidirectional"))
      (node (ref "S19") (pin "1") (pinfunction "A_1") (pintype "bidirectional"))
    )
    (net (code "69") (name "MOD0_5V") (class "Default")
      (node (ref "C18") (pin "1") (pinfunction "1_1") (pintype "bidirectional"))
      (node (ref "J3") (pin "2") (pinfunction "5V_2") (pintype "bidirectional"))
      (node (ref "S12") (pin "1") (pinfunction "VLOAD_1") (pintype "bidirectional"))
      (node (ref "TP57") (pin "TESTPOINT") (pinfunction "TESTPOINT_TESTPOINT") (pintype "bidirectional"))
    )
    (net (code "70") (name "MOD0_5V_METERED") (class "Default")
      (node (ref "C14") (pin "1") (pinfunction "1_1") (pintype "bidirectional"))
      (node (ref "C35") (pin "1") (pinfunction "1_1") (pintype "bidirectional"))
      (node (ref "C64") (pin "1") (pinfunction "1_1") (pintype "bidirectional"))
      (node (ref "R4") (pin "1") (pinfunction "1_1") (pintype "passive"))
      (node (ref "S1") (pin "2") (pinfunction "IN_2") (pintype "bidirectional"))
      (node (ref "S1") (pin "3") (pinfunction "IN_3") (pintype "bidirectional"))
      (node (ref "S12") (pin "3") (pinfunction "VSUPP_3") (pintype "bidirectional"))
      (node (ref "TP16") (pin "TESTPOINT") (pinfunction "TESTPOINT_TESTPOINT") (pintype "bidirectional"))
      (node (ref "U10") (pin "6") (pinfunction "SENSE-_6") (pintype "open_collector"))
    )
    (net (code "71") (name "MOD0_D+_HUB-SW") (class "Default")
      (node (ref "D8") (pin "4") (pinfunction "D_4") (pintype "bidirectional"))
      (node (ref "R6") (pin "1") (pinfunction "P$1_1") (pintype "passive"))
      (node (ref "R73") (pin "2") (pinfunction "2_2") (pintype "passive"))
      (node (ref "U21") (pin "3") (pinfunction "D+_3") (pintype "bidirectional"))
    )
    (net (code "72") (name "MOD0_D-_HUB-SW") (class "Default")
      (node (ref "D8") (pin "2") (pinfunction "C_2") (pintype "bidirectional"))
      (node (ref "R7") (pin "1") (pinfunction "P$1_1") (pintype "passive"))
      (node (ref "R74") (pin "2") (pinfunction "2_2") (pintype "passive"))
      (node (ref "U21") (pin "5") (pinfunction "D-_5") (pintype "bidirectional"))
    )
    (net (code "73") (name "MOD0_DBG_GPIO1") (class "Default")
      (node (ref "J3") (pin "16") (pinfunction "DBG_GPIO1_16") (pintype "bidirectional"))
      (node (ref "Q2") (pin "1") (pinfunction "G_1") (pintype "passive"))
      (node (ref "TP21") (pin "TESTPOINT") (pinfunction "TESTPOINT_TESTPOINT") (pintype "bidirectional"))
    )
    (net (code "74") (name "MOD0_DBG_GPIO2") (class "Default")
      (node (ref "J3") (pin "19") (pinfunction "DBG_GPIO2_19") (pintype "bidirectional"))
      (node (ref "Q3") (pin "1") (pinfunction "G_1") (pintype "passive"))
      (node (ref "TP38") (pin "TESTPOINT") (pinfunction "TESTPOINT_TESTPOINT") (pintype "bidirectional"))
    )
    (net (code "75") (name "MOD0_DBG_RX") (class "Default")
      (node (ref "J3") (pin "18") (pinfunction "DBG_RX_18") (pintype "bidirectional"))
      (node (ref "U2") (pin "30") (pinfunction "TXD_30") (pintype "output"))
    )
    (net (code "76") (name "MOD0_DBG_SWDCLK") (class "Default")
      (node (ref "J3") (pin "21") (pinfunction "DBG_SWDCLK_21") (pintype "bidirectional"))
      (node (ref "S14") (pin "3") (pinfunction "A_3") (pintype "bidirectional"))
    )
    (net (code "77") (name "MOD0_DBG_SWDIO") (class "Default")
      (node (ref "J3") (pin "22") (pinfunction "DBG_SWDIO_22") (pintype "bidirectional"))
      (node (ref "S14") (pin "2") (pinfunction "A_2") (pintype "bidirectional"))
    )
    (net (code "78") (name "MOD0_DBG_TX") (class "Default")
      (node (ref "J3") (pin "17") (pinfunction "DBG_TX_17") (pintype "bidirectional"))
      (node (ref "U2") (pin "2") (pinfunction "RXD_2") (pintype "input"))
    )
    (net (code "79") (name "MOD0_DBG_~{RESET}") (class "Default")
      (node (ref "J3") (pin "20") (pinfunction "DBG_~{RESET}_20") (pintype "bidirectional"))
      (node (ref "S14") (pin "9") (pinfunction "A_9") (pintype "bidirectional"))
      (node (ref "S4") (pin "2") (pinfunction "P$2_2") (pintype "passive"))
    )
    (net (code "80") (name "MOD0_IN") (class "Default")
      (node (ref "J3") (pin "10") (pinfunction "MOD_IN_10") (pintype "bidirectional"))
      (node (ref "TP48") (pin "TESTPOINT") (pinfunction "TESTPOINT_TESTPOINT") (pintype "bidirectional"))
      (node (ref "U17") (pin "7") (pinfunction "B1_7") (pintype "bidirectional"))
    )
    (net (code "81") (name "MOD0_ISO_I2C") (class "Default")
      (node (ref "D2") (pin "A") (pinfunction "ANODE_A") (pintype "bidirectional"))
      (node (ref "R92") (pin "2") (pinfunction "2_2") (pintype "passive"))
      (node (ref "TP1002") (pin "TESTPOINT") (pinfunction "TESTPOINT_TESTPOINT") (pintype "bidirectional"))
      (node (ref "U13") (pin "10") (pinfunction "P1_10") (pintype "bidirectional"))
      (node (ref "U6") (pin "5") (pinfunction "OE_5") (pintype "bidirectional"))
    )
    (net (code "82") (name "MOD0_ISO_POWER") (class "Default")
      (node (ref "D1") (pin "A") (pinfunction "ANODE_A") (pintype "bidirectional"))
      (node (ref "R91") (pin "2") (pinfunction "2_2") (pintype "passive"))
      (node (ref "S12") (pin "4") (pinfunction "EN_4") (pintype "bidirectional"))
      (node (ref "TP1001") (pin "TESTPOINT") (pinfunction "TESTPOINT_TESTPOINT") (pintype "bidirectional"))
      (node (ref "U13") (pin "9") (pinfunction "P0_9") (pintype "bidirectional"))
    )
    (net (code "83") (name "MOD0_ISO_USB") (class "Default")
      (node (ref "D3") (pin "A") (pinfunction "ANODE_A") (pintype "bidirectional"))
      (node (ref "R93") (pin "2") (pinfunction "2_2") (pintype "passive"))
      (node (ref "S9") (pin "6") (pinfunction "S_6") (pintype "bidirectional"))
      (node (ref "TP1003") (pin "TESTPOINT") (pinfunction "TESTPOINT_TESTPOINT") (pintype "bidirectional"))
      (node (ref "U13") (pin "11") (pinfunction "P2_11") (pintype "bidirectional"))
    )
    (net (code "84") (name "MOD0_OUT") (class "Default")
      (node (ref "J3") (pin "8") (pinfunction "MOD_OUT_8") (pintype "bidirectional"))
      (node (ref "TP49") (pin "TESTPOINT") (pinfunction "TESTPOINT_TESTPOINT") (pintype "bidirectional"))
      (node (ref "U19") (pin "7") (pinfunction "B1_7") (pintype "bidirectional"))
    )
    (net (code "85") (name "MOD0_PPS") (class "Default")
      (node (ref "J3") (pin "7") (pinfunction "PPS_7") (pintype "bidirectional"))
      (node (ref "TP46") (pin "TESTPOINT") (pinfunction "TESTPOINT_TESTPOINT") (pintype "bidirectional"))
      (node (ref "U17") (pin "6") (pinfunction "B2_6") (pintype "bidirectional"))
    )
    (net (code "86") (name "MOD0_SCL") (class "Default")
      (node (ref "J3") (pin "5") (pinfunction "SCL_5") (pintype "bidirectional"))
      (node (ref "R58") (pin "2") (pinfunction "2_2") (pintype "passive"))
      (node (ref "TP43") (pin "TESTPOINT") (pinfunction "TESTPOINT_TESTPOINT") (pintype "bidirectional"))
      (node (ref "U6") (pin "6") (pinfunction "B1_6") (pintype "bidirectional"))
    )
    (net (code "87") (name "MOD0_SDA") (class "Default")
      (node (ref "J3") (pin "6") (pinfunction "SDA_6") (pintype "bidirectional"))
      (node (ref "R57") (pin "2") (pinfunction "2_2") (pintype "passive"))
      (node (ref "TP42") (pin "TESTPOINT") (pinfunction "TESTPOINT_TESTPOINT") (pintype "bidirectional"))
      (node (ref "U6") (pin "7") (pinfunction "B0_7") (pintype "bidirectional"))
    )
    (net (code "88") (name "MOD0_USB+") (class "Default")
      (node (ref "J3") (pin "11") (pinfunction "USB_D+_11") (pintype "bidirectional"))
      (node (ref "U21") (pin "1") (pinfunction "D1+_1") (pintype "bidirectional"))
    )
    (net (code "89") (name "MOD0_USB-") (class "Default")
      (node (ref "J3") (pin "12") (pinfunction "USB_D-_12") (pintype "bidirectional"))
      (node (ref "U21") (pin "7") (pinfunction "D1-_7") (pintype "bidirectional"))
    )
    (net (code "90") (name "MOD0_USB_VBUS") (class "Default")
      (node (ref "C31") (pin "1") (pinfunction "1_1") (pintype "bidirectional"))
      (node (ref "C68") (pin "1") (pinfunction "1_1") (pintype "bidirectional"))
      (node (ref "J3") (pin "13") (pinfunction "USB_VBUS_13") (pintype "bidirectional"))
      (node (ref "S1") (pin "6") (pinfunction "OUT_6") (pintype "bidirectional"))
      (node (ref "S1") (pin "7") (pinfunction "OUT_7") (pintype "bidirectional"))
      (node (ref "TP20") (pin "TESTPOINT") (pinfunction "TESTPOINT_TESTPOINT") (pintype "bidirectional"))
    )
    (net (code "91") (name "MOD0_USB_~{EN}") (class "Default")
      (node (ref "S1") (pin "4") (pinfunction "~{EN}_4") (pintype "bidirectional"))
      (node (ref "S9") (pin "4") (pinfunction "Z_4") (pintype "bidirectional"))
      (node (ref "U21") (pin "8") (pinfunction "~{OE}_8") (pintype "bidirectional"))
    )
    (net (code "92") (name "MOD0_VCCIO") (class "Default")
      (node (ref "C24") (pin "1") (pinfunction "1_1") (pintype "bidirectional"))
      (node (ref "C26") (pin "1") (pinfunction "1_1") (pintype "bidirectional"))
      (node (ref "C39") (pin "1") (pinfunction "1_1") (pintype "bidirectional"))
      (node (ref "J3") (pin "4") (pinfunction "VCCIO_4") (pintype "bidirectional"))
      (node (ref "R57") (pin "1") (pinfunction "1_1") (pintype "passive"))
      (node (ref "R58") (pin "1") (pinfunction "1_1") (pintype "passive"))
      (node (ref "S14") (pin "10") (pinfunction "A_10") (pintype "bidirectional"))
      (node (ref "TP50") (pin "TESTPOINT") (pinfunction "TESTPOINT_TESTPOINT") (pintype "bidirectional"))
      (node (ref "U17") (pin "8") (pinfunction "VCC_B_8") (pintype "bidirectional"))
      (node (ref "U19") (pin "8") (pinfunction "VCC_B_8") (pintype "bidirectional"))
      (node (ref "U2") (pin "1") (pinfunction "VCCIO_1") (pintype "power_in"))
      (node (ref "U6") (pin "8") (pinfunction "VCC_B_8") (pintype "bidirectional"))
    )
    (net (code "93") (name "MOD1_5V") (class "Default")
      (node (ref "C19") (pin "1") (pinfunction "1_1") (pintype "bidirectional"))
      (node (ref "J2") (pin "2") (pinfunction "5V_2") (pintype "bidirectional"))
      (node (ref "S13") (pin "1") (pinfunction "VLOAD_1") (pintype "bidirectional"))
      (node (ref "TP58") (pin "TESTPOINT") (pinfunction "TESTPOINT_TESTPOINT") (pintype "bidirectional"))
    )
    (net (code "94") (name "MOD1_5V_METERED") (class "Default")
      (node (ref "C15") (pin "1") (pinfunction "1_1") (pintype "bidirectional"))
      (node (ref "C36") (pin "1") (pinfunction "1_1") (pintype "bidirectional"))
      (node (ref "C65") (pin "1") (pinfunction "1_1") (pintype "bidirectional"))
      (node (ref "R5") (pin "1") (pinfunction "1_1") (pintype "passive"))
      (node (ref "S13") (pin "3") (pinfunction "VSUPP_3") (pintype "bidirectional"))
      (node (ref "S2") (pin "2") (pinfunction "IN_2") (pintype "bidirectional"))
      (node (ref "S2") (pin "3") (pinfunction "IN_3") (pintype "bidirectional"))
      (node (ref "TP17") (pin "TESTPOINT") (pinfunction "TESTPOINT_TESTPOINT") (pintype "bidirectional"))
      (node (ref "U11") (pin "6") (pinfunction "SENSE-_6") (pintype "open_collector"))
    )
    (net (code "95") (name "MOD1_D+_HUB-SW") (class "Default")
      (node (ref "D8") (pin "8") (pinfunction "A_8") (pintype "bidirectional"))
      (node (ref "R75") (pin "2") (pinfunction "2_2") (pintype "passive"))
      (node (ref "R8") (pin "1") (pinfunction "P$1_1") (pintype "passive"))
      (node (ref "U22") (pin "3") (pinfunction "D+_3") (pintype "bidirectional"))
    )
    (net (code "96") (name "MOD1_D-_HUB-SW") (class "Default")
      (node (ref "D8") (pin "6") (pinfunction "B_6") (pintype "bidirectional"))
      (node (ref "R76") (pin "2") (pinfunction "2_2") (pintype "passive"))
      (node (ref "R9") (pin "1") (pinfunction "P$1_1") (pintype "passive"))
      (node (ref "U22") (pin "5") (pinfunction "D-_5") (pintype "bidirectional"))
    )
    (net (code "97") (name "MOD1_DBG_GPIO1") (class "Default")
      (node (ref "J2") (pin "16") (pinfunction "DBG_GPIO1_16") (pintype "bidirectional"))
      (node (ref "Q4") (pin "1") (pinfunction "G_1") (pintype "passive"))
      (node (ref "TP39") (pin "TESTPOINT") (pinfunction "TESTPOINT_TESTPOINT") (pintype "bidirectional"))
    )
    (net (code "98") (name "MOD1_DBG_GPIO2") (class "Default")
      (node (ref "J2") (pin "19") (pinfunction "DBG_GPIO2_19") (pintype "bidirectional"))
      (node (ref "Q5") (pin "1") (pinfunction "G_1") (pintype "passive"))
      (node (ref "TP40") (pin "TESTPOINT") (pinfunction "TESTPOINT_TESTPOINT") (pintype "bidirectional"))
    )
    (net (code "99") (name "MOD1_DBG_RX") (class "Default")
      (node (ref "J2") (pin "18") (pinfunction "DBG_RX_18") (pintype "bidirectional"))
      (node (ref "U3") (pin "30") (pinfunction "TXD_30") (pintype "output"))
    )
    (net (code "100") (name "MOD1_DBG_SWDCLK") (class "Default")
      (node (ref "J2") (pin "21") (pinfunction "DBG_SWDCLK_21") (pintype "bidirectional"))
      (node (ref "S15") (pin "3") (pinfunction "A_3") (pintype "bidirectional"))
    )
    (net (code "101") (name "MOD1_DBG_SWDIO") (class "Default")
      (node (ref "J2") (pin "22") (pinfunction "DBG_SWDIO_22") (pintype "bidirectional"))
      (node (ref "S15") (pin "2") (pinfunction "A_2") (pintype "bidirectional"))
    )
    (net (code "102") (name "MOD1_DBG_TX") (class "Default")
      (node (ref "J2") (pin "17") (pinfunction "DBG_TX_17") (pintype "bidirectional"))
      (node (ref "U3") (pin "2") (pinfunction "RXD_2") (pintype "input"))
    )
    (net (code "103") (name "MOD1_DBG_~{RESET}") (class "Default")
      (node (ref "J2") (pin "20") (pinfunction "DBG_~{RESET}_20") (pintype "bidirectional"))
      (node (ref "S15") (pin "9") (pinfunction "A_9") (pintype "bidirectional"))
      (node (ref "S5") (pin "2") (pinfunction "P$2_2") (pintype "passive"))
    )
    (net (code "104") (name "MOD1_IN") (class "Default")
      (node (ref "J2") (pin "10") (pinfunction "MOD_IN_10") (pintype "bidirectional"))
      (node (ref "TP52") (pin "TESTPOINT") (pinfunction "TESTPOINT_TESTPOINT") (pintype "bidirectional"))
      (node (ref "U18") (pin "7") (pinfunction "B1_7") (pintype "bidirectional"))
    )
    (net (code "105") (name "MOD1_ISO_I2C") (class "Default")
      (node (ref "D5") (pin "A") (pinfunction "ANODE_A") (pintype "bidirectional"))
      (node (ref "R95") (pin "2") (pinfunction "2_2") (pintype "passive"))
      (node (ref "TP1005") (pin "TESTPOINT") (pinfunction "TESTPOINT_TESTPOINT") (pintype "bidirectional"))
      (node (ref "U14") (pin "10") (pinfunction "P1_10") (pintype "bidirectional"))
      (node (ref "U7") (pin "5") (pinfunction "OE_5") (pintype "bidirectional"))
    )
    (net (code "106") (name "MOD1_ISO_POWER") (class "Default")
      (node (ref "D4") (pin "A") (pinfunction "ANODE_A") (pintype "bidirectional"))
      (node (ref "R94") (pin "2") (pinfunction "2_2") (pintype "passive"))
      (node (ref "S13") (pin "4") (pinfunction "EN_4") (pintype "bidirectional"))
      (node (ref "TP1004") (pin "TESTPOINT") (pinfunction "TESTPOINT_TESTPOINT") (pintype "bidirectional"))
      (node (ref "U14") (pin "9") (pinfunction "P0_9") (pintype "bidirectional"))
    )
    (net (code "107") (name "MOD1_ISO_USB") (class "Default")
      (node (ref "D6") (pin "A") (pinfunction "ANODE_A") (pintype "bidirectional"))
      (node (ref "R96") (pin "2") (pinfunction "2_2") (pintype "passive"))
      (node (ref "S10") (pin "6") (pinfunction "S_6") (pintype "bidirectional"))
      (node (ref "TP1006") (pin "TESTPOINT") (pinfunction "TESTPOINT_TESTPOINT") (pintype "bidirectional"))
      (node (ref "U14") (pin "11") (pinfunction "P2_11") (pintype "bidirectional"))
    )
    (net (code "108") (name "MOD1_OUT") (class "Default")
      (node (ref "J2") (pin "8") (pinfunction "MOD_OUT_8") (pintype "bidirectional"))
      (node (ref "TP53") (pin "TESTPOINT") (pinfunction "TESTPOINT_TESTPOINT") (pintype "bidirectional"))
      (node (ref "U20") (pin "7") (pinfunction "B1_7") (pintype "bidirectional"))
    )
    (net (code "109") (name "MOD1_PPS") (class "Default")
      (node (ref "J2") (pin "7") (pinfunction "PPS_7") (pintype "bidirectional"))
      (node (ref "TP47") (pin "TESTPOINT") (pinfunction "TESTPOINT_TESTPOINT") (pintype "bidirectional"))
      (node (ref "U18") (pin "6") (pinfunction "B2_6") (pintype "bidirectional"))
    )
    (net (code "110") (name "MOD1_SCL") (class "Default")
      (node (ref "J2") (pin "5") (pinfunction "SCL_5") (pintype "bidirectional"))
      (node (ref "R60") (pin "2") (pinfunction "2_2") (pintype "passive"))
      (node (ref "TP45") (pin "TESTPOINT") (pinfunction "TESTPOINT_TESTPOINT") (pintype "bidirectional"))
      (node (ref "U7") (pin "6") (pinfunction "B1_6") (pintype "bidirectional"))
    )
    (net (code "111") (name "MOD1_SDA") (class "Default")
      (node (ref "J2") (pin "6") (pinfunction "SDA_6") (pintype "bidirectional"))
      (node (ref "R59") (pin "2") (pinfunction "2_2") (pintype "passive"))
      (node (ref "TP44") (pin "TESTPOINT") (pinfunction "TESTPOINT_TESTPOINT") (pintype "bidirectional"))
      (node (ref "U7") (pin "7") (pinfunction "B0_7") (pintype "bidirectional"))
    )
    (net (code "112") (name "MOD1_USB+") (class "Default")
      (node (ref "J2") (pin "11") (pinfunction "USB_D+_11") (pintype "bidirectional"))
      (node (ref "U22") (pin "1") (pinfunction "D1+_1") (pintype "bidirectional"))
    )
    (net (code "113") (name "MOD1_USB-") (class "Default")
      (node (ref "J2") (pin "12") (pinfunction "USB_D-_12") (pintype "bidirectional"))
      (node (ref "U22") (pin "7") (pinfunction "D1-_7") (pintype "bidirectional"))
    )
    (net (code "114") (name "MOD1_USB_VBUS") (class "Default")
      (node (ref "C32") (pin "1") (pinfunction "1_1") (pintype "bidirectional"))
      (node (ref "C69") (pin "1") (pinfunction "1_1") (pintype "bidirectional"))
      (node (ref "J2") (pin "13") (pinfunction "USB_VBUS_13") (pintype "bidirectional"))
      (node (ref "S2") (pin "6") (pinfunction "OUT_6") (pintype "bidirectional"))
      (node (ref "S2") (pin "7") (pinfunction "OUT_7") (pintype "bidirectional"))
      (node (ref "TP41") (pin "TESTPOINT") (pinfunction "TESTPOINT_TESTPOINT") (pintype "bidirectional"))
    )
    (net (code "115") (name "MOD1_USB_~{EN}") (class "Default")
      (node (ref "S10") (pin "4") (pinfunction "Z_4") (pintype "bidirectional"))
      (node (ref "S2") (pin "4") (pinfunction "~{EN}_4") (pintype "bidirectional"))
      (node (ref "U22") (pin "8") (pinfunction "~{OE}_8") (pintype "bidirectional"))
    )
    (net (code "116") (name "MOD1_VCCIO") (class "Default")
      (node (ref "C25") (pin "1") (pinfunction "1_1") (pintype "bidirectional"))
      (node (ref "C27") (pin "1") (pinfunction "1_1") (pintype "bidirectional"))
      (node (ref "C40") (pin "1") (pinfunction "1_1") (pintype "bidirectional"))
      (node (ref "J2") (pin "4") (pinfunction "VCCIO_4") (pintype "bidirectional"))
      (node (ref "R59") (pin "1") (pinfunction "1_1") (pintype "passive"))
      (node (ref "R60") (pin "1") (pinfunction "1_1") (pintype "passive"))
      (node (ref "S15") (pin "10") (pinfunction "A_10") (pintype "bidirectional"))
      (node (ref "TP55") (pin "TESTPOINT") (pinfunction "TESTPOINT_TESTPOINT") (pintype "bidirectional"))
      (node (ref "U18") (pin "8") (pinfunction "VCC_B_8") (pintype "bidirectional"))
      (node (ref "U20") (pin "8") (pinfunction "VCC_B_8") (pintype "bidirectional"))
      (node (ref "U3") (pin "1") (pinfunction "VCCIO_1") (pintype "power_in"))
      (node (ref "U7") (pin "8") (pinfunction "VCC_B_8") (pintype "bidirectional"))
    )
    (net (code "117") (name "MOD2_USB+") (class "Default")
      (node (ref "D7") (pin "8") (pinfunction "A_8") (pintype "bidirectional"))
      (node (ref "R10") (pin "1") (pinfunction "P$1_1") (pintype "passive"))
      (node (ref "R77") (pin "2") (pinfunction "2_2") (pintype "passive"))
      (node (ref "U16") (pin "47") (pinfunction "PA26_47") (pintype "bidirectional"))
    )
    (net (code "118") (name "MOD2_USB-") (class "Default")
      (node (ref "D7") (pin "6") (pinfunction "B_6") (pintype "bidirectional"))
      (node (ref "R11") (pin "1") (pinfunction "P$1_1") (pintype "passive"))
      (node (ref "R78") (pin "2") (pinfunction "2_2") (pintype "passive"))
      (node (ref "U16") (pin "46") (pinfunction "PA25_46") (pintype "bidirectional"))
    )
    (net (code "119") (name "MOD_SCL") (class "Default")
      (node (ref "J1") (pin "24") (pinfunction "MODULES_SCL_24") (pintype "bidirectional"))
      (node (ref "R65") (pin "1") (pinfunction "1_1") (pintype "passive"))
      (node (ref "TP6") (pin "TESTPOINT") (pinfunction "TESTPOINT_TESTPOINT") (pintype "bidirectional"))
      (node (ref "U16") (pin "44") (pinfunction "PA24_44") (pintype "bidirectional"))
      (node (ref "U6") (pin "3") (pinfunction "A1_3") (pintype "bidirectional"))
      (node (ref "U7") (pin "3") (pinfunction "A1_3") (pintype "bidirectional"))
    )
    (net (code "120") (name "MOD_SDA") (class "Default")
      (node (ref "J1") (pin "23") (pinfunction "MODULES_SDA_23") (pintype "bidirectional"))
      (node (ref "R64") (pin "1") (pinfunction "1_1") (pintype "passive"))
      (node (ref "TP5") (pin "TESTPOINT") (pinfunction "TESTPOINT_TESTPOINT") (pintype "bidirectional"))
      (node (ref "U16") (pin "43") (pinfunction "PA23_43") (pintype "bidirectional"))
      (node (ref "U6") (pin "2") (pinfunction "A0_2") (pintype "bidirectional"))
      (node (ref "U7") (pin "2") (pinfunction "A0_2") (pintype "bidirectional"))
    )
    (net (code "121") (name "Net-(C4-Pad2)") (class "Default")
      (node (ref "C4") (pin "2") (pinfunction "2_2") (pintype "bidirectional"))
      (node (ref "R41") (pin "1") (pinfunction "1_1") (pintype "passive"))
      (node (ref "Y1") (pin "1") (pinfunction "1_1") (pintype "bidirectional"))
    )
    (net (code "122") (name "Net-(D1-CATHODE)") (class "Default")
      (node (ref "D1") (pin "C") (pinfunction "CATHODE_C") (pintype "bidirectional"))
      (node (ref "R16") (pin "2") (pinfunction "2_2") (pintype "passive"))
    )
    (net (code "123") (name "Net-(D2-CATHODE)") (class "Default")
      (node (ref "D2") (pin "C") (pinfunction "CATHODE_C") (pintype "bidirectional"))
      (node (ref "R18") (pin "2") (pinfunction "2_2") (pintype "passive"))
    )
    (net (code "124") (name "Net-(D3-CATHODE)") (class "Default")
      (node (ref "D3") (pin "C") (pinfunction "CATHODE_C") (pintype "bidirectional"))
      (node (ref "R17") (pin "2") (pinfunction "2_2") (pintype "passive"))
    )
    (net (code "125") (name "Net-(D4-CATHODE)") (class "Default")
      (node (ref "D4") (pin "C") (pinfunction "CATHODE_C") (pintype "bidirectional"))
      (node (ref "R19") (pin "2") (pinfunction "2_2") (pintype "passive"))
    )
    (net (code "126") (name "Net-(D5-CATHODE)") (class "Default")
      (node (ref "D5") (pin "C") (pinfunction "CATHODE_C") (pintype "bidirectional"))
      (node (ref "R20") (pin "2") (pinfunction "2_2") (pintype "passive"))
    )
    (net (code "127") (name "Net-(D6-CATHODE)") (class "Default")
      (node (ref "D6") (pin "C") (pinfunction "CATHODE_C") (pintype "bidirectional"))
      (node (ref "R21") (pin "2") (pinfunction "2_2") (pintype "passive"))
    )
    (net (code "128") (name "Net-(FB1-P$1)") (class "Default")
      (node (ref "C47") (pin "1") (pinfunction "1_1") (pintype "bidirectional"))
      (node (ref "FB1") (pin "1") (pinfunction "P$1_1") (pintype "bidirectional"))
      (node (ref "U1") (pin "19") (pinfunction "VCC_19") (pintype "power_in"))
    )
    (net (code "129") (name "Net-(FB1-P$2)") (class "Default")
      (node (ref "C46") (pin "1") (pinfunction "1_1") (pintype "bidirectional"))
      (node (ref "FB1") (pin "2") (pinfunction "P$2_2") (pintype "bidirectional"))
      (node (ref "J4") (pin "1") (pinfunction "+5V_1") (pintype "bidirectional"))
    )
    (net (code "130") (name "Net-(FB2-P$1)") (class "Default")
      (node (ref "C50") (pin "1") (pinfunction "1_1") (pintype "bidirectional"))
      (node (ref "FB2") (pin "1") (pinfunction "P$1_1") (pintype "bidirectional"))
      (node (ref "J5") (pin "1") (pinfunction "+5V_1") (pintype "bidirectional"))
    )
    (net (code "131") (name "Net-(FB2-P$2)") (class "Default")
      (node (ref "C51") (pin "1") (pinfunction "1_1") (pintype "bidirectional"))
      (node (ref "FB2") (pin "2") (pinfunction "P$2_2") (pintype "bidirectional"))
      (node (ref "U2") (pin "19") (pinfunction "VCC_19") (pintype "power_in"))
    )
    (net (code "132") (name "Net-(FB3-P$1)") (class "Default")
      (node (ref "C53") (pin "1") (pinfunction "1_1") (pintype "bidirectional"))
      (node (ref "FB3") (pin "1") (pinfunction "P$1_1") (pintype "bidirectional"))
      (node (ref "J6") (pin "1") (pinfunction "+5V_1") (pintype "bidirectional"))
    )
    (net (code "133") (name "Net-(FB3-P$2)") (class "Default")
      (node (ref "C54") (pin "1") (pinfunction "1_1") (pintype "bidirectional"))
      (node (ref "FB3") (pin "2") (pinfunction "P$2_2") (pintype "bidirectional"))
      (node (ref "U3") (pin "19") (pinfunction "VCC_19") (pintype "power_in"))
    )
    (net (code "134") (name "Net-(FB4-P$1)") (class "Default")
      (node (ref "C56") (pin "1") (pinfunction "1_1") (pintype "bidirectional"))
      (node (ref "FB4") (pin "1") (pinfunction "P$1_1") (pintype "bidirectional"))
      (node (ref "J7") (pin "1") (pinfunction "+5V_1") (pintype "bidirectional"))
    )
    (net (code "135") (name "Net-(FB4-P$2)") (class "Default")
      (node (ref "C57") (pin "1") (pinfunction "1_1") (pintype "bidirectional"))
      (node (ref "FB4") (pin "2") (pinfunction "P$2_2") (pintype "bidirectional"))
      (node (ref "U4") (pin "19") (pinfunction "VCC_19") (pintype "power_in"))
    )
    (net (code "136") (name "Net-(FB5-P$1)") (class "Default")
      (node (ref "C59") (pin "1") (pinfunction "1_1") (pintype "bidirectional"))
      (node (ref "FB5") (pin "1") (pinfunction "P$1_1") (pintype "bidirectional"))
      (node (ref "J8") (pin "1") (pinfunction "+5V_1") (pintype "bidirectional"))
    )
    (net (code "137") (name "Net-(FB5-P$2)") (class "Default")
      (node (ref "C60") (pin "1") (pinfunction "1_1") (pintype "bidirectional"))
      (node (ref "FB5") (pin "2") (pinfunction "P$2_2") (pintype "bidirectional"))
      (node (ref "U5") (pin "19") (pinfunction "VCC_19") (pintype "power_in"))
    )
    (net (code "138") (name "Net-(FB6-P$1)") (class "Default")
      (node (ref "C41") (pin "1") (pinfunction "1_1") (pintype "bidirectional"))
      (node (ref "FB6") (pin "1") (pinfunction "P$1_1") (pintype "bidirectional"))
      (node (ref "U16") (pin "19") (pinfunction "VDDANA_19") (pintype "power_in"))
    )
    (net (code "139") (name "Net-(J4-D+)") (class "Default")
      (node (ref "J4") (pin "3") (pinfunction "D+_3") (pintype "bidirectional"))
      (node (ref "U1") (pin "14") (pinfunction "USBDP_14") (pintype "bidirectional"))
    )
    (net (code "140") (name "Net-(J4-D-)") (class "Default")
      (node (ref "J4") (pin "2") (pinfunction "D-_2") (pintype "bidirectional"))
      (node (ref "U1") (pin "15") (pinfunction "USBDM_15") (pintype "bidirectional"))
    )
    (net (code "141") (name "Net-(J5-D+)") (class "Default")
      (node (ref "J5") (pin "3") (pinfunction "D+_3") (pintype "bidirectional"))
      (node (ref "U2") (pin "14") (pinfunction "USBDP_14") (pintype "bidirectional"))
    )
    (net (code "142") (name "Net-(J5-D-)") (class "Default")
      (node (ref "J5") (pin "2") (pinfunction "D-_2") (pintype "bidirectional"))
      (node (ref "U2") (pin "15") (pinfunction "USBDM_15") (pintype "bidirectional"))
    )
    (net (code "143") (name "Net-(J6-D+)") (class "Default")
      (node (ref "J6") (pin "3") (pinfunction "D+_3") (pintype "bidirectional"))
      (node (ref "U3") (pin "14") (pinfunction "USBDP_14") (pintype "bidirectional"))
    )
    (net (code "144") (name "Net-(J6-D-)") (class "Default")
      (node (ref "J6") (pin "2") (pinfunction "D-_2") (pintype "bidirectional"))
      (node (ref "U3") (pin "15") (pinfunction "USBDM_15") (pintype "bidirectional"))
    )
    (net (code "145") (name "Net-(J7-D+)") (class "Default")
      (node (ref "J7") (pin "3") (pinfunction "D+_3") (pintype "bidirectional"))
      (node (ref "U4") (pin "14") (pinfunction "USBDP_14") (pintype "bidirectional"))
    )
    (net (code "146") (name "Net-(J7-D-)") (class "Default")
      (node (ref "J7") (pin "2") (pinfunction "D-_2") (pintype "bidirectional"))
      (node (ref "U4") (pin "15") (pinfunction "USBDM_15") (pintype "bidirectional"))
    )
    (net (code "147") (name "Net-(J8-D+)") (class "Default")
      (node (ref "J8") (pin "3") (pinfunction "D+_3") (pintype "bidirectional"))
      (node (ref "U5") (pin "14") (pinfunction "USBDP_14") (pintype "bidirectional"))
    )
    (net (code "148") (name "Net-(J8-D-)") (class "Default")
      (node (ref "J8") (pin "2") (pinfunction "D-_2") (pintype "bidirectional"))
      (node (ref "U5") (pin "15") (pinfunction "USBDM_15") (pintype "bidirectional"))
    )
    (net (code "149") (name "Net-(J9-+5V)") (class "Default")
      (node (ref "J9") (pin "1") (pinfunction "+5V_1") (pintype "bidirectional"))
      (node (ref "Q1") (pin "G2") (pinfunction "G2_G2") (pintype "input"))
      (node (ref "R90") (pin "2") (pinfunction "2_2") (pintype "passive"))
    )
    (net (code "150") (name "Net-(J9-D+)") (class "Default")
      (node (ref "J9") (pin "3") (pinfunction "D+_3") (pintype "bidirectional"))
      (node (ref "U23") (pin "1") (pinfunction "D1+_1") (pintype "bidirectional"))
    )
    (net (code "151") (name "Net-(J9-D-)") (class "Default")
      (node (ref "J9") (pin "2") (pinfunction "D-_2") (pintype "bidirectional"))
      (node (ref "U23") (pin "7") (pinfunction "D1-_7") (pintype "bidirectional"))
    )
    (net (code "152") (name "Net-(L1-1)") (class "Default")
      (node (ref "C45") (pin "1") (pinfunction "1_1") (pintype "bidirectional"))
      (node (ref "C67") (pin "1") (pinfunction "1_1") (pintype "bidirectional"))
      (node (ref "L1") (pin "P$1") (pinfunction "1_P$1") (pintype "bidirectional"))
      (node (ref "U16") (pin "7") (pinfunction "VDDOUT_7") (pintype "power_in"))
    )
    (net (code "153") (name "Net-(L1-2)") (class "Default")
      (node (ref "L1") (pin "P$2") (pinfunction "2_P$2") (pintype "bidirectional"))
      (node (ref "U16") (pin "5") (pinfunction "VDDCORE_5") (pintype "power_in"))
    )
    (net (code "154") (name "Net-(LED1-CATHODE)") (class "Default")
      (node (ref "LED1") (pin "C") (pinfunction "CATHODE_C") (pintype "bidirectional"))
      (node (ref "R22") (pin "2") (pinfunction "2_2") (pintype "passive"))
    )
    (net (code "155") (name "Net-(LED2-CATHODE)") (class "Default")
      (node (ref "LED2") (pin "C") (pinfunction "CATHODE_C") (pintype "bidirectional"))
      (node (ref "R23") (pin "2") (pinfunction "2_2") (pintype "passive"))
    )
    (net (code "156") (name "Net-(LED3-CATHODE)") (class "Default")
      (node (ref "LED3") (pin "C") (pinfunction "CATHODE_C") (pintype "bidirectional"))
      (node (ref "R24") (pin "2") (pinfunction "2_2") (pintype "passive"))
    )
    (net (code "157") (name "Net-(LED4-CATHODE)") (class "Default")
      (node (ref "LED4") (pin "C") (pinfunction "CATHODE_C") (pintype "bidirectional"))
      (node (ref "R25") (pin "2") (pinfunction "2_2") (pintype "passive"))
    )
    (net (code "158") (name "Net-(LED5-ANODE)") (class "Default")
      (node (ref "LED5") (pin "A") (pinfunction "ANODE_A") (pintype "bidirectional"))
      (node (ref "R31") (pin "1") (pinfunction "1_1") (pintype "passive"))
    )
    (net (code "159") (name "Net-(LED6-ANODE)") (class "Default")
      (node (ref "LED6") (pin "A") (pinfunction "ANODE_A") (pintype "bidirectional"))
      (node (ref "R32") (pin "1") (pinfunction "1_1") (pintype "passive"))
    )
    (net (code "160") (name "Net-(LED7-ANODE)") (class "Default")
      (node (ref "LED7") (pin "A") (pinfunction "ANODE_A") (pintype "bidirectional"))
      (node (ref "R33") (pin "1") (pinfunction "1_1") (pintype "passive"))
    )
    (net (code "161") (name "Net-(LED8-ANODE)") (class "Default")
      (node (ref "LED8") (pin "A") (pinfunction "ANODE_A") (pintype "bidirectional"))
      (node (ref "R34") (pin "1") (pinfunction "1_1") (pintype "passive"))
    )
    (net (code "162") (name "Net-(LED9-ANODE)") (class "Default")
      (node (ref "LED9") (pin "A") (pinfunction "ANODE_A") (pintype "bidirectional"))
      (node (ref "R35") (pin "1") (pinfunction "1_1") (pintype "passive"))
    )
    (net (code "163") (name "Net-(LED10-CATHODE)") (class "Default")
      (node (ref "LED10") (pin "C") (pinfunction "CATHODE_C") (pintype "bidirectional"))
      (node (ref "R36") (pin "2") (pinfunction "2_2") (pintype "passive"))
    )
    (net (code "164") (name "Net-(LED11-CATHODE)") (class "Default")
      (node (ref "LED11") (pin "C") (pinfunction "CATHODE_C") (pintype "bidirectional"))
      (node (ref "R37") (pin "2") (pinfunction "2_2") (pintype "passive"))
    )
    (net (code "165") (name "Net-(LED12-CATHODE)") (class "Default")
      (node (ref "LED12") (pin "C") (pinfunction "CATHODE_C") (pintype "bidirectional"))
      (node (ref "R38") (pin "2") (pinfunction "2_2") (pintype "passive"))
    )
    (net (code "166") (name "Net-(LED13-CATHODE)") (class "Default")
      (node (ref "LED13") (pin "C") (pinfunction "CATHODE_C") (pintype "bidirectional"))
      (node (ref "R39") (pin "2") (pinfunction "2_2") (pintype "passive"))
    )
    (net (code "167") (name "Net-(Q2-D)") (class "Default")
      (node (ref "Q2") (pin "3") (pinfunction "D_3") (pintype "passive"))
      (node (ref "R22") (pin "1") (pinfunction "1_1") (pintype "passive"))
    )
    (net (code "168") (name "Net-(Q3-D)") (class "Default")
      (node (ref "Q3") (pin "3") (pinfunction "D_3") (pintype "passive"))
      (node (ref "R23") (pin "1") (pinfunction "1_1") (pintype "passive"))
    )
    (net (code "169") (name "Net-(Q4-D)") (class "Default")
      (node (ref "Q4") (pin "3") (pinfunction "D_3") (pintype "passive"))
      (node (ref "R24") (pin "1") (pinfunction "1_1") (pintype "passive"))
    )
    (net (code "170") (name "Net-(Q5-D)") (class "Default")
      (node (ref "Q5") (pin "3") (pinfunction "D_3") (pintype "passive"))
      (node (ref "R25") (pin "1") (pinfunction "1_1") (pintype "passive"))
    )
    (net (code "171") (name "Net-(Q6-D)") (class "Default")
      (node (ref "Q6") (pin "3") (pinfunction "D_3") (pintype "passive"))
      (node (ref "R36") (pin "1") (pinfunction "1_1") (pintype "passive"))
    )
    (net (code "172") (name "Net-(Q7-D)") (class "Default")
      (node (ref "Q7") (pin "3") (pinfunction "D_3") (pintype "passive"))
      (node (ref "R37") (pin "1") (pinfunction "1_1") (pintype "passive"))
    )
    (net (code "173") (name "Net-(Q8-D)") (class "Default")
      (node (ref "Q8") (pin "3") (pinfunction "D_3") (pintype "passive"))
      (node (ref "R38") (pin "1") (pinfunction "1_1") (pintype "passive"))
    )
    (net (code "174") (name "Net-(Q9-D)") (class "Default")
      (node (ref "Q9") (pin "3") (pinfunction "D_3") (pintype "passive"))
      (node (ref "R39") (pin "1") (pinfunction "1_1") (pintype "passive"))
    )
    (net (code "175") (name "Net-(U1-3V3OUT)") (class "Default")
      (node (ref "C48") (pin "1") (pinfunction "1_1") (pintype "bidirectional"))
      (node (ref "U1") (pin "1") (pinfunction "VCCIO_1") (pintype "power_in"))
      (node (ref "U1") (pin "16") (pinfunction "3V3OUT_16") (pintype "output"))
    )
    (net (code "176") (name "Net-(U2-3V3OUT)") (class "Default")
      (node (ref "C49") (pin "1") (pinfunction "1_1") (pintype "bidirectional"))
      (node (ref "U2") (pin "16") (pinfunction "3V3OUT_16") (pintype "output"))
    )
    (net (code "177") (name "Net-(U3-3V3OUT)") (class "Default")
      (node (ref "C52") (pin "1") (pinfunction "1_1") (pintype "bidirectional"))
      (node (ref "U3") (pin "16") (pinfunction "3V3OUT_16") (pintype "output"))
    )
    (net (code "178") (name "Net-(U4-3V3OUT)") (class "Default")
      (node (ref "C55") (pin "1") (pinfunction "1_1") (pintype "bidirectional"))
      (node (ref "U4") (pin "1") (pinfunction "VCCIO_1") (pintype "power_in"))
      (node (ref "U4") (pin "16") (pinfunction "3V3OUT_16") (pintype "output"))
    )
    (net (code "179") (name "Net-(U5-3V3OUT)") (class "Default")
      (node (ref "C58") (pin "1") (pinfunction "1_1") (pintype "bidirectional"))
      (node (ref "U5") (pin "1") (pinfunction "VCCIO_1") (pintype "power_in"))
      (node (ref "U5") (pin "16") (pinfunction "3V3OUT_16") (pintype "output"))
    )
    (net (code "180") (name "Net-(U10-SCL)") (class "Default")
      (node (ref "R50") (pin "1") (pinfunction "1_1") (pintype "passive"))
      (node (ref "U10") (pin "3") (pinfunction "SCL_3") (pintype "open_collector"))
      (node (ref "U15") (pin "13") (pinfunction "SC2_13") (pintype "bidirectional"))
    )
    (net (code "181") (name "Net-(U10-SDA)") (class "Default")
      (node (ref "R49") (pin "1") (pinfunction "1_1") (pintype "passive"))
      (node (ref "U10") (pin "4") (pinfunction "SDA_4") (pintype "open_collector"))
      (node (ref "U15") (pin "12") (pinfunction "SD2_12") (pintype "bidirectional"))
    )
    (net (code "182") (name "Net-(U10-~{ALERT})") (class "Default")
      (node (ref "R51") (pin "1") (pinfunction "1_1") (pintype "passive"))
      (node (ref "U10") (pin "5") (pinfunction "~{ALERT}_5") (pintype "open_collector"))
      (node (ref "U15") (pin "11") (pinfunction "~{INT2}_11") (pintype "bidirectional"))
    )
    (net (code "183") (name "Net-(U11-SCL)") (class "Default")
      (node (ref "R53") (pin "1") (pinfunction "1_1") (pintype "passive"))
      (node (ref "U11") (pin "3") (pinfunction "SCL_3") (pintype "open_collector"))
      (node (ref "U15") (pin "16") (pinfunction "SC3_16") (pintype "bidirectional"))
    )
    (net (code "184") (name "Net-(U11-SDA)") (class "Default")
      (node (ref "R52") (pin "1") (pinfunction "1_1") (pintype "passive"))
      (node (ref "U11") (pin "4") (pinfunction "SDA_4") (pintype "open_collector"))
      (node (ref "U15") (pin "15") (pinfunction "SD3_15") (pintype "bidirectional"))
    )
    (net (code "185") (name "Net-(U11-~{ALERT})") (class "Default")
      (node (ref "R54") (pin "1") (pinfunction "1_1") (pintype "passive"))
      (node (ref "U11") (pin "5") (pinfunction "~{ALERT}_5") (pintype "open_collector"))
      (node (ref "U15") (pin "14") (pinfunction "~{INT3}_14") (pintype "bidirectional"))
    )
    (net (code "186") (name "Net-(U12-BP)") (class "Default")
      (node (ref "C11") (pin "1") (pinfunction "1_1") (pintype "bidirectional"))
      (node (ref "U12") (pin "4") (pinfunction "BP_4") (pintype "bidirectional"))
    )
    (net (code "187") (name "Net-(U12-~{SHDN})") (class "Default")
      (node (ref "R70") (pin "1") (pinfunction "1_1") (pintype "passive"))
      (node (ref "U12") (pin "3") (pinfunction "~{SHDN}_3") (pintype "bidirectional"))
    )
    (net (code "188") (name "Net-(U15-SC0)") (class "Default")
      (node (ref "R44") (pin "1") (pinfunction "1_1") (pintype "passive"))
      (node (ref "U15") (pin "6") (pinfunction "SC0_6") (pintype "bidirectional"))
      (node (ref "U8") (pin "3") (pinfunction "SCL_3") (pintype "open_collector"))
    )
    (net (code "189") (name "Net-(U15-SC1)") (class "Default")
      (node (ref "R47") (pin "1") (pinfunction "1_1") (pintype "passive"))
      (node (ref "U15") (pin "9") (pinfunction "SC1_9") (pintype "bidirectional"))
      (node (ref "U9") (pin "3") (pinfunction "SCL_3") (pintype "open_collector"))
    )
    (net (code "190") (name "Net-(U15-SD0)") (class "Default")
      (node (ref "R43") (pin "1") (pinfunction "1_1") (pintype "passive"))
      (node (ref "U15") (pin "5") (pinfunction "SD0_5") (pintype "bidirectional"))
      (node (ref "U8") (pin "4") (pinfunction "SDA_4") (pintype "open_collector"))
    )
    (net (code "191") (name "Net-(U15-SD1)") (class "Default")
      (node (ref "R46") (pin "1") (pinfunction "1_1") (pintype "passive"))
      (node (ref "U15") (pin "8") (pinfunction "SD1_8") (pintype "bidirectional"))
      (node (ref "U9") (pin "4") (pinfunction "SDA_4") (pintype "open_collector"))
    )
    (net (code "192") (name "Net-(U15-~{INT0})") (class "Default")
      (node (ref "R45") (pin "1") (pinfunction "1_1") (pintype "passive"))
      (node (ref "U15") (pin "4") (pinfunction "~{INT0}_4") (pintype "bidirectional"))
      (node (ref "U8") (pin "5") (pinfunction "~{ALERT}_5") (pintype "open_collector"))
    )
    (net (code "193") (name "Net-(U15-~{INT1})") (class "Default")
      (node (ref "R48") (pin "1") (pinfunction "1_1") (pintype "passive"))
      (node (ref "U15") (pin "7") (pinfunction "~{INT1}_7") (pintype "bidirectional"))
      (node (ref "U9") (pin "5") (pinfunction "~{ALERT}_5") (pintype "open_collector"))
    )
    (net (code "194") (name "Net-(U16-BIASH)") (class "Default")
      (node (ref "U16") (pin "28") (pinfunction "BIASH_28") (pintype "bidirectional"))
      (node (ref "U16") (pin "29") (pinfunction "BIASL_29") (pintype "bidirectional"))
    )
    (net (code "195") (name "Net-(U16-CAPH)") (class "Default")
      (node (ref "U16") (pin "25") (pinfunction "CAPH_25") (pintype "bidirectional"))
      (node (ref "U16") (pin "26") (pinfunction "CAPL_26") (pintype "bidirectional"))
    )
    (net (code "196") (name "Net-(U16-PA02)") (class "Default")
      (node (ref "R1") (pin "2") (pinfunction "2_2") (pintype "passive"))
      (node (ref "R71") (pin "1") (pinfunction "1_1") (pintype "passive"))
      (node (ref "U16") (pin "3") (pinfunction "PA02_3") (pintype "bidirectional"))
    )
    (net (code "197") (name "Net-(U21-D2+)") (class "Default")
      (node (ref "R12") (pin "1") (pinfunction "1_1") (pintype "passive"))
      (node (ref "U21") (pin "2") (pinfunction "D2+_2") (pintype "bidirectional"))
    )
    (net (code "198") (name "Net-(U21-D2-)") (class "Default")
      (node (ref "R13") (pin "1") (pinfunction "1_1") (pintype "passive"))
      (node (ref "U21") (pin "6") (pinfunction "D2-_6") (pintype "bidirectional"))
    )
    (net (code "199") (name "Net-(U22-D2+)") (class "Default")
      (node (ref "R14") (pin "1") (pinfunction "1_1") (pintype "passive"))
      (node (ref "U22") (pin "2") (pinfunction "D2+_2") (pintype "bidirectional"))
    )
    (net (code "200") (name "Net-(U22-D2-)") (class "Default")
      (node (ref "R15") (pin "1") (pinfunction "1_1") (pintype "passive"))
      (node (ref "U22") (pin "6") (pinfunction "D2-_6") (pintype "bidirectional"))
    )
    (net (code "201") (name "Net-(U23-S)") (class "Default")
      (node (ref "Q1") (pin "D2") (pinfunction "D2_D2") (pintype "bidirectional"))
      (node (ref "R89") (pin "1") (pinfunction "1_1") (pintype "passive"))
      (node (ref "U23") (pin "10") (pinfunction "S_10") (pintype "bidirectional"))
    )
    (net (code "202") (name "Net-(U24-DP0PUR)") (class "Default")
      (node (ref "R40") (pin "2") (pinfunction "2_2") (pintype "passive"))
      (node (ref "U24") (pin "2") (pinfunction "DP0PUR_2") (pintype "bidirectional"))
    )
    (net (code "203") (name "Net-(U24-XTAL1)") (class "Default")
      (node (ref "C3") (pin "2") (pinfunction "2_2") (pintype "bidirectional"))
      (node (ref "U24") (pin "45") (pinfunction "XTAL1_45") (pintype "bidirectional"))
      (node (ref "Y1") (pin "3") (pinfunction "2_3") (pintype "bidirectional"))
    )
    (net (code "204") (name "Net-(U24-XTAL2)") (class "Default")
      (node (ref "R41") (pin "2") (pinfunction "2_2") (pintype "passive"))
      (node (ref "U24") (pin "44") (pinfunction "XTAL2_44") (pintype "bidirectional"))
    )
    (net (code "205") (name "PPS") (class "Default")
      (node (ref "J1") (pin "25") (pinfunction "PPS_25") (pintype "bidirectional"))
      (node (ref "TP10") (pin "TESTPOINT") (pinfunction "TESTPOINT_TESTPOINT") (pintype "bidirectional"))
      (node (ref "U16") (pin "37") (pinfunction "PA18_37") (pintype "bidirectional"))
      (node (ref "U17") (pin "3") (pinfunction "A2_3") (pintype "bidirectional"))
      (node (ref "U18") (pin "3") (pinfunction "A2_3") (pintype "bidirectional"))
    )
    (net (code "206") (name "PROG0_EN") (class "Default")
      (node (ref "R26") (pin "2") (pinfunction "2_2") (pintype "passive"))
      (node (ref "R31") (pin "2") (pinfunction "2_2") (pintype "passive"))
      (node (ref "S11") (pin "1") (pinfunction "A_1") (pintype "bidirectional"))
      (node (ref "S14") (pin "12") (pinfunction "CTRL_12") (pintype "bidirectional"))
      (node (ref "S14") (pin "13") (pinfunction "CTRL_13") (pintype "bidirectional"))
      (node (ref "S14") (pin "5") (pinfunction "CTRL_5") (pintype "bidirectional"))
      (node (ref "S14") (pin "6") (pinfunction "CTRL_6") (pintype "bidirectional"))
    )
    (net (code "207") (name "PROG1_EN") (class "Default")
      (node (ref "R27") (pin "2") (pinfunction "2_2") (pintype "passive"))
      (node (ref "R32") (pin "2") (pinfunction "2_2") (pintype "passive"))
      (node (ref "S11") (pin "2") (pinfunction "B_2") (pintype "bidirectional"))
      (node (ref "S15") (pin "12") (pinfunction "CTRL_12") (pintype "bidirectional"))
      (node (ref "S15") (pin "13") (pinfunction "CTRL_13") (pintype "bidirectional"))
      (node (ref "S15") (pin "5") (pinfunction "CTRL_5") (pintype "bidirectional"))
      (node (ref "S15") (pin "6") (pinfunction "CTRL_6") (pintype "bidirectional"))
    )
    (net (code "208") (name "PROG2_EN") (class "Default")
      (node (ref "R28") (pin "2") (pinfunction "2_2") (pintype "passive"))
      (node (ref "R33") (pin "2") (pinfunction "2_2") (pintype "passive"))
      (node (ref "S11") (pin "3") (pinfunction "C_3") (pintype "bidirectional"))
      (node (ref "S16") (pin "12") (pinfunction "CTRL_12") (pintype "bidirectional"))
      (node (ref "S16") (pin "13") (pinfunction "CTRL_13") (pintype "bidirectional"))
      (node (ref "S16") (pin "5") (pinfunction "CTRL_5") (pintype "bidirectional"))
      (node (ref "S16") (pin "6") (pinfunction "CTRL_6") (pintype "bidirectional"))
    )
    (net (code "209") (name "PROG3_EN") (class "Default")
      (node (ref "R29") (pin "2") (pinfunction "2_2") (pintype "passive"))
      (node (ref "R34") (pin "2") (pinfunction "2_2") (pintype "passive"))
      (node (ref "S11") (pin "4") (pinfunction "D_4") (pintype "bidirectional"))
      (node (ref "S17") (pin "12") (pinfunction "CTRL_12") (pintype "bidirectional"))
      (node (ref "S17") (pin "13") (pinfunction "CTRL_13") (pintype "bidirectional"))
      (node (ref "S17") (pin "5") (pinfunction "CTRL_5") (pintype "bidirectional"))
      (node (ref "S17") (pin "6") (pinfunction "CTRL_6") (pintype "bidirectional"))
    )
    (net (code "210") (name "PROG4_EN") (class "Default")
      (node (ref "R30") (pin "2") (pinfunction "2_2") (pintype "passive"))
      (node (ref "R35") (pin "2") (pinfunction "2_2") (pintype "passive"))
      (node (ref "S11") (pin "5") (pinfunction "E_5") (pintype "bidirectional"))
      (node (ref "S18") (pin "12") (pinfunction "CTRL_12") (pintype "bidirectional"))
      (node (ref "S18") (pin "13") (pinfunction "CTRL_13") (pintype "bidirectional"))
      (node (ref "S18") (pin "5") (pinfunction "CTRL_5") (pintype "bidirectional"))
      (node (ref "S18") (pin "6") (pinfunction "CTRL_6") (pintype "bidirectional"))
    )
    (net (code "211") (name "RADIO_RX") (class "Default")
      (node (ref "U1") (pin "30") (pinfunction "TXD_30") (pintype "output"))
      (node (ref "U16") (pin "23") (pinfunction "PA11_23") (pintype "bidirectional"))
    )
    (net (code "212") (name "RADIO_SWDCLK") (class "Default")
      (node (ref "R88") (pin "1") (pinfunction "1_1") (pintype "passive"))
      (node (ref "S16") (pin "3") (pinfunction "A_3") (pintype "bidirectional"))
      (node (ref "U16") (pin "9") (pinfunction "TCK_9") (pintype "bidirectional"))
    )
    (net (code "213") (name "RADIO_SWDIO") (class "Default")
      (node (ref "R87") (pin "1") (pinfunction "1_1") (pintype "passive"))
      (node (ref "S16") (pin "2") (pinfunction "A_2") (pintype "bidirectional"))
      (node (ref "U16") (pin "10") (pinfunction "PA03_10") (pintype "bidirectional"))
    )
    (net (code "214") (name "RADIO_TX") (class "Default")
      (node (ref "U1") (pin "2") (pinfunction "RXD_2") (pintype "input"))
      (node (ref "U16") (pin "24") (pinfunction "PA12_24") (pintype "bidirectional"))
    )
    (net (code "215") (name "RADIO_~{RESET}") (class "Default")
      (node (ref "S16") (pin "9") (pinfunction "A_9") (pintype "bidirectional"))
      (node (ref "S3") (pin "2") (pinfunction "P$2_2") (pintype "passive"))
      (node (ref "U16") (pin "4") (pinfunction "~{RESET}_4") (pintype "bidirectional"))
    )
    (net (code "216") (name "SMBCLK") (class "Default")
      (node (ref "J1") (pin "5") (pinfunction "SMBCLK_5") (pintype "bidirectional"))
      (node (ref "R62") (pin "1") (pinfunction "1_1") (pintype "passive"))
      (node (ref "TP2") (pin "TESTPOINT") (pinfunction "TESTPOINT_TESTPOINT") (pintype "bidirectional"))
      (node (ref "U13") (pin "19") (pinfunction "SCL_19") (pintype "bidirectional"))
      (node (ref "U14") (pin "19") (pinfunction "SCL_19") (pintype "bidirectional"))
      (node (ref "U15") (pin "18") (pinfunction "SCL_18") (pintype "bidirectional"))
    )
    (net (code "217") (name "SMBDATA") (class "Default")
      (node (ref "J1") (pin "3") (pinfunction "SMBDATA_3") (pintype "bidirectional"))
      (node (ref "R61") (pin "1") (pinfunction "1_1") (pintype "passive"))
      (node (ref "TP1") (pin "TESTPOINT") (pinfunction "TESTPOINT_TESTPOINT") (pintype "bidirectional"))
      (node (ref "U13") (pin "20") (pinfunction "SDA_20") (pintype "bidirectional"))
      (node (ref "U14") (pin "20") (pinfunction "SDA_20") (pintype "bidirectional"))
      (node (ref "U15") (pin "19") (pinfunction "SDA_19") (pintype "bidirectional"))
    )
    (net (code "218") (name "USB+") (class "Default")
      (node (ref "R40") (pin "1") (pinfunction "1_1") (pintype "passive"))
      (node (ref "U23") (pin "3") (pinfunction "D+_3") (pintype "bidirectional"))
      (node (ref "U24") (pin "3") (pinfunction "DP0_3") (pintype "bidirectional"))
    )
    (net (code "219") (name "USB-") (class "Default")
      (node (ref "U23") (pin "5") (pinfunction "D-_5") (pintype "bidirectional"))
      (node (ref "U24") (pin "4") (pinfunction "DM0_4") (pintype "bidirectional"))
    )
    (net (code "220") (name "USB_SUSPEND_STATUS") (class "Default")
      (node (ref "TP31") (pin "TESTPOINT") (pinfunction "TESTPOINT_TESTPOINT") (pintype "bidirectional"))
      (node (ref "U24") (pin "1") (pinfunction "SUSPND_1") (pintype "bidirectional"))
    )
    (net (code "221") (name "VCC_BACKPLANE") (class "Default")
      (node (ref "C12") (pin "1") (pinfunction "1_1") (pintype "bidirectional"))
      (node (ref "C16") (pin "1") (pinfunction "1_1") (pintype "bidirectional"))
      (node (ref "C17") (pin "1") (pinfunction "1_1") (pintype "bidirectional"))
      (node (ref "C20") (pin "1") (pinfunction "1_1") (pintype "bidirectional"))
      (node (ref "C21") (pin "1") (pinfunction "1_1") (pintype "bidirectional"))
      (node (ref "C22") (pin "1") (pinfunction "1_1") (pintype "bidirectional"))
      (node (ref "C23") (pin "1") (pinfunction "1_1") (pintype "bidirectional"))
      (node (ref "C28") (pin "2") (pinfunction "2_2") (pintype "bidirectional"))
      (node (ref "C29") (pin "1") (pinfunction "1_1") (pintype "bidirectional"))
      (node (ref "C30") (pin "1") (pinfunction "1_1") (pintype "bidirectional"))
      (node (ref "C33") (pin "1") (pinfunction "1_1") (pintype "bidirectional"))
      (node (ref "C34") (pin "1") (pinfunction "1_1") (pintype "bidirectional"))
      (node (ref "C37") (pin "2") (pinfunction "2_2") (pintype "bidirectional"))
      (node (ref "C38") (pin "2") (pinfunction "2_2") (pintype "bidirectional"))
      (node (ref "C61") (pin "2") (pinfunction "2_2") (pintype "bidirectional"))
      (node (ref "C66") (pin "2") (pinfunction "2_2") (pintype "bidirectional"))
      (node (ref "J1") (pin "2") (pinfunction "VCC_CONTROLLER_2") (pintype "bidirectional"))
      (node (ref "R2") (pin "1") (pinfunction "1_1") (pintype "passive"))
      (node (ref "R42") (pin "1") (pinfunction "1_1") (pintype "passive"))
      (node (ref "R55") (pin "2") (pinfunction "2_2") (pintype "passive"))
      (node (ref "R56") (pin "2") (pinfunction "2_2") (pintype "passive"))
      (node (ref "R61") (pin "2") (pinfunction "2_2") (pintype "passive"))
      (node (ref "R62") (pin "2") (pinfunction "2_2") (pintype "passive"))
      (node (ref "R63") (pin "2") (pinfunction "2_2") (pintype "passive"))
      (node (ref "R64") (pin "2") (pinfunction "2_2") (pintype "passive"))
      (node (ref "R65") (pin "2") (pinfunction "2_2") (pintype "passive"))
      (node (ref "R66") (pin "2") (pinfunction "2_2") (pintype "passive"))
      (node (ref "R67") (pin "2") (pinfunction "2_2") (pintype "passive"))
      (node (ref "R68") (pin "2") (pinfunction "2_2") (pintype "passive"))
      (node (ref "R69") (pin "2") (pinfunction "2_2") (pintype "passive"))
      (node (ref "R72") (pin "2") (pinfunction "2_2") (pintype "passive"))
      (node (ref "R89") (pin "2") (pinfunction "2_2") (pintype "passive"))
      (node (ref "S10") (pin "3") (pinfunction "I0_3") (pintype "bidirectional"))
      (node (ref "S10") (pin "5") (pinfunction "VCC_5") (pintype "bidirectional"))
      (node (ref "S9") (pin "3") (pinfunction "I0_3") (pintype "bidirectional"))
      (node (ref "S9") (pin "5") (pinfunction "VCC_5") (pintype "bidirectional"))
      (node (ref "TP24") (pin "TESTPOINT") (pinfunction "TESTPOINT_TESTPOINT") (pintype "bidirectional"))
      (node (ref "TP8") (pin "TESTPOINT") (pinfunction "TESTPOINT_TESTPOINT") (pintype "bidirectional"))
      (node (ref "U13") (pin "18") (pinfunction "VCC_18") (pintype "bidirectional"))
      (node (ref "U14") (pin "18") (pinfunction "VCC_18") (pintype "bidirectional"))
      (node (ref "U14") (pin "3") (pinfunction "A0_3") (pintype "bidirectional"))
      (node (ref "U15") (pin "20") (pinfunction "VCC_20") (pintype "bidirectional"))
      (node (ref "U17") (pin "1") (pinfunction "VCC_A_1") (pintype "bidirectional"))
      (node (ref "U17") (pin "5") (pinfunction "DIR_5") (pintype "bidirectional"))
      (node (ref "U18") (pin "1") (pinfunction "VCC_A_1") (pintype "bidirectional"))
      (node (ref "U18") (pin "5") (pinfunction "DIR_5") (pintype "bidirectional"))
      (node (ref "U19") (pin "1") (pinfunction "VCC_A_1") (pintype "bidirectional"))
      (node (ref "U20") (pin "1") (pinfunction "VCC_A_1") (pintype "bidirectional"))
      (node (ref "U21") (pin "9") (pinfunction "VCC_9") (pintype "bidirectional"))
      (node (ref "U22") (pin "9") (pinfunction "VCC_9") (pintype "bidirectional"))
      (node (ref "U23") (pin "9") (pinfunction "VCC_9") (pintype "bidirectional"))
      (node (ref "U24") (pin "46") (pinfunction "VCC_46") (pintype "bidirectional"))
      (node (ref "U24") (pin "47") (pinfunction "~{EXTMEM}_47") (pintype "bidirectional"))
      (node (ref "U24") (pin "8") (pinfunction "EEDATA/~{GANGED}_8") (pintype "bidirectional"))
      (node (ref "U24") (pin "9") (pinfunction "VCC_9") (pintype "bidirectional"))
      (node (ref "U6") (pin "1") (pinfunction "VCC_A_1") (pintype "bidirectional"))
      (node (ref "U7") (pin "1") (pinfunction "VCC_A_1") (pintype "bidirectional"))
      (node (ref "U8") (pin "6") (pinfunction "SENSE-_6") (pintype "open_collector"))
    )
    (net (code "222") (name "VCC_LINUX") (class "Default")
      (node (ref "C13") (pin "1") (pinfunction "1_1") (pintype "bidirectional"))
      (node (ref "J1") (pin "4") (pinfunction "VCC_LINUX_4") (pintype "bidirectional"))
      (node (ref "R3") (pin "1") (pinfunction "1_1") (pintype "passive"))
      (node (ref "TP18") (pin "TESTPOINT") (pinfunction "TESTPOINT_TESTPOINT") (pintype "bidirectional"))
      (node (ref "TP23") (pin "TESTPOINT") (pinfunction "TESTPOINT_TESTPOINT") (pintype "bidirectional"))
      (node (ref "U9") (pin "6") (pinfunction "SENSE-_6") (pintype "open_collector"))
    )
    (net (code "223") (name "unconnected-(D7-C-Pad2)") (class "Default")
      (node (ref "D7") (pin "2") (pinfunction "C_2") (pintype "bidirectional"))
    )
    (net (code "224") (name "unconnected-(D7-D-Pad4)") (class "Default")
      (node (ref "D7") (pin "4") (pinfunction "D_4") (pintype "bidirectional"))
    )
    (net (code "225") (name "unconnected-(J1B-MOD5_IN-Pad15)") (class "Default")
      (node (ref "J1") (pin "15") (pinfunction "MOD5_IN_15") (pintype "bidirectional"))
    )
    (net (code "226") (name "unconnected-(J1B-MOD5_OUT-Pad16)") (class "Default")
      (node (ref "J1") (pin "16") (pinfunction "MOD5_OUT_16") (pintype "bidirectional"))
    )
    (net (code "227") (name "unconnected-(J1B-MOD6_IN-Pad17)") (class "Default")
      (node (ref "J1") (pin "17") (pinfunction "MOD6_IN_17") (pintype "bidirectional"))
    )
    (net (code "228") (name "unconnected-(J1B-MOD6_OUT-Pad18)") (class "Default")
      (node (ref "J1") (pin "18") (pinfunction "MOD6_OUT_18") (pintype "bidirectional"))
    )
    (net (code "229") (name "unconnected-(J1B-MOD7_IN-Pad19)") (class "Default")
      (node (ref "J1") (pin "19") (pinfunction "MOD7_IN_19") (pintype "bidirectional"))
    )
    (net (code "230") (name "unconnected-(J1B-MOD7_OUT-Pad20)") (class "Default")
      (node (ref "J1") (pin "20") (pinfunction "MOD7_OUT_20") (pintype "bidirectional"))
    )
    (net (code "231") (name "unconnected-(J4-ID-Pad4)") (class "Default")
      (node (ref "J4") (pin "4") (pinfunction "ID_4") (pintype "bidirectional"))
    )
    (net (code "232") (name "unconnected-(J5-ID-Pad4)") (class "Default")
      (node (ref "J5") (pin "4") (pinfunction "ID_4") (pintype "bidirectional"))
    )
    (net (code "233") (name "unconnected-(J6-ID-Pad4)") (class "Default")
      (node (ref "J6") (pin "4") (pinfunction "ID_4") (pintype "bidirectional"))
    )
    (net (code "234") (name "unconnected-(J7-ID-Pad4)") (class "Default")
      (node (ref "J7") (pin "4") (pinfunction "ID_4") (pintype "bidirectional"))
    )
    (net (code "235") (name "unconnected-(J8-ID-Pad4)") (class "Default")
      (node (ref "J8") (pin "4") (pinfunction "ID_4") (pintype "bidirectional"))
    )
    (net (code "236") (name "unconnected-(J9-ID-Pad4)") (class "Default")
      (node (ref "J9") (pin "4") (pinfunction "ID_4") (pintype "bidirectional"))
    )
    (net (code "237") (name "unconnected-(J10-Pad2)") (class "Default")
      (node (ref "J10") (pin "2") (pinfunction "2_2") (pintype "passive"))
    )
    (net (code "238") (name "unconnected-(J11-NC-Pad3)") (class "Default")
      (node (ref "J11") (pin "3") (pinfunction "NC_3") (pintype "bidirectional"))
    )
    (net (code "239") (name "unconnected-(Q1-PadD1)") (class "Default")
      (node (ref "Q1") (pin "D1") (pinfunction "D1_D1") (pintype "bidirectional"))
    )
    (net (code "240") (name "unconnected-(Q1-PadG1)") (class "Default")
      (node (ref "Q1") (pin "G1") (pinfunction "G1_G1") (pintype "input"))
    )
    (net (code "241") (name "unconnected-(S11-F-Pad6)") (class "Default")
      (node (ref "S11") (pin "6") (pinfunction "F_6") (pintype "bidirectional"))
    )
    (net (code "242") (name "unconnected-(S19-B-Pad2)") (class "Default")
      (node (ref "S19") (pin "2") (pinfunction "B_2") (pintype "bidirectional"))
    )
    (net (code "243") (name "unconnected-(U1-CBUS0-Pad22)") (class "Default")
      (node (ref "U1") (pin "22") (pinfunction "CBUS0_22") (pintype "bidirectional"))
    )
    (net (code "244") (name "unconnected-(U1-CBUS1-Pad21)") (class "Default")
      (node (ref "U1") (pin "21") (pinfunction "CBUS1_21") (pintype "bidirectional"))
    )
    (net (code "245") (name "unconnected-(U1-CBUS2-Pad10)") (class "Default")
      (node (ref "U1") (pin "10") (pinfunction "CBUS2_10") (pintype "bidirectional"))
    )
    (net (code "246") (name "unconnected-(U1-CBUS3-Pad11)") (class "Default")
      (node (ref "U1") (pin "11") (pinfunction "CBUS3_11") (pintype "bidirectional"))
    )
    (net (code "247") (name "unconnected-(U1-CBUS4-Pad9)") (class "Default")
      (node (ref "U1") (pin "9") (pinfunction "CBUS4_9") (pintype "bidirectional"))
    )
    (net (code "248") (name "unconnected-(U1-OSCI-Pad27)") (class "Default")
      (node (ref "U1") (pin "27") (pinfunction "OSCI_27") (pintype "input"))
    )
    (net (code "249") (name "unconnected-(U1-OSCO-Pad28)") (class "Default")
      (node (ref "U1") (pin "28") (pinfunction "OSCO_28") (pintype "output"))
    )
    (net (code "250") (name "unconnected-(U1-~{CTS}-Pad8)") (class "Default")
      (node (ref "U1") (pin "8") (pinfunction "~{CTS}_8") (pintype "input"))
    )
    (net (code "251") (name "unconnected-(U1-~{DCD}-Pad7)") (class "Default")
      (node (ref "U1") (pin "7") (pinfunction "~{DCD}_7") (pintype "input"))
    )
    (net (code "252") (name "unconnected-(U1-~{DSR}-Pad6)") (class "Default")
      (node (ref "U1") (pin "6") (pinfunction "~{DSR}_6") (pintype "input"))
    )
    (net (code "253") (name "unconnected-(U1-~{DTR}-Pad31)") (class "Default")
      (node (ref "U1") (pin "31") (pinfunction "~{DTR}_31") (pintype "output"))
    )
    (net (code "254") (name "unconnected-(U1-~{RESET}-Pad18)") (class "Default")
      (node (ref "U1") (pin "18") (pinfunction "~{RESET}_18") (pintype "input"))
    )
    (net (code "255") (name "unconnected-(U1-~{RI}-Pad3)") (class "Default")
      (node (ref "U1") (pin "3") (pinfunction "~{RI}_3") (pintype "input"))
    )
    (net (code "256") (name "unconnected-(U1-~{RTS}-Pad32)") (class "Default")
      (node (ref "U1") (pin "32") (pinfunction "~{RTS}_32") (pintype "output"))
    )
    (net (code "257") (name "unconnected-(U2-CBUS0-Pad22)") (class "Default")
      (node (ref "U2") (pin "22") (pinfunction "CBUS0_22") (pintype "bidirectional"))
    )
    (net (code "258") (name "unconnected-(U2-CBUS1-Pad21)") (class "Default")
      (node (ref "U2") (pin "21") (pinfunction "CBUS1_21") (pintype "bidirectional"))
    )
    (net (code "259") (name "unconnected-(U2-CBUS2-Pad10)") (class "Default")
      (node (ref "U2") (pin "10") (pinfunction "CBUS2_10") (pintype "bidirectional"))
    )
    (net (code "260") (name "unconnected-(U2-CBUS3-Pad11)") (class "Default")
      (node (ref "U2") (pin "11") (pinfunction "CBUS3_11") (pintype "bidirectional"))
    )
    (net (code "261") (name "unconnected-(U2-CBUS4-Pad9)") (class "Default")
      (node (ref "U2") (pin "9") (pinfunction "CBUS4_9") (pintype "bidirectional"))
    )
    (net (code "262") (name "unconnected-(U2-OSCI-Pad27)") (class "Default")
      (node (ref "U2") (pin "27") (pinfunction "OSCI_27") (pintype "input"))
    )
    (net (code "263") (name "unconnected-(U2-OSCO-Pad28)") (class "Default")
      (node (ref "U2") (pin "28") (pinfunction "OSCO_28") (pintype "output"))
    )
    (net (code "264") (name "unconnected-(U2-~{CTS}-Pad8)") (class "Default")
      (node (ref "U2") (pin "8") (pinfunction "~{CTS}_8") (pintype "input"))
    )
    (net (code "265") (name "unconnected-(U2-~{DCD}-Pad7)") (class "Default")
      (node (ref "U2") (pin "7") (pinfunction "~{DCD}_7") (pintype "input"))
    )
    (net (code "266") (name "unconnected-(U2-~{DSR}-Pad6)") (class "Default")
      (node (ref "U2") (pin "6") (pinfunction "~{DSR}_6") (pintype "input"))
    )
    (net (code "267") (name "unconnected-(U2-~{DTR}-Pad31)") (class "Default")
      (node (ref "U2") (pin "31") (pinfunction "~{DTR}_31") (pintype "output"))
    )
    (net (code "268") (name "unconnected-(U2-~{RESET}-Pad18)") (class "Default")
      (node (ref "U2") (pin "18") (pinfunction "~{RESET}_18") (pintype "input"))
    )
    (net (code "269") (name "unconnected-(U2-~{RI}-Pad3)") (class "Default")
      (node (ref "U2") (pin "3") (pinfunction "~{RI}_3") (pintype "input"))
    )
    (net (code "270") (name "unconnected-(U2-~{RTS}-Pad32)") (class "Default")
      (node (ref "U2") (pin "32") (pinfunction "~{RTS}_32") (pintype "output"))
    )
    (net (code "271") (name "unconnected-(U3-CBUS0-Pad22)") (class "Default")
      (node (ref "U3") (pin "22") (pinfunction "CBUS0_22") (pintype "bidirectional"))
    )
    (net (code "272") (name "unconnected-(U3-CBUS1-Pad21)") (class "Default")
      (node (ref "U3") (pin "21") (pinfunction "CBUS1_21") (pintype "bidirectional"))
    )
    (net (code "273") (name "unconnected-(U3-CBUS2-Pad10)") (class "Default")
      (node (ref "U3") (pin "10") (pinfunction "CBUS2_10") (pintype "bidirectional"))
    )
    (net (code "274") (name "unconnected-(U3-CBUS3-Pad11)") (class "Default")
      (node (ref "U3") (pin "11") (pinfunction "CBUS3_11") (pintype "bidirectional"))
    )
    (net (code "275") (name "unconnected-(U3-CBUS4-Pad9)") (class "Default")
      (node (ref "U3") (pin "9") (pinfunction "CBUS4_9") (pintype "bidirectional"))
    )
    (net (code "276") (name "unconnected-(U3-OSCI-Pad27)") (class "Default")
      (node (ref "U3") (pin "27") (pinfunction "OSCI_27") (pintype "input"))
    )
    (net (code "277") (name "unconnected-(U3-OSCO-Pad28)") (class "Default")
      (node (ref "U3") (pin "28") (pinfunction "OSCO_28") (pintype "output"))
    )
    (net (code "278") (name "unconnected-(U3-~{CTS}-Pad8)") (class "Default")
      (node (ref "U3") (pin "8") (pinfunction "~{CTS}_8") (pintype "input"))
    )
    (net (code "279") (name "unconnected-(U3-~{DCD}-Pad7)") (class "Default")
      (node (ref "U3") (pin "7") (pinfunction "~{DCD}_7") (pintype "input"))
    )
    (net (code "280") (name "unconnected-(U3-~{DSR}-Pad6)") (class "Default")
      (node (ref "U3") (pin "6") (pinfunction "~{DSR}_6") (pintype "input"))
    )
    (net (code "281") (name "unconnected-(U3-~{DTR}-Pad31)") (class "Default")
      (node (ref "U3") (pin "31") (pinfunction "~{DTR}_31") (pintype "output"))
    )
    (net (code "282") (name "unconnected-(U3-~{RESET}-Pad18)") (class "Default")
      (node (ref "U3") (pin "18") (pinfunction "~{RESET}_18") (pintype "input"))
    )
    (net (code "283") (name "unconnected-(U3-~{RI}-Pad3)") (class "Default")
      (node (ref "U3") (pin "3") (pinfunction "~{RI}_3") (pintype "input"))
    )
    (net (code "284") (name "unconnected-(U3-~{RTS}-Pad32)") (class "Default")
      (node (ref "U3") (pin "32") (pinfunction "~{RTS}_32") (pintype "output"))
    )
    (net (code "285") (name "unconnected-(U4-CBUS0-Pad22)") (class "Default")
      (node (ref "U4") (pin "22") (pinfunction "CBUS0_22") (pintype "bidirectional"))
    )
    (net (code "286") (name "unconnected-(U4-CBUS1-Pad21)") (class "Default")
      (node (ref "U4") (pin "21") (pinfunction "CBUS1_21") (pintype "bidirectional"))
    )
    (net (code "287") (name "unconnected-(U4-CBUS2-Pad10)") (class "Default")
      (node (ref "U4") (pin "10") (pinfunction "CBUS2_10") (pintype "bidirectional"))
    )
    (net (code "288") (name "unconnected-(U4-CBUS3-Pad11)") (class "Default")
      (node (ref "U4") (pin "11") (pinfunction "CBUS3_11") (pintype "bidirectional"))
    )
    (net (code "289") (name "unconnected-(U4-CBUS4-Pad9)") (class "Default")
      (node (ref "U4") (pin "9") (pinfunction "CBUS4_9") (pintype "bidirectional"))
    )
    (net (code "290") (name "unconnected-(U4-OSCI-Pad27)") (class "Default")
      (node (ref "U4") (pin "27") (pinfunction "OSCI_27") (pintype "input"))
    )
    (net (code "291") (name "unconnected-(U4-OSCO-Pad28)") (class "Default")
      (node (ref "U4") (pin "28") (pinfunction "OSCO_28") (pintype "output"))
    )
    (net (code "292") (name "unconnected-(U4-~{CTS}-Pad8)") (class "Default")
      (node (ref "U4") (pin "8") (pinfunction "~{CTS}_8") (pintype "input"))
    )
    (net (code "293") (name "unconnected-(U4-~{DCD}-Pad7)") (class "Default")
      (node (ref "U4") (pin "7") (pinfunction "~{DCD}_7") (pintype "input"))
    )
    (net (code "294") (name "unconnected-(U4-~{DSR}-Pad6)") (class "Default")
      (node (ref "U4") (pin "6") (pinfunction "~{DSR}_6") (pintype "input"))
    )
    (net (code "295") (name "unconnected-(U4-~{DTR}-Pad31)") (class "Default")
      (node (ref "U4") (pin "31") (pinfunction "~{DTR}_31") (pintype "output"))
    )
    (net (code "296") (name "unconnected-(U4-~{RESET}-Pad18)") (class "Default")
      (node (ref "U4") (pin "18") (pinfunction "~{RESET}_18") (pintype "input"))
    )
    (net (code "297") (name "unconnected-(U4-~{RI}-Pad3)") (class "Default")
      (node (ref "U4") (pin "3") (pinfunction "~{RI}_3") (pintype "input"))
    )
    (net (code "298") (name "unconnected-(U4-~{RTS}-Pad32)") (class "Default")
      (node (ref "U4") (pin "32") (pinfunction "~{RTS}_32") (pintype "output"))
    )
    (net (code "299") (name "unconnected-(U5-CBUS0-Pad22)") (class "Default")
      (node (ref "U5") (pin "22") (pinfunction "CBUS0_22") (pintype "bidirectional"))
    )
    (net (code "300") (name "unconnected-(U5-CBUS1-Pad21)") (class "Default")
      (node (ref "U5") (pin "21") (pinfunction "CBUS1_21") (pintype "bidirectional"))
    )
    (net (code "301") (name "unconnected-(U5-CBUS2-Pad10)") (class "Default")
      (node (ref "U5") (pin "10") (pinfunction "CBUS2_10") (pintype "bidirectional"))
    )
    (net (code "302") (name "unconnected-(U5-CBUS3-Pad11)") (class "Default")
      (node (ref "U5") (pin "11") (pinfunction "CBUS3_11") (pintype "bidirectional"))
    )
    (net (code "303") (name "unconnected-(U5-CBUS4-Pad9)") (class "Default")
      (node (ref "U5") (pin "9") (pinfunction "CBUS4_9") (pintype "bidirectional"))
    )
    (net (code "304") (name "unconnected-(U5-OSCI-Pad27)") (class "Default")
      (node (ref "U5") (pin "27") (pinfunction "OSCI_27") (pintype "input"))
    )
    (net (code "305") (name "unconnected-(U5-OSCO-Pad28)") (class "Default")
      (node (ref "U5") (pin "28") (pinfunction "OSCO_28") (pintype "output"))
    )
    (net (code "306") (name "unconnected-(U5-~{CTS}-Pad8)") (class "Default")
      (node (ref "U5") (pin "8") (pinfunction "~{CTS}_8") (pintype "input"))
    )
    (net (code "307") (name "unconnected-(U5-~{DCD}-Pad7)") (class "Default")
      (node (ref "U5") (pin "7") (pinfunction "~{DCD}_7") (pintype "input"))
    )
    (net (code "308") (name "unconnected-(U5-~{DSR}-Pad6)") (class "Default")
      (node (ref "U5") (pin "6") (pinfunction "~{DSR}_6") (pintype "input"))
    )
    (net (code "309") (name "unconnected-(U5-~{DTR}-Pad31)") (class "Default")
      (node (ref "U5") (pin "31") (pinfunction "~{DTR}_31") (pintype "output"))
    )
    (net (code "310") (name "unconnected-(U5-~{RESET}-Pad18)") (class "Default")
      (node (ref "U5") (pin "18") (pinfunction "~{RESET}_18") (pintype "input"))
    )
    (net (code "311") (name "unconnected-(U5-~{RI}-Pad3)") (class "Default")
      (node (ref "U5") (pin "3") (pinfunction "~{RI}_3") (pintype "input"))
    )
    (net (code "312") (name "unconnected-(U5-~{RTS}-Pad32)") (class "Default")
      (node (ref "U5") (pin "32") (pinfunction "~{RTS}_32") (pintype "output"))
    )
    (net (code "313") (name "unconnected-(U13-INT-Pad7)") (class "Default")
      (node (ref "U13") (pin "7") (pinfunction "INT_7") (pintype "bidirectional"))
    )
    (net (code "314") (name "unconnected-(U13-P3-Pad12)") (class "Default")
      (node (ref "U13") (pin "12") (pinfunction "P3_12") (pintype "bidirectional"))
    )
    (net (code "315") (name "unconnected-(U13-P4-Pad13)") (class "Default")
      (node (ref "U13") (pin "13") (pinfunction "P4_13") (pintype "bidirectional"))
    )
    (net (code "316") (name "unconnected-(U13-P5-Pad14)") (class "Default")
      (node (ref "U13") (pin "14") (pinfunction "P5_14") (pintype "bidirectional"))
    )
    (net (code "317") (name "unconnected-(U13-P6-Pad15)") (class "Default")
      (node (ref "U13") (pin "15") (pinfunction "P6_15") (pintype "bidirectional"))
    )
    (net (code "318") (name "unconnected-(U13-P7-Pad16)") (class "Default")
      (node (ref "U13") (pin "16") (pinfunction "P7_16") (pintype "bidirectional"))
    )
    (net (code "319") (name "unconnected-(U14-INT-Pad7)") (class "Default")
      (node (ref "U14") (pin "7") (pinfunction "INT_7") (pintype "bidirectional"))
    )
    (net (code "320") (name "unconnected-(U14-P3-Pad12)") (class "Default")
      (node (ref "U14") (pin "12") (pinfunction "P3_12") (pintype "bidirectional"))
    )
    (net (code "321") (name "unconnected-(U14-P4-Pad13)") (class "Default")
      (node (ref "U14") (pin "13") (pinfunction "P4_13") (pintype "bidirectional"))
    )
    (net (code "322") (name "unconnected-(U14-P5-Pad14)") (class "Default")
      (node (ref "U14") (pin "14") (pinfunction "P5_14") (pintype "bidirectional"))
    )
    (net (code "323") (name "unconnected-(U14-P6-Pad15)") (class "Default")
      (node (ref "U14") (pin "15") (pinfunction "P6_15") (pintype "bidirectional"))
    )
    (net (code "324") (name "unconnected-(U14-P7-Pad16)") (class "Default")
      (node (ref "U14") (pin "16") (pinfunction "P7_16") (pintype "bidirectional"))
    )
    (net (code "325") (name "unconnected-(U16-ADVREFP-Pad18)") (class "Default")
      (node (ref "U16") (pin "18") (pinfunction "ADVREFP_18") (pintype "bidirectional"))
    )
    (net (code "326") (name "unconnected-(U16-PA04-Pad11)") (class "Default")
      (node (ref "U16") (pin "11") (pinfunction "PA04_11") (pintype "bidirectional"))
    )
    (net (code "327") (name "unconnected-(U16-PA05-Pad12)") (class "Default")
      (node (ref "U16") (pin "12") (pinfunction "PA05_12") (pintype "bidirectional"))
    )
    (net (code "328") (name "unconnected-(U16-PA06-Pad15)") (class "Default")
      (node (ref "U16") (pin "15") (pinfunction "PA06_15") (pintype "bidirectional"))
    )
    (net (code "329") (name "unconnected-(U16-PA07-Pad16)") (class "Default")
      (node (ref "U16") (pin "16") (pinfunction "PA07_16") (pintype "bidirectional"))
    )
    (net (code "330") (name "unconnected-(U16-PA08-Pad20)") (class "Default")
      (node (ref "U16") (pin "20") (pinfunction "PA08_20") (pintype "bidirectional"))
    )
    (net (code "331") (name "unconnected-(U16-PA09-Pad21)") (class "Default")
      (node (ref "U16") (pin "21") (pinfunction "PA09_21") (pintype "bidirectional"))
    )
    (net (code "332") (name "unconnected-(U16-PA10-Pad22)") (class "Default")
      (node (ref "U16") (pin "22") (pinfunction "PA10_22") (pintype "bidirectional"))
    )
    (net (code "333") (name "unconnected-(U16-PA13-Pad32)") (class "Default")
      (node (ref "U16") (pin "32") (pinfunction "PA13_32") (pintype "bidirectional"))
    )
    (net (code "334") (name "unconnected-(U16-PA14-Pad33)") (class "Default")
      (node (ref "U16") (pin "33") (pinfunction "PA14_33") (pintype "bidirectional"))
    )
    (net (code "335") (name "unconnected-(U16-PA15-Pad34)") (class "Default")
      (node (ref "U16") (pin "34") (pinfunction "PA15_34") (pintype "bidirectional"))
    )
    (net (code "336") (name "unconnected-(U16-PA16-Pad35)") (class "Default")
      (node (ref "U16") (pin "35") (pinfunction "PA16_35") (pintype "bidirectional"))
    )
    (net (code "337") (name "unconnected-(U16-PA17-Pad36)") (class "Default")
      (node (ref "U16") (pin "36") (pinfunction "PA17_36") (pintype "bidirectional"))
    )
    (net (code "338") (name "unconnected-(U16-PA21-Pad41)") (class "Default")
      (node (ref "U16") (pin "41") (pinfunction "PA21_41") (pintype "bidirectional"))
    )
    (net (code "339") (name "unconnected-(U16-PA22-Pad42)") (class "Default")
      (node (ref "U16") (pin "42") (pinfunction "PA22_42") (pintype "bidirectional"))
    )
    (net (code "340") (name "unconnected-(U16-XIN32-Pad13)") (class "Default")
      (node (ref "U16") (pin "13") (pinfunction "XIN32_13") (pintype "bidirectional"))
    )
    (net (code "341") (name "unconnected-(U16-XOUT32-Pad14)") (class "Default")
      (node (ref "U16") (pin "14") (pinfunction "XOUT32_14") (pintype "bidirectional"))
    )
    (net (code "342") (name "unconnected-(U19-A2-Pad3)") (class "Default")
      (node (ref "U19") (pin "3") (pinfunction "A2_3") (pintype "bidirectional"))
    )
    (net (code "343") (name "unconnected-(U19-B2-Pad6)") (class "Default")
      (node (ref "U19") (pin "6") (pinfunction "B2_6") (pintype "bidirectional"))
    )
    (net (code "344") (name "unconnected-(U20-A2-Pad3)") (class "Default")
      (node (ref "U20") (pin "3") (pinfunction "A2_3") (pintype "bidirectional"))
    )
    (net (code "345") (name "unconnected-(U20-B2-Pad6)") (class "Default")
      (node (ref "U20") (pin "6") (pinfunction "B2_6") (pintype "bidirectional"))
    )
    (net (code "346") (name "unconnected-(U24-EECLK-Pad7)") (class "Default")
      (node (ref "U24") (pin "7") (pinfunction "EECLK_7") (pintype "bidirectional"))
    )
    (net (code "347") (name "~{BACKPLANE_RESET}") (class "Default")
      (node (ref "J1") (pin "22") (pinfunction "~{BACKPLANE_RESET}_22") (pintype "bidirectional"))
      (node (ref "R42") (pin "2") (pinfunction "2_2") (pintype "passive"))
      (node (ref "S8") (pin "2") (pinfunction "P$2_2") (pintype "passive"))
      (node (ref "TP9") (pin "TESTPOINT") (pinfunction "TESTPOINT_TESTPOINT") (pintype "bidirectional"))
      (node (ref "U13") (pin "4") (pinfunction "~{RESET}_4") (pintype "bidirectional"))
      (node (ref "U14") (pin "4") (pinfunction "~{RESET}_4") (pintype "bidirectional"))
      (node (ref "U24") (pin "6") (pinfunction "~{RESET}_6") (pintype "bidirectional"))
    )
    (net (code "348") (name "~{SMBALERT}") (class "Default")
      (node (ref "J1") (pin "6") (pinfunction "~{SMBALERT}_6") (pintype "bidirectional"))
      (node (ref "R63") (pin "1") (pinfunction "1_1") (pintype "passive"))
      (node (ref "TP3") (pin "TESTPOINT") (pinfunction "TESTPOINT_TESTPOINT") (pintype "bidirectional"))
      (node (ref "U15") (pin "17") (pinfunction "~{INT}_17") (pintype "bidirectional"))
    )
  )
)
